# Sheet_1_2022-11-27.net
KiCad netlist of a schematic drawn in Altium Designer
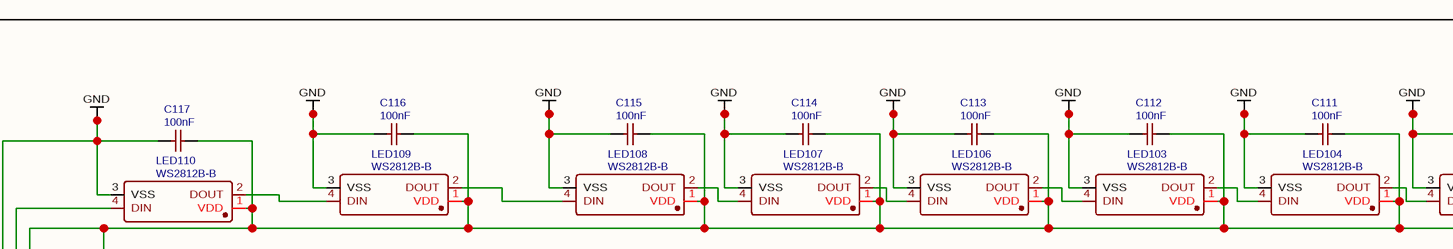
[diagram p0: Sheet_1_2022-11-27.schdoc, row 1 of 4 left]
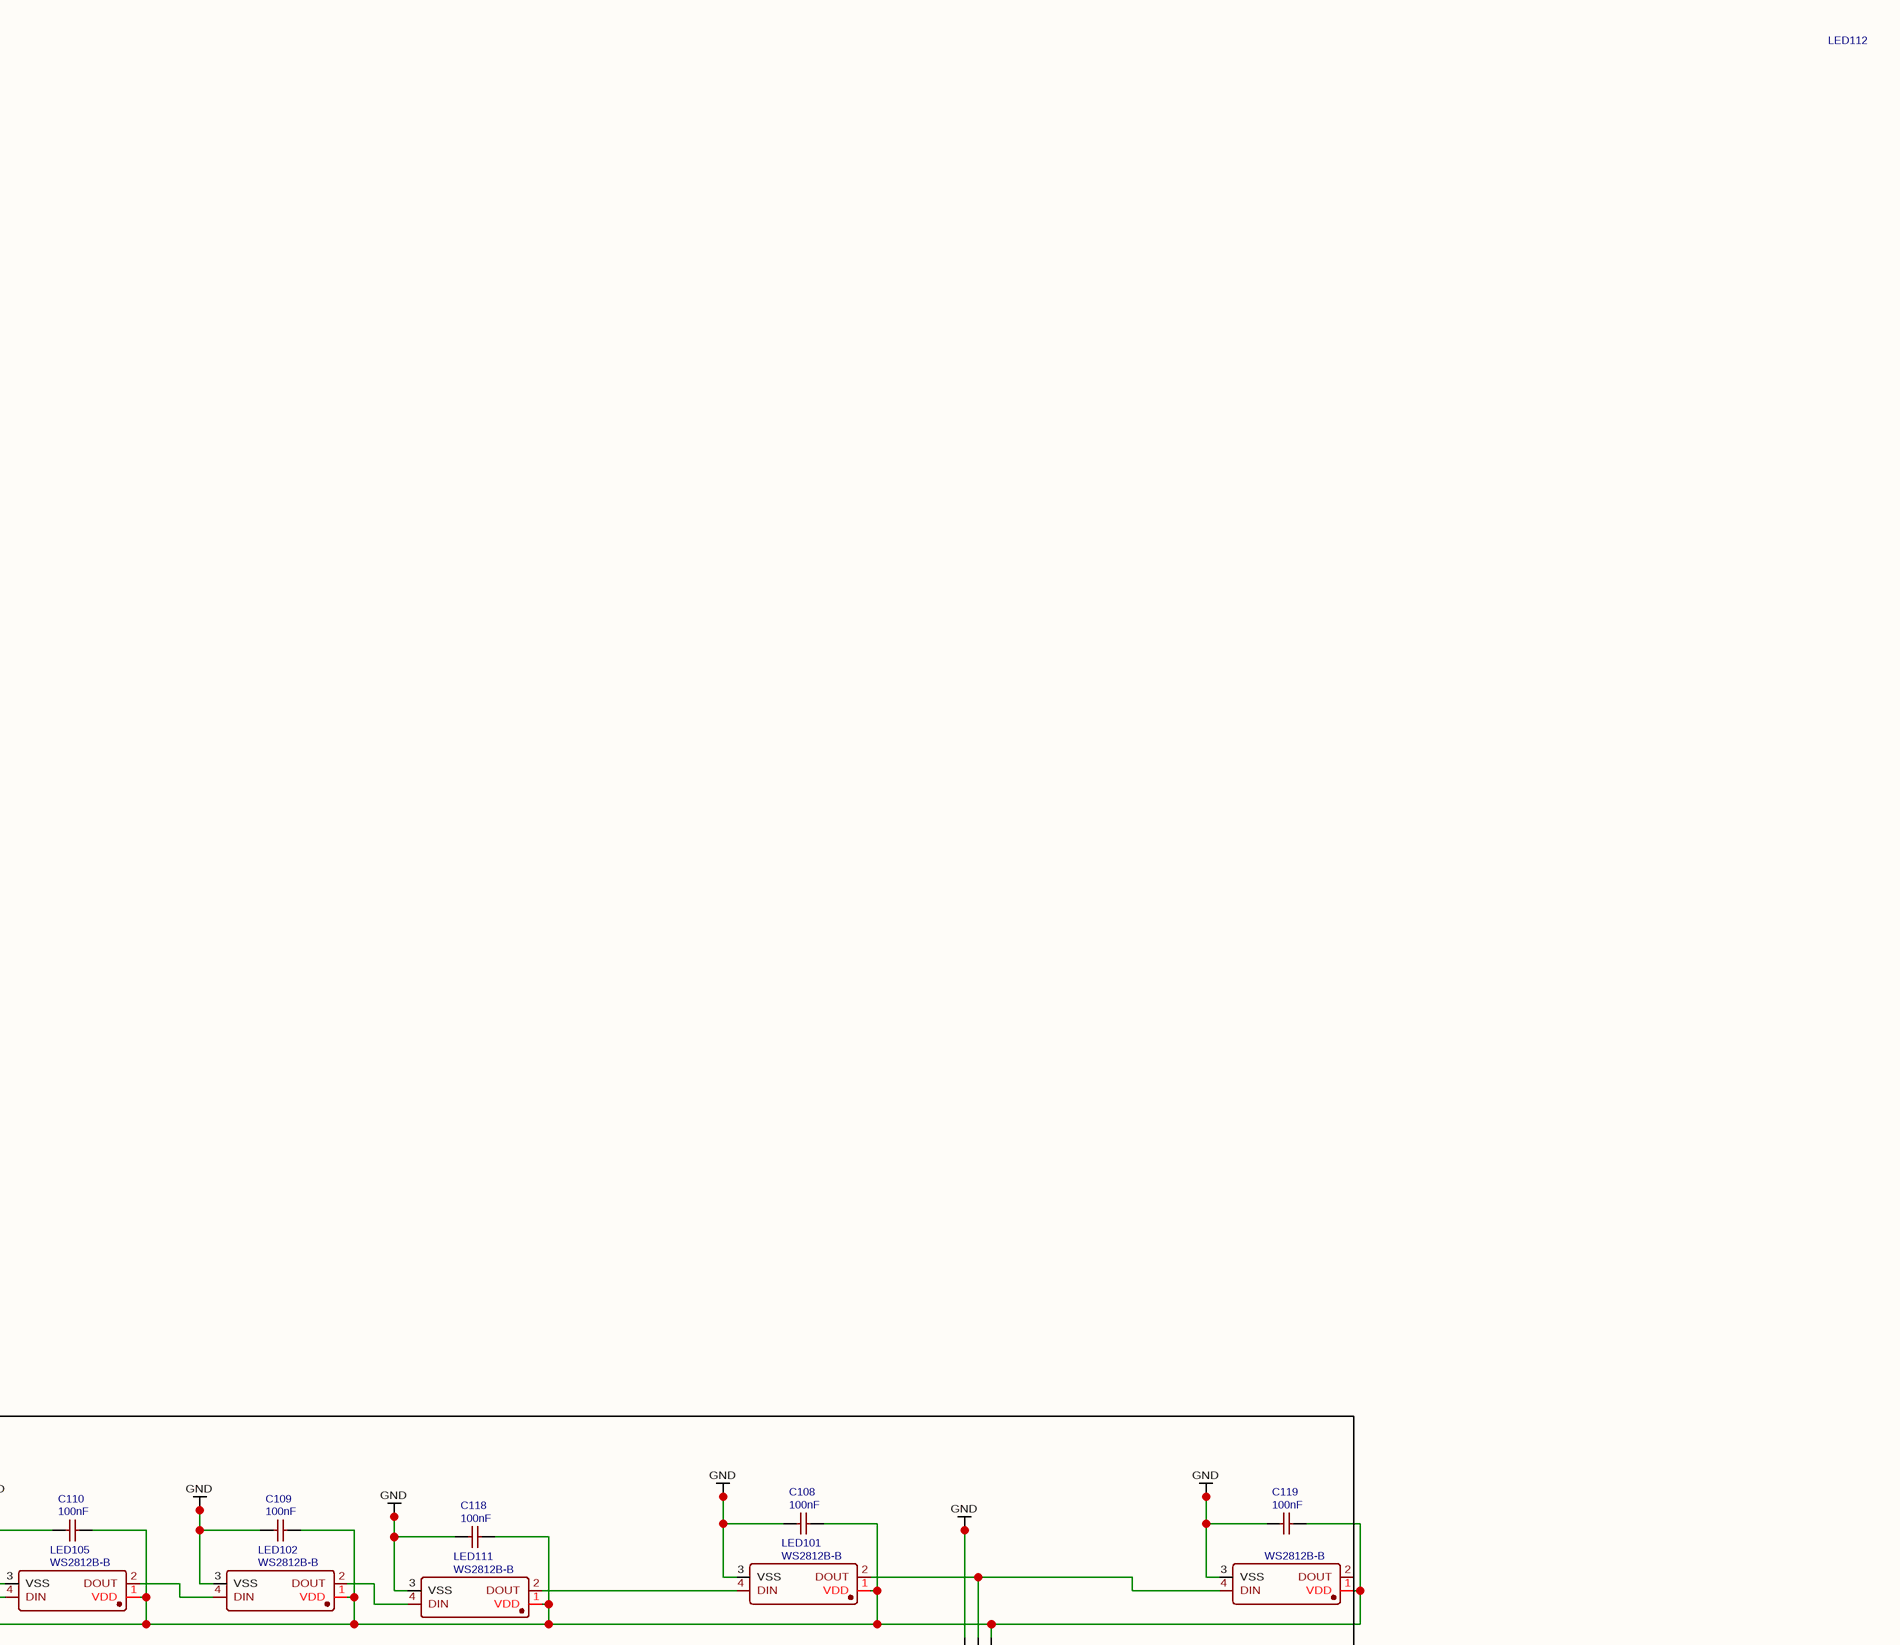
[diagram p1: Sheet_1_2022-11-27.schdoc, row 1 of 4 right]
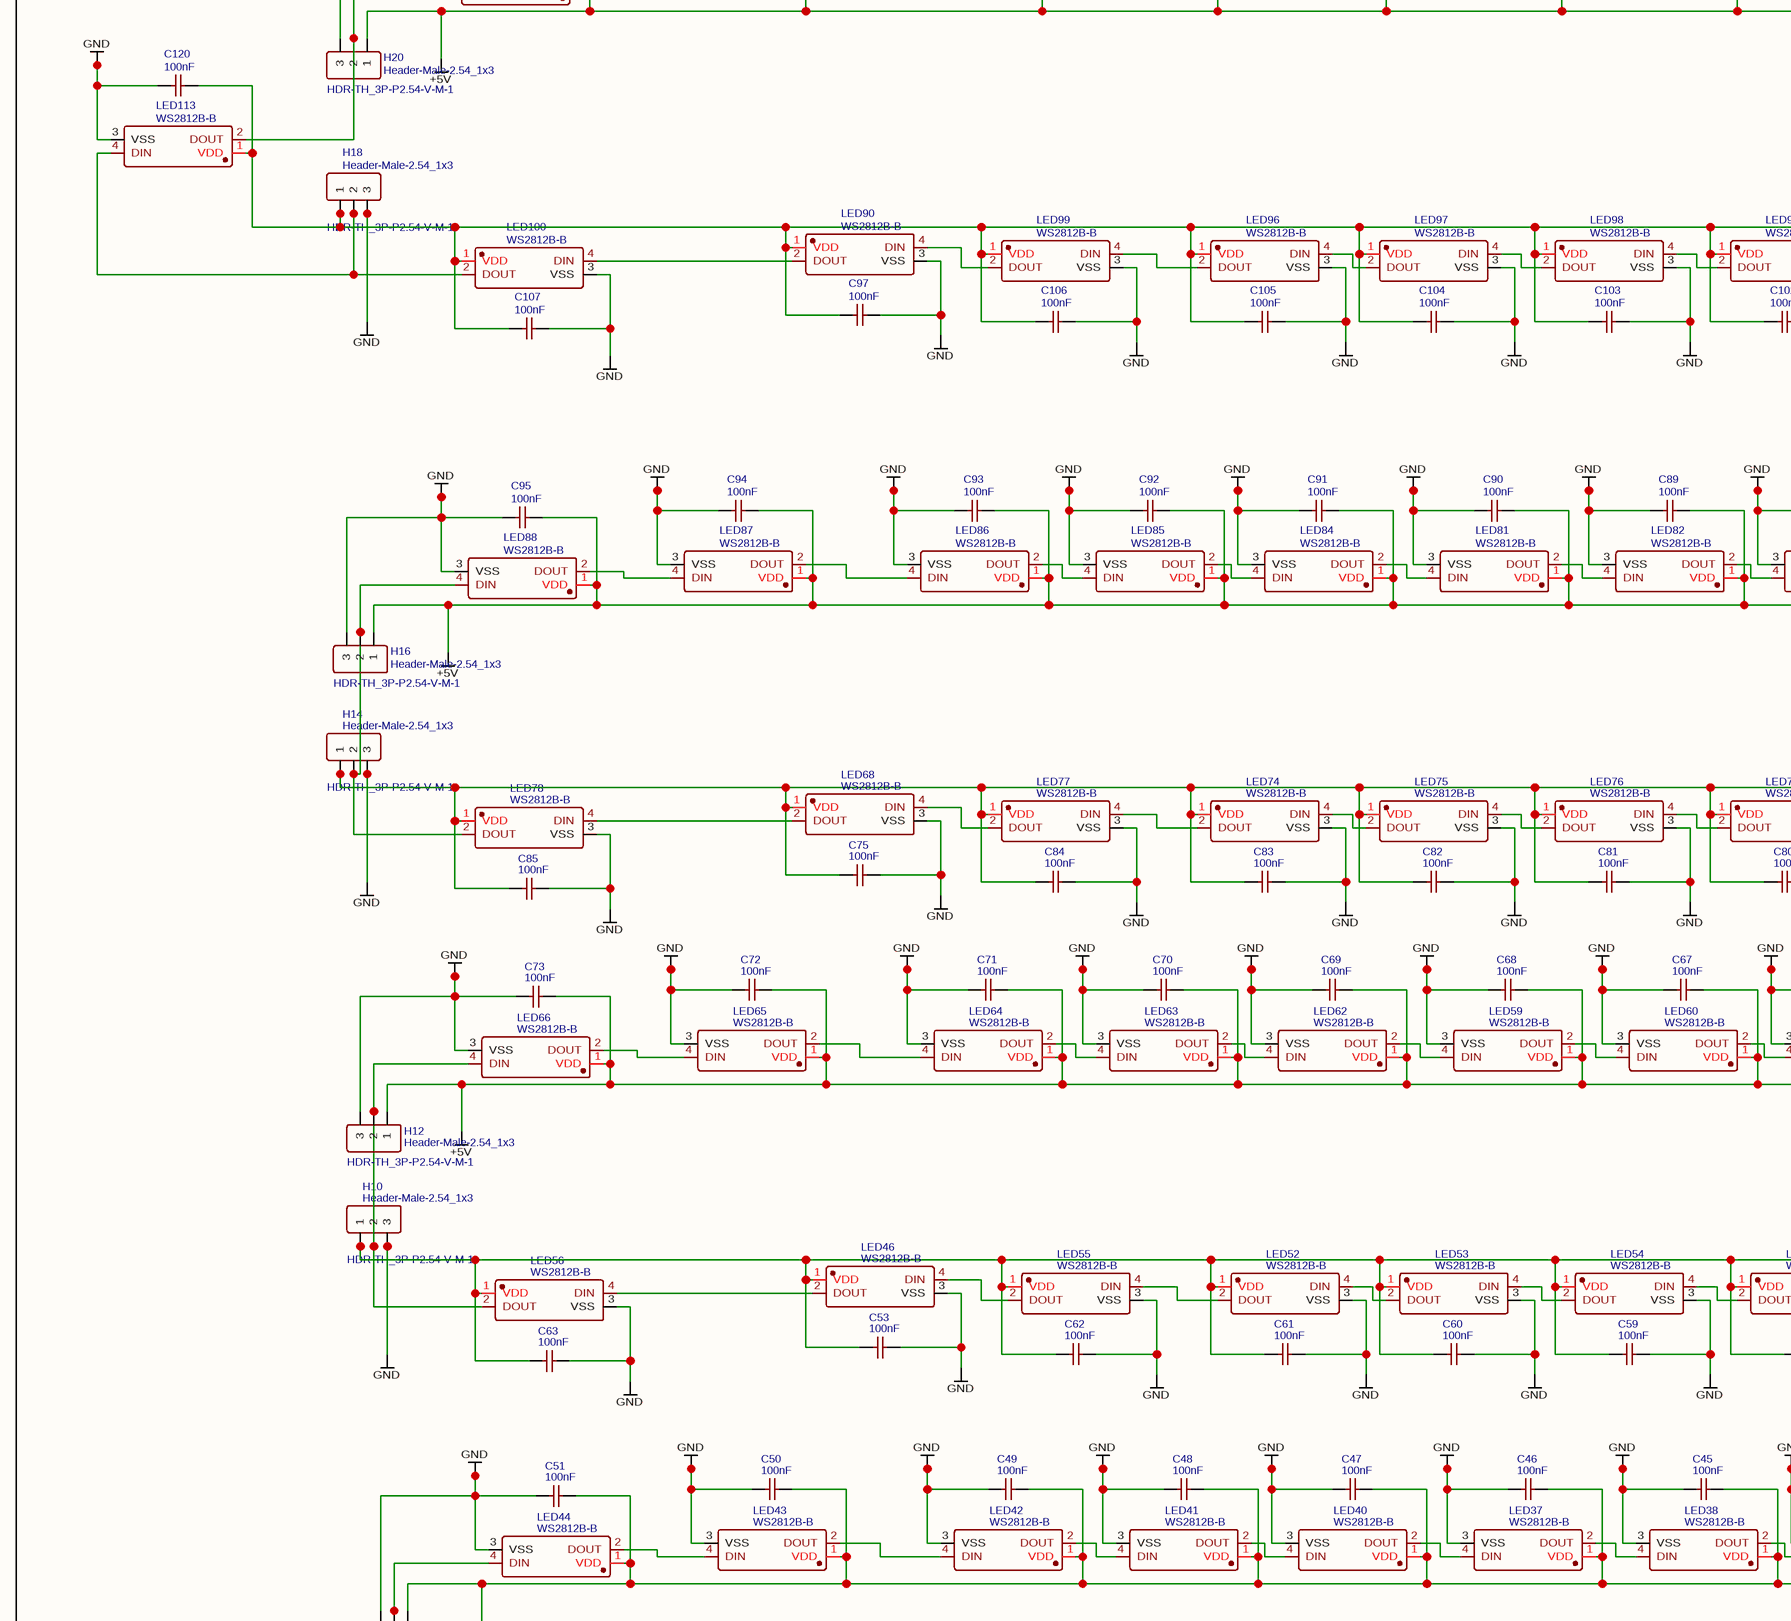
[diagram p2: Sheet_1_2022-11-27.schdoc, row 2 of 4 left]
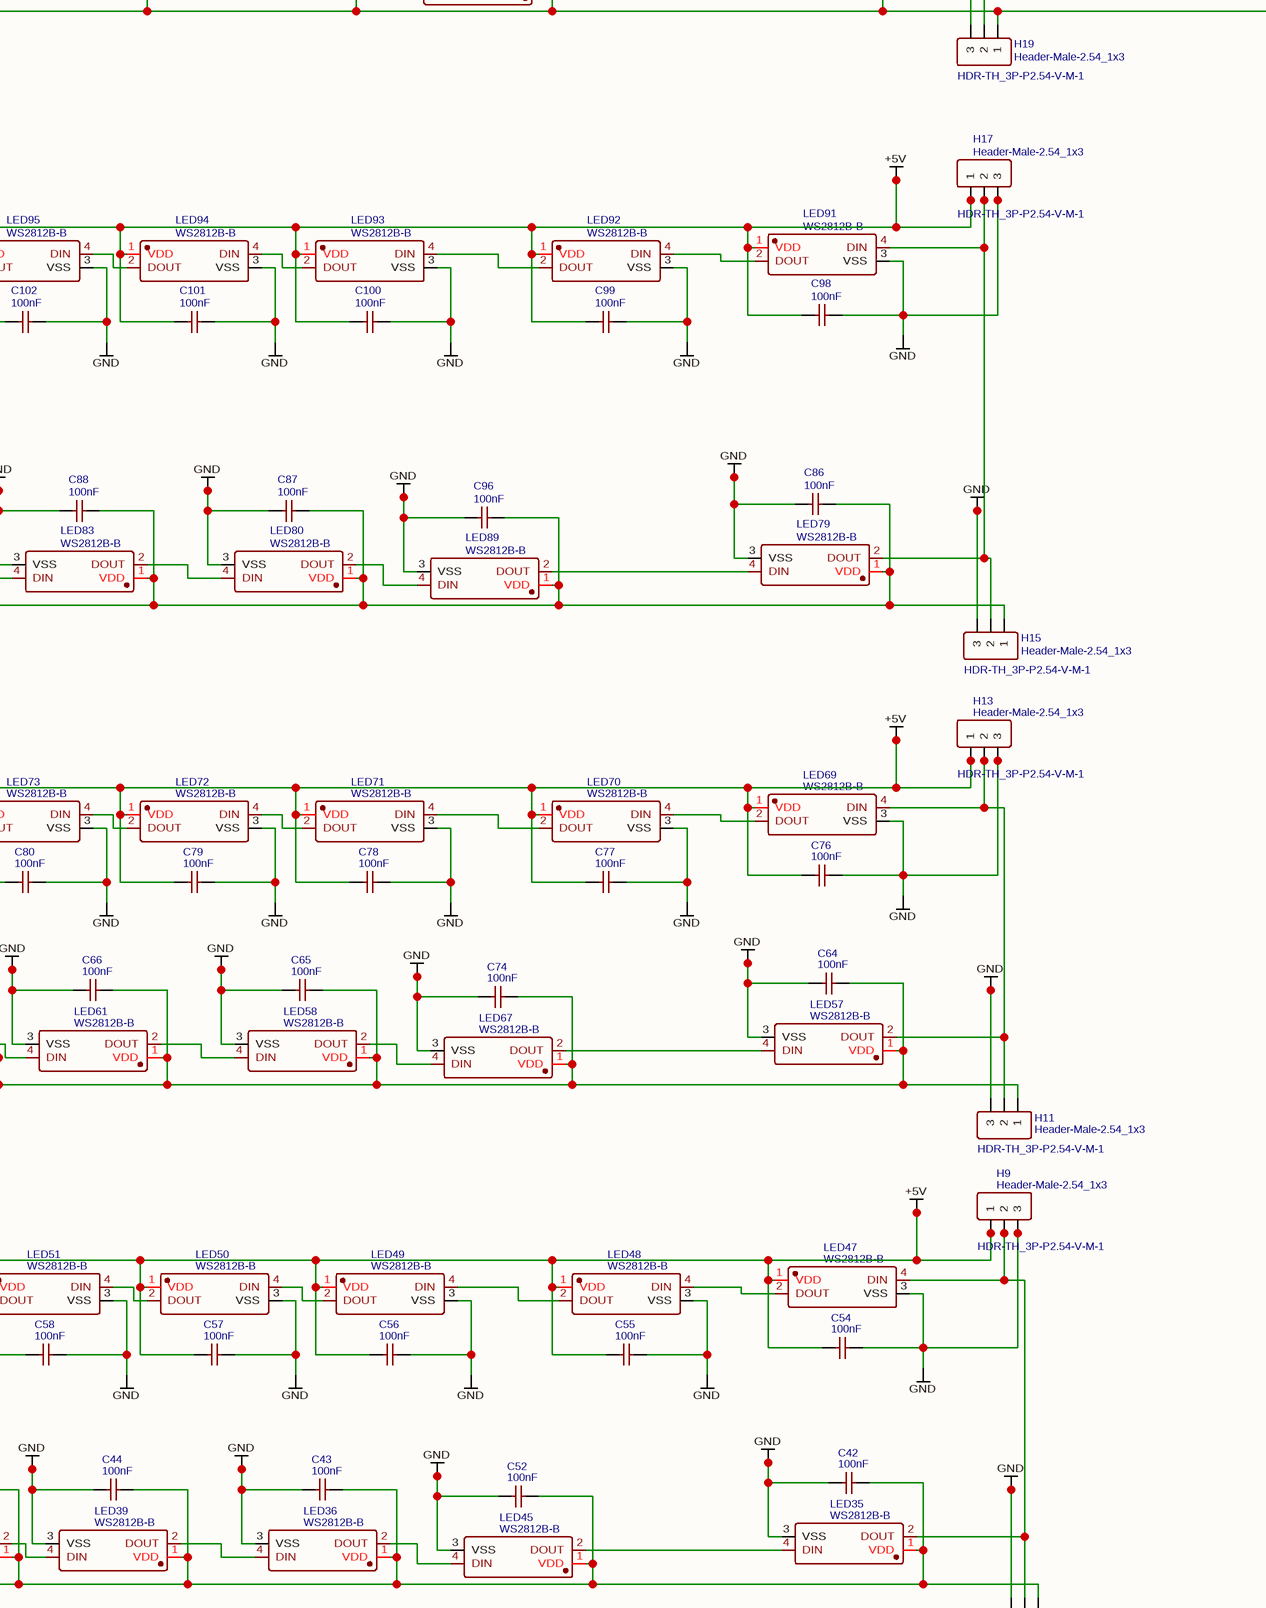
[diagram p3: Sheet_1_2022-11-27.schdoc, row 2 of 4 right]
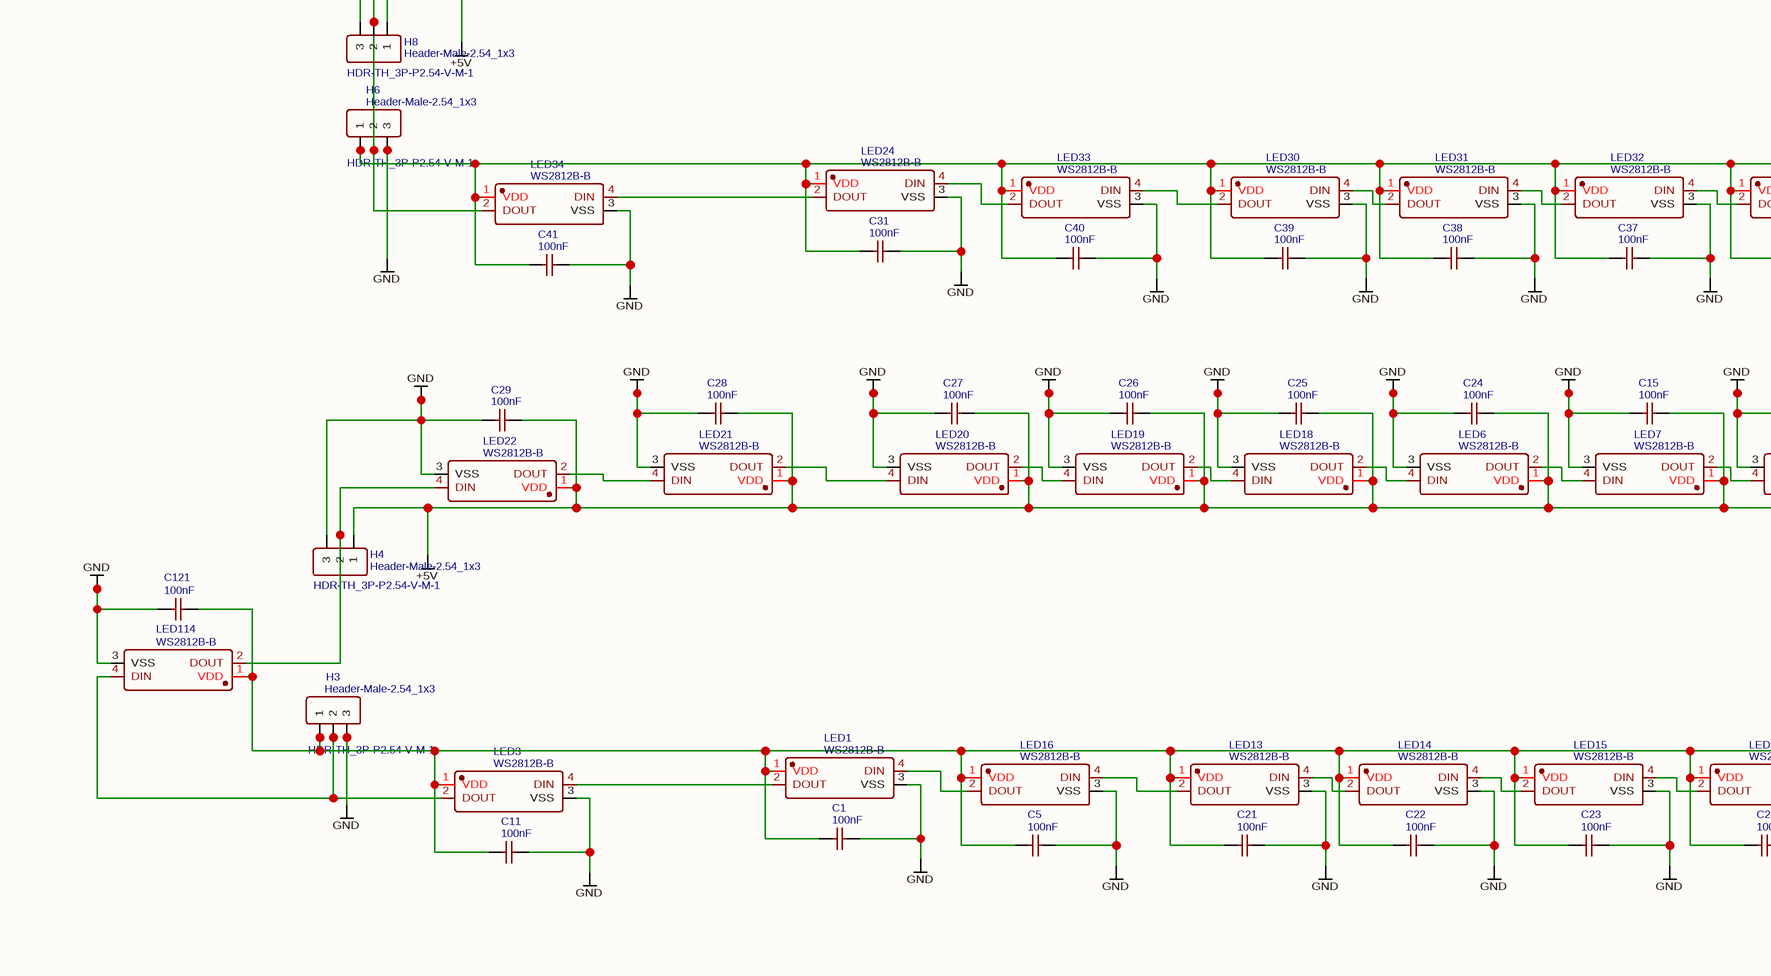
[diagram p4: Sheet_1_2022-11-27.schdoc, row 3 of 4 left]
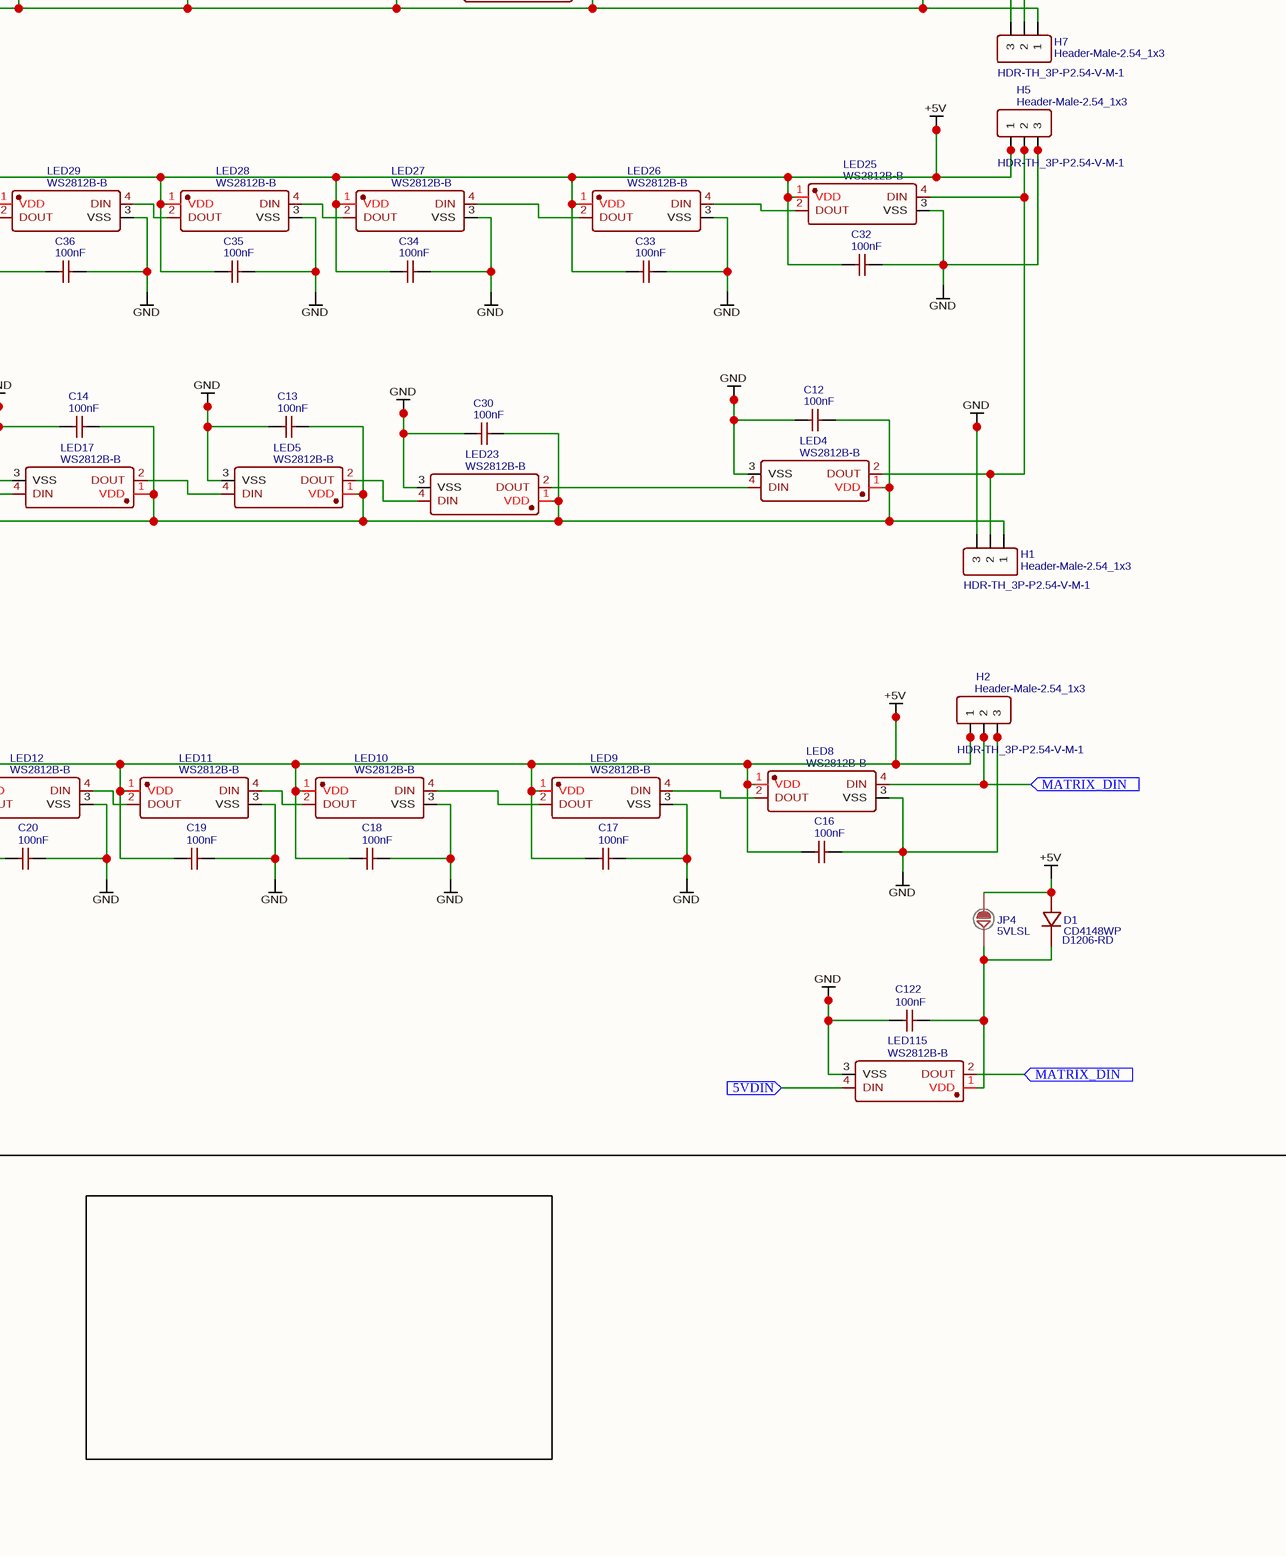
[diagram p5: Sheet_1_2022-11-27.schdoc, row 3 of 4 right]
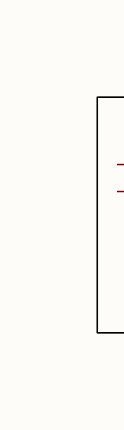
[diagram p6: Sheet_1_2022-11-27.schdoc, row 4 of 4 left]
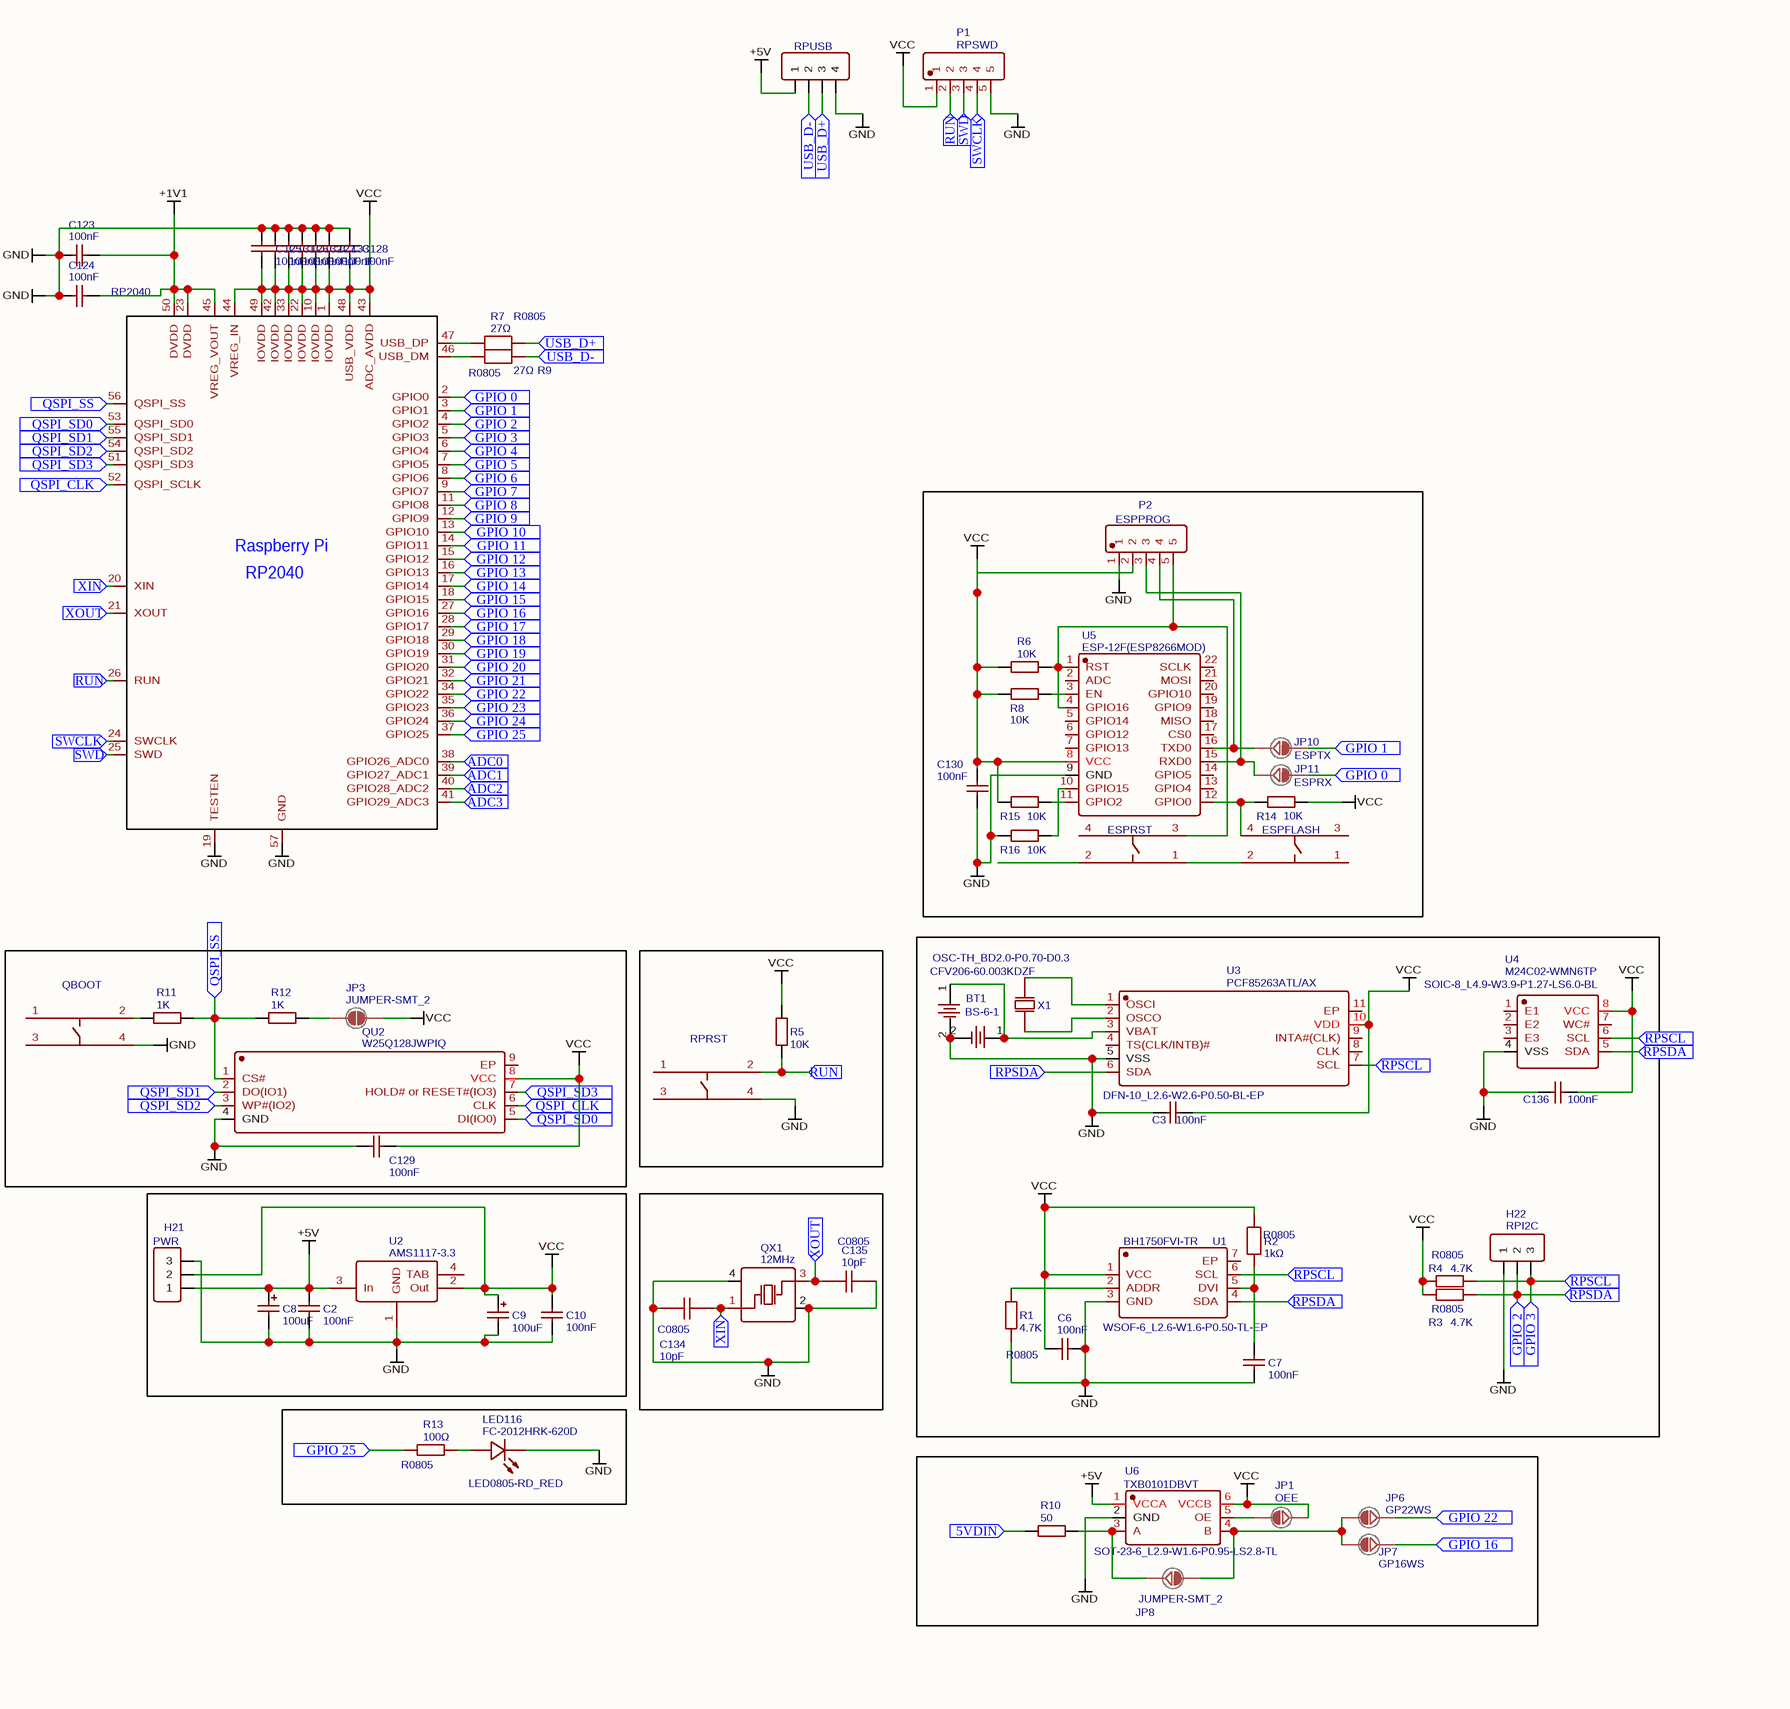
[diagram p7: Sheet_1_2022-11-27.schdoc, row 4 of 4 right]

(export (version "E")
  (design (tool "Eeschema 10.0.6"))
  (components
    (comp (ref "BT1")
      (value "BS-6-1")
      (fields (field (name "BOM_SUPPLIER PART") "C969909") (field (name "CONTRIBUTOR") "LCSC"))
      (libsource (lib "altium-import") (part "root_0_BS-6-1_"))
    )
    (comp (ref "BT2")
      (value "BS-6-1")
      (fields (field (name "BOM_SUPPLIER PART") "C969909") (field (name "CONTRIBUTOR") "LCSC"))
      (libsource (lib "altium-import") (part "root_1_BS-6-1_"))
    )
    (comp (ref "C1")
      (value "100nF")
      (fields
        (field (name "BOM_MANUFACTURER PART") "CC0805KRX7R9BB104")
        (field (name "BOM_SUPPLIER PART") "C49678")
      )
      (libsource (lib "altium-import") (part "root_0_100nF_"))
    )
    (comp (ref "C2")
      (value "100nF")
      (fields
        (field (name "BOM_MANUFACTURER PART") "CC0805KRX7R9BB104")
        (field (name "BOM_SUPPLIER PART") "C49678")
      )
      (libsource (lib "altium-import") (part "root_1_100nF_"))
    )
    (comp (ref "C3")
      (value "100nF")
      (fields
        (field (name "BOM_MANUFACTURER PART") "CC0805KRX7R9BB104")
        (field (name "BOM_SUPPLIER PART") "C49678")
      )
      (libsource (lib "altium-import") (part "root_2_100nF_"))
    )
    (comp (ref "C5")
      (value "100nF")
      (fields
        (field (name "BOM_MANUFACTURER PART") "CC0805KRX7R9BB104")
        (field (name "BOM_SUPPLIER PART") "C49678")
      )
      (libsource (lib "altium-import") (part "root_0_100nF_"))
    )
    (comp (ref "C6")
      (value "100nF")
      (fields
        (field (name "BOM_MANUFACTURER PART") "CC0805KRX7R9BB104")
        (field (name "BOM_SUPPLIER PART") "C49678")
      )
      (libsource (lib "altium-import") (part "root_2_100nF_"))
    )
    (comp (ref "C7")
      (value "100nF")
      (fields
        (field (name "BOM_MANUFACTURER PART") "CC0805KRX7R9BB104")
        (field (name "BOM_SUPPLIER PART") "C49678")
      )
      (libsource (lib "altium-import") (part "root_3_100nF_"))
    )
    (comp (ref "C8")
      (value "100uF")
      (fields
        (field (name "BOM_MANUFACTURER PART") "TAJB107K006RNJ")
        (field (name "BOM_SUPPLIER PART") "C16133")
      )
      (libsource (lib "altium-import") (part "root_3_100uF_"))
    )
    (comp (ref "C9")
      (value "100uF")
      (fields
        (field (name "BOM_MANUFACTURER PART") "TAJB107K006RNJ")
        (field (name "BOM_SUPPLIER PART") "C16133")
      )
      (libsource (lib "altium-import") (part "root_3_100uF_"))
    )
    (comp (ref "C10")
      (value "100nF")
      (fields
        (field (name "BOM_MANUFACTURER PART") "CC0805KRX7R9BB104")
        (field (name "BOM_SUPPLIER PART") "C49678")
      )
      (libsource (lib "altium-import") (part "root_1_100nF_"))
    )
    (comp (ref "C11")
      (value "100nF")
      (fields
        (field (name "BOM_MANUFACTURER PART") "CC0805KRX7R9BB104")
        (field (name "BOM_SUPPLIER PART") "C49678")
      )
      (libsource (lib "altium-import") (part "root_0_100nF_"))
    )
    (comp (ref "C12")
      (value "100nF")
      (fields
        (field (name "BOM_MANUFACTURER PART") "CC0805KRX7R9BB104")
        (field (name "BOM_SUPPLIER PART") "C49678")
      )
      (libsource (lib "altium-import") (part "root_2_100nF_"))
    )
    (comp (ref "C13")
      (value "100nF")
      (fields
        (field (name "BOM_MANUFACTURER PART") "CC0805KRX7R9BB104")
        (field (name "BOM_SUPPLIER PART") "C49678")
      )
      (libsource (lib "altium-import") (part "root_2_100nF_"))
    )
    (comp (ref "C14")
      (value "100nF")
      (fields
        (field (name "BOM_MANUFACTURER PART") "CC0805KRX7R9BB104")
        (field (name "BOM_SUPPLIER PART") "C49678")
      )
      (libsource (lib "altium-import") (part "root_2_100nF_"))
    )
    (comp (ref "C15")
      (value "100nF")
      (fields
        (field (name "BOM_MANUFACTURER PART") "CC0805KRX7R9BB104")
        (field (name "BOM_SUPPLIER PART") "C49678")
      )
      (libsource (lib "altium-import") (part "root_2_100nF_"))
    )
    (comp (ref "C16")
      (value "100nF")
      (fields
        (field (name "BOM_MANUFACTURER PART") "CC0805KRX7R9BB104")
        (field (name "BOM_SUPPLIER PART") "C49678")
      )
      (libsource (lib "altium-import") (part "root_0_100nF_"))
    )
    (comp (ref "C17")
      (value "100nF")
      (fields
        (field (name "BOM_MANUFACTURER PART") "CC0805KRX7R9BB104")
        (field (name "BOM_SUPPLIER PART") "C49678")
      )
      (libsource (lib "altium-import") (part "root_0_100nF_"))
    )
    (comp (ref "C18")
      (value "100nF")
      (fields
        (field (name "BOM_MANUFACTURER PART") "CC0805KRX7R9BB104")
        (field (name "BOM_SUPPLIER PART") "C49678")
      )
      (libsource (lib "altium-import") (part "root_0_100nF_"))
    )
    (comp (ref "C19")
      (value "100nF")
      (fields
        (field (name "BOM_MANUFACTURER PART") "CC0805KRX7R9BB104")
        (field (name "BOM_SUPPLIER PART") "C49678")
      )
      (libsource (lib "altium-import") (part "root_0_100nF_"))
    )
    (comp (ref "C20")
      (value "100nF")
      (fields
        (field (name "BOM_MANUFACTURER PART") "CC0805KRX7R9BB104")
        (field (name "BOM_SUPPLIER PART") "C49678")
      )
      (libsource (lib "altium-import") (part "root_0_100nF_"))
    )
    (comp (ref "C21")
      (value "100nF")
      (fields
        (field (name "BOM_MANUFACTURER PART") "CC0805KRX7R9BB104")
        (field (name "BOM_SUPPLIER PART") "C49678")
      )
      (libsource (lib "altium-import") (part "root_0_100nF_"))
    )
    (comp (ref "C22")
      (value "100nF")
      (fields
        (field (name "BOM_MANUFACTURER PART") "CC0805KRX7R9BB104")
        (field (name "BOM_SUPPLIER PART") "C49678")
      )
      (libsource (lib "altium-import") (part "root_0_100nF_"))
    )
    (comp (ref "C23")
      (value "100nF")
      (fields
        (field (name "BOM_MANUFACTURER PART") "CC0805KRX7R9BB104")
        (field (name "BOM_SUPPLIER PART") "C49678")
      )
      (libsource (lib "altium-import") (part "root_0_100nF_"))
    )
    (comp (ref "C24")
      (value "100nF")
      (fields
        (field (name "BOM_MANUFACTURER PART") "CC0805KRX7R9BB104")
        (field (name "BOM_SUPPLIER PART") "C49678")
      )
      (libsource (lib "altium-import") (part "root_2_100nF_"))
    )
    (comp (ref "C25")
      (value "100nF")
      (fields
        (field (name "BOM_MANUFACTURER PART") "CC0805KRX7R9BB104")
        (field (name "BOM_SUPPLIER PART") "C49678")
      )
      (libsource (lib "altium-import") (part "root_2_100nF_"))
    )
    (comp (ref "C26")
      (value "100nF")
      (fields
        (field (name "BOM_MANUFACTURER PART") "CC0805KRX7R9BB104")
        (field (name "BOM_SUPPLIER PART") "C49678")
      )
      (libsource (lib "altium-import") (part "root_2_100nF_"))
    )
    (comp (ref "C27")
      (value "100nF")
      (fields
        (field (name "BOM_MANUFACTURER PART") "CC0805KRX7R9BB104")
        (field (name "BOM_SUPPLIER PART") "C49678")
      )
      (libsource (lib "altium-import") (part "root_2_100nF_"))
    )
    (comp (ref "C28")
      (value "100nF")
      (fields
        (field (name "BOM_MANUFACTURER PART") "CC0805KRX7R9BB104")
        (field (name "BOM_SUPPLIER PART") "C49678")
      )
      (libsource (lib "altium-import") (part "root_2_100nF_"))
    )
    (comp (ref "C29")
      (value "100nF")
      (fields
        (field (name "BOM_MANUFACTURER PART") "CC0805KRX7R9BB104")
        (field (name "BOM_SUPPLIER PART") "C49678")
      )
      (libsource (lib "altium-import") (part "root_2_100nF_"))
    )
    (comp (ref "C30")
      (value "100nF")
      (fields
        (field (name "BOM_MANUFACTURER PART") "CC0805KRX7R9BB104")
        (field (name "BOM_SUPPLIER PART") "C49678")
      )
      (libsource (lib "altium-import") (part "root_2_100nF_"))
    )
    (comp (ref "C31")
      (value "100nF")
      (fields
        (field (name "BOM_MANUFACTURER PART") "CC0805KRX7R9BB104")
        (field (name "BOM_SUPPLIER PART") "C49678")
      )
      (libsource (lib "altium-import") (part "root_0_100nF_"))
    )
    (comp (ref "C32")
      (value "100nF")
      (fields
        (field (name "BOM_MANUFACTURER PART") "CC0805KRX7R9BB104")
        (field (name "BOM_SUPPLIER PART") "C49678")
      )
      (libsource (lib "altium-import") (part "root_0_100nF_"))
    )
    (comp (ref "C33")
      (value "100nF")
      (fields
        (field (name "BOM_MANUFACTURER PART") "CC0805KRX7R9BB104")
        (field (name "BOM_SUPPLIER PART") "C49678")
      )
      (libsource (lib "altium-import") (part "root_0_100nF_"))
    )
    (comp (ref "C34")
      (value "100nF")
      (fields
        (field (name "BOM_MANUFACTURER PART") "CC0805KRX7R9BB104")
        (field (name "BOM_SUPPLIER PART") "C49678")
      )
      (libsource (lib "altium-import") (part "root_0_100nF_"))
    )
    (comp (ref "C35")
      (value "100nF")
      (fields
        (field (name "BOM_MANUFACTURER PART") "CC0805KRX7R9BB104")
        (field (name "BOM_SUPPLIER PART") "C49678")
      )
      (libsource (lib "altium-import") (part "root_0_100nF_"))
    )
    (comp (ref "C36")
      (value "100nF")
      (fields
        (field (name "BOM_MANUFACTURER PART") "CC0805KRX7R9BB104")
        (field (name "BOM_SUPPLIER PART") "C49678")
      )
      (libsource (lib "altium-import") (part "root_0_100nF_"))
    )
    (comp (ref "C37")
      (value "100nF")
      (fields
        (field (name "BOM_MANUFACTURER PART") "CC0805KRX7R9BB104")
        (field (name "BOM_SUPPLIER PART") "C49678")
      )
      (libsource (lib "altium-import") (part "root_0_100nF_"))
    )
    (comp (ref "C38")
      (value "100nF")
      (fields
        (field (name "BOM_MANUFACTURER PART") "CC0805KRX7R9BB104")
        (field (name "BOM_SUPPLIER PART") "C49678")
      )
      (libsource (lib "altium-import") (part "root_0_100nF_"))
    )
    (comp (ref "C39")
      (value "100nF")
      (fields
        (field (name "BOM_MANUFACTURER PART") "CC0805KRX7R9BB104")
        (field (name "BOM_SUPPLIER PART") "C49678")
      )
      (libsource (lib "altium-import") (part "root_0_100nF_"))
    )
    (comp (ref "C40")
      (value "100nF")
      (fields
        (field (name "BOM_MANUFACTURER PART") "CC0805KRX7R9BB104")
        (field (name "BOM_SUPPLIER PART") "C49678")
      )
      (libsource (lib "altium-import") (part "root_0_100nF_"))
    )
    (comp (ref "C41")
      (value "100nF")
      (fields
        (field (name "BOM_MANUFACTURER PART") "CC0805KRX7R9BB104")
        (field (name "BOM_SUPPLIER PART") "C49678")
      )
      (libsource (lib "altium-import") (part "root_0_100nF_"))
    )
    (comp (ref "C42")
      (value "100nF")
      (fields
        (field (name "BOM_MANUFACTURER PART") "CC0805KRX7R9BB104")
        (field (name "BOM_SUPPLIER PART") "C49678")
      )
      (libsource (lib "altium-import") (part "root_2_100nF_"))
    )
    (comp (ref "C43")
      (value "100nF")
      (fields
        (field (name "BOM_MANUFACTURER PART") "CC0805KRX7R9BB104")
        (field (name "BOM_SUPPLIER PART") "C49678")
      )
      (libsource (lib "altium-import") (part "root_2_100nF_"))
    )
    (comp (ref "C44")
      (value "100nF")
      (fields
        (field (name "BOM_MANUFACTURER PART") "CC0805KRX7R9BB104")
        (field (name "BOM_SUPPLIER PART") "C49678")
      )
      (libsource (lib "altium-import") (part "root_2_100nF_"))
    )
    (comp (ref "C45")
      (value "100nF")
      (fields
        (field (name "BOM_MANUFACTURER PART") "CC0805KRX7R9BB104")
        (field (name "BOM_SUPPLIER PART") "C49678")
      )
      (libsource (lib "altium-import") (part "root_2_100nF_"))
    )
    (comp (ref "C46")
      (value "100nF")
      (fields
        (field (name "BOM_MANUFACTURER PART") "CC0805KRX7R9BB104")
        (field (name "BOM_SUPPLIER PART") "C49678")
      )
      (libsource (lib "altium-import") (part "root_2_100nF_"))
    )
    (comp (ref "C47")
      (value "100nF")
      (fields
        (field (name "BOM_MANUFACTURER PART") "CC0805KRX7R9BB104")
        (field (name "BOM_SUPPLIER PART") "C49678")
      )
      (libsource (lib "altium-import") (part "root_2_100nF_"))
    )
    (comp (ref "C48")
      (value "100nF")
      (fields
        (field (name "BOM_MANUFACTURER PART") "CC0805KRX7R9BB104")
        (field (name "BOM_SUPPLIER PART") "C49678")
      )
      (libsource (lib "altium-import") (part "root_2_100nF_"))
    )
    (comp (ref "C49")
      (value "100nF")
      (fields
        (field (name "BOM_MANUFACTURER PART") "CC0805KRX7R9BB104")
        (field (name "BOM_SUPPLIER PART") "C49678")
      )
      (libsource (lib "altium-import") (part "root_2_100nF_"))
    )
    (comp (ref "C50")
      (value "100nF")
      (fields
        (field (name "BOM_MANUFACTURER PART") "CC0805KRX7R9BB104")
        (field (name "BOM_SUPPLIER PART") "C49678")
      )
      (libsource (lib "altium-import") (part "root_2_100nF_"))
    )
    (comp (ref "C51")
      (value "100nF")
      (fields
        (field (name "BOM_MANUFACTURER PART") "CC0805KRX7R9BB104")
        (field (name "BOM_SUPPLIER PART") "C49678")
      )
      (libsource (lib "altium-import") (part "root_2_100nF_"))
    )
    (comp (ref "C52")
      (value "100nF")
      (fields
        (field (name "BOM_MANUFACTURER PART") "CC0805KRX7R9BB104")
        (field (name "BOM_SUPPLIER PART") "C49678")
      )
      (libsource (lib "altium-import") (part "root_2_100nF_"))
    )
    (comp (ref "C53")
      (value "100nF")
      (fields
        (field (name "BOM_MANUFACTURER PART") "CC0805KRX7R9BB104")
        (field (name "BOM_SUPPLIER PART") "C49678")
      )
      (libsource (lib "altium-import") (part "root_0_100nF_"))
    )
    (comp (ref "C54")
      (value "100nF")
      (fields
        (field (name "BOM_MANUFACTURER PART") "CC0805KRX7R9BB104")
        (field (name "BOM_SUPPLIER PART") "C49678")
      )
      (libsource (lib "altium-import") (part "root_0_100nF_"))
    )
    (comp (ref "C55")
      (value "100nF")
      (fields
        (field (name "BOM_MANUFACTURER PART") "CC0805KRX7R9BB104")
        (field (name "BOM_SUPPLIER PART") "C49678")
      )
      (libsource (lib "altium-import") (part "root_0_100nF_"))
    )
    (comp (ref "C56")
      (value "100nF")
      (fields
        (field (name "BOM_MANUFACTURER PART") "CC0805KRX7R9BB104")
        (field (name "BOM_SUPPLIER PART") "C49678")
      )
      (libsource (lib "altium-import") (part "root_0_100nF_"))
    )
    (comp (ref "C57")
      (value "100nF")
      (fields
        (field (name "BOM_MANUFACTURER PART") "CC0805KRX7R9BB104")
        (field (name "BOM_SUPPLIER PART") "C49678")
      )
      (libsource (lib "altium-import") (part "root_0_100nF_"))
    )
    (comp (ref "C58")
      (value "100nF")
      (fields
        (field (name "BOM_MANUFACTURER PART") "CC0805KRX7R9BB104")
        (field (name "BOM_SUPPLIER PART") "C49678")
      )
      (libsource (lib "altium-import") (part "root_0_100nF_"))
    )
    (comp (ref "C59")
      (value "100nF")
      (fields
        (field (name "BOM_MANUFACTURER PART") "CC0805KRX7R9BB104")
        (field (name "BOM_SUPPLIER PART") "C49678")
      )
      (libsource (lib "altium-import") (part "root_0_100nF_"))
    )
    (comp (ref "C60")
      (value "100nF")
      (fields
        (field (name "BOM_MANUFACTURER PART") "CC0805KRX7R9BB104")
        (field (name "BOM_SUPPLIER PART") "C49678")
      )
      (libsource (lib "altium-import") (part "root_0_100nF_"))
    )
    (comp (ref "C61")
      (value "100nF")
      (fields
        (field (name "BOM_MANUFACTURER PART") "CC0805KRX7R9BB104")
        (field (name "BOM_SUPPLIER PART") "C49678")
      )
      (libsource (lib "altium-import") (part "root_0_100nF_"))
    )
    (comp (ref "C62")
      (value "100nF")
      (fields
        (field (name "BOM_MANUFACTURER PART") "CC0805KRX7R9BB104")
        (field (name "BOM_SUPPLIER PART") "C49678")
      )
      (libsource (lib "altium-import") (part "root_0_100nF_"))
    )
    (comp (ref "C63")
      (value "100nF")
      (fields
        (field (name "BOM_MANUFACTURER PART") "CC0805KRX7R9BB104")
        (field (name "BOM_SUPPLIER PART") "C49678")
      )
      (libsource (lib "altium-import") (part "root_0_100nF_"))
    )
    (comp (ref "C64")
      (value "100nF")
      (fields
        (field (name "BOM_MANUFACTURER PART") "CC0805KRX7R9BB104")
        (field (name "BOM_SUPPLIER PART") "C49678")
      )
      (libsource (lib "altium-import") (part "root_2_100nF_"))
    )
    (comp (ref "C65")
      (value "100nF")
      (fields
        (field (name "BOM_MANUFACTURER PART") "CC0805KRX7R9BB104")
        (field (name "BOM_SUPPLIER PART") "C49678")
      )
      (libsource (lib "altium-import") (part "root_2_100nF_"))
    )
    (comp (ref "C66")
      (value "100nF")
      (fields
        (field (name "BOM_MANUFACTURER PART") "CC0805KRX7R9BB104")
        (field (name "BOM_SUPPLIER PART") "C49678")
      )
      (libsource (lib "altium-import") (part "root_2_100nF_"))
    )
    (comp (ref "C67")
      (value "100nF")
      (fields
        (field (name "BOM_MANUFACTURER PART") "CC0805KRX7R9BB104")
        (field (name "BOM_SUPPLIER PART") "C49678")
      )
      (libsource (lib "altium-import") (part "root_2_100nF_"))
    )
    (comp (ref "C68")
      (value "100nF")
      (fields
        (field (name "BOM_MANUFACTURER PART") "CC0805KRX7R9BB104")
        (field (name "BOM_SUPPLIER PART") "C49678")
      )
      (libsource (lib "altium-import") (part "root_2_100nF_"))
    )
    (comp (ref "C69")
      (value "100nF")
      (fields
        (field (name "BOM_MANUFACTURER PART") "CC0805KRX7R9BB104")
        (field (name "BOM_SUPPLIER PART") "C49678")
      )
      (libsource (lib "altium-import") (part "root_2_100nF_"))
    )
    (comp (ref "C70")
      (value "100nF")
      (fields
        (field (name "BOM_MANUFACTURER PART") "CC0805KRX7R9BB104")
        (field (name "BOM_SUPPLIER PART") "C49678")
      )
      (libsource (lib "altium-import") (part "root_2_100nF_"))
    )
    (comp (ref "C71")
      (value "100nF")
      (fields
        (field (name "BOM_MANUFACTURER PART") "CC0805KRX7R9BB104")
        (field (name "BOM_SUPPLIER PART") "C49678")
      )
      (libsource (lib "altium-import") (part "root_2_100nF_"))
    )
    (comp (ref "C72")
      (value "100nF")
      (fields
        (field (name "BOM_MANUFACTURER PART") "CC0805KRX7R9BB104")
        (field (name "BOM_SUPPLIER PART") "C49678")
      )
      (libsource (lib "altium-import") (part "root_2_100nF_"))
    )
    (comp (ref "C73")
      (value "100nF")
      (fields
        (field (name "BOM_MANUFACTURER PART") "CC0805KRX7R9BB104")
        (field (name "BOM_SUPPLIER PART") "C49678")
      )
      (libsource (lib "altium-import") (part "root_2_100nF_"))
    )
    (comp (ref "C74")
      (value "100nF")
      (fields
        (field (name "BOM_MANUFACTURER PART") "CC0805KRX7R9BB104")
        (field (name "BOM_SUPPLIER PART") "C49678")
      )
      (libsource (lib "altium-import") (part "root_2_100nF_"))
    )
    (comp (ref "C75")
      (value "100nF")
      (fields
        (field (name "BOM_MANUFACTURER PART") "CC0805KRX7R9BB104")
        (field (name "BOM_SUPPLIER PART") "C49678")
      )
      (libsource (lib "altium-import") (part "root_0_100nF_"))
    )
    (comp (ref "C76")
      (value "100nF")
      (fields
        (field (name "BOM_MANUFACTURER PART") "CC0805KRX7R9BB104")
        (field (name "BOM_SUPPLIER PART") "C49678")
      )
      (libsource (lib "altium-import") (part "root_0_100nF_"))
    )
    (comp (ref "C77")
      (value "100nF")
      (fields
        (field (name "BOM_MANUFACTURER PART") "CC0805KRX7R9BB104")
        (field (name "BOM_SUPPLIER PART") "C49678")
      )
      (libsource (lib "altium-import") (part "root_0_100nF_"))
    )
    (comp (ref "C78")
      (value "100nF")
      (fields
        (field (name "BOM_MANUFACTURER PART") "CC0805KRX7R9BB104")
        (field (name "BOM_SUPPLIER PART") "C49678")
      )
      (libsource (lib "altium-import") (part "root_0_100nF_"))
    )
    (comp (ref "C79")
      (value "100nF")
      (fields
        (field (name "BOM_MANUFACTURER PART") "CC0805KRX7R9BB104")
        (field (name "BOM_SUPPLIER PART") "C49678")
      )
      (libsource (lib "altium-import") (part "root_0_100nF_"))
    )
    (comp (ref "C80")
      (value "100nF")
      (fields
        (field (name "BOM_MANUFACTURER PART") "CC0805KRX7R9BB104")
        (field (name "BOM_SUPPLIER PART") "C49678")
      )
      (libsource (lib "altium-import") (part "root_0_100nF_"))
    )
    (comp (ref "C81")
      (value "100nF")
      (fields
        (field (name "BOM_MANUFACTURER PART") "CC0805KRX7R9BB104")
        (field (name "BOM_SUPPLIER PART") "C49678")
      )
      (libsource (lib "altium-import") (part "root_0_100nF_"))
    )
    (comp (ref "C82")
      (value "100nF")
      (fields
        (field (name "BOM_MANUFACTURER PART") "CC0805KRX7R9BB104")
        (field (name "BOM_SUPPLIER PART") "C49678")
      )
      (libsource (lib "altium-import") (part "root_0_100nF_"))
    )
    (comp (ref "C83")
      (value "100nF")
      (fields
        (field (name "BOM_MANUFACTURER PART") "CC0805KRX7R9BB104")
        (field (name "BOM_SUPPLIER PART") "C49678")
      )
      (libsource (lib "altium-import") (part "root_0_100nF_"))
    )
    (comp (ref "C84")
      (value "100nF")
      (fields
        (field (name "BOM_MANUFACTURER PART") "CC0805KRX7R9BB104")
        (field (name "BOM_SUPPLIER PART") "C49678")
      )
      (libsource (lib "altium-import") (part "root_0_100nF_"))
    )
    (comp (ref "C85")
      (value "100nF")
      (fields
        (field (name "BOM_MANUFACTURER PART") "CC0805KRX7R9BB104")
        (field (name "BOM_SUPPLIER PART") "C49678")
      )
      (libsource (lib "altium-import") (part "root_0_100nF_"))
    )
    (comp (ref "C86")
      (value "100nF")
      (fields
        (field (name "BOM_MANUFACTURER PART") "CC0805KRX7R9BB104")
        (field (name "BOM_SUPPLIER PART") "C49678")
      )
      (libsource (lib "altium-import") (part "root_2_100nF_"))
    )
    (comp (ref "C87")
      (value "100nF")
      (fields
        (field (name "BOM_MANUFACTURER PART") "CC0805KRX7R9BB104")
        (field (name "BOM_SUPPLIER PART") "C49678")
      )
      (libsource (lib "altium-import") (part "root_2_100nF_"))
    )
    (comp (ref "C88")
      (value "100nF")
      (fields
        (field (name "BOM_MANUFACTURER PART") "CC0805KRX7R9BB104")
        (field (name "BOM_SUPPLIER PART") "C49678")
      )
      (libsource (lib "altium-import") (part "root_2_100nF_"))
    )
    (comp (ref "C89")
      (value "100nF")
      (fields
        (field (name "BOM_MANUFACTURER PART") "CC0805KRX7R9BB104")
        (field (name "BOM_SUPPLIER PART") "C49678")
      )
      (libsource (lib "altium-import") (part "root_2_100nF_"))
    )
    (comp (ref "C90")
      (value "100nF")
      (fields
        (field (name "BOM_MANUFACTURER PART") "CC0805KRX7R9BB104")
        (field (name "BOM_SUPPLIER PART") "C49678")
      )
      (libsource (lib "altium-import") (part "root_2_100nF_"))
    )
    (comp (ref "C91")
      (value "100nF")
      (fields
        (field (name "BOM_MANUFACTURER PART") "CC0805KRX7R9BB104")
        (field (name "BOM_SUPPLIER PART") "C49678")
      )
      (libsource (lib "altium-import") (part "root_2_100nF_"))
    )
    (comp (ref "C92")
      (value "100nF")
      (fields
        (field (name "BOM_MANUFACTURER PART") "CC0805KRX7R9BB104")
        (field (name "BOM_SUPPLIER PART") "C49678")
      )
      (libsource (lib "altium-import") (part "root_2_100nF_"))
    )
    (comp (ref "C93")
      (value "100nF")
      (fields
        (field (name "BOM_MANUFACTURER PART") "CC0805KRX7R9BB104")
        (field (name "BOM_SUPPLIER PART") "C49678")
      )
      (libsource (lib "altium-import") (part "root_2_100nF_"))
    )
    (comp (ref "C94")
      (value "100nF")
      (fields
        (field (name "BOM_MANUFACTURER PART") "CC0805KRX7R9BB104")
        (field (name "BOM_SUPPLIER PART") "C49678")
      )
      (libsource (lib "altium-import") (part "root_2_100nF_"))
    )
    (comp (ref "C95")
      (value "100nF")
      (fields
        (field (name "BOM_MANUFACTURER PART") "CC0805KRX7R9BB104")
        (field (name "BOM_SUPPLIER PART") "C49678")
      )
      (libsource (lib "altium-import") (part "root_2_100nF_"))
    )
    (comp (ref "C96")
      (value "100nF")
      (fields
        (field (name "BOM_MANUFACTURER PART") "CC0805KRX7R9BB104")
        (field (name "BOM_SUPPLIER PART") "C49678")
      )
      (libsource (lib "altium-import") (part "root_2_100nF_"))
    )
    (comp (ref "C97")
      (value "100nF")
      (fields
        (field (name "BOM_MANUFACTURER PART") "CC0805KRX7R9BB104")
        (field (name "BOM_SUPPLIER PART") "C49678")
      )
      (libsource (lib "altium-import") (part "root_0_100nF_"))
    )
    (comp (ref "C98")
      (value "100nF")
      (fields
        (field (name "BOM_MANUFACTURER PART") "CC0805KRX7R9BB104")
        (field (name "BOM_SUPPLIER PART") "C49678")
      )
      (libsource (lib "altium-import") (part "root_0_100nF_"))
    )
    (comp (ref "C99")
      (value "100nF")
      (fields
        (field (name "BOM_MANUFACTURER PART") "CC0805KRX7R9BB104")
        (field (name "BOM_SUPPLIER PART") "C49678")
      )
      (libsource (lib "altium-import") (part "root_0_100nF_"))
    )
    (comp (ref "C100")
      (value "100nF")
      (fields
        (field (name "BOM_MANUFACTURER PART") "CC0805KRX7R9BB104")
        (field (name "BOM_SUPPLIER PART") "C49678")
      )
      (libsource (lib "altium-import") (part "root_0_100nF_"))
    )
    (comp (ref "C101")
      (value "100nF")
      (fields
        (field (name "BOM_MANUFACTURER PART") "CC0805KRX7R9BB104")
        (field (name "BOM_SUPPLIER PART") "C49678")
      )
      (libsource (lib "altium-import") (part "root_0_100nF_"))
    )
    (comp (ref "C102")
      (value "100nF")
      (fields
        (field (name "BOM_MANUFACTURER PART") "CC0805KRX7R9BB104")
        (field (name "BOM_SUPPLIER PART") "C49678")
      )
      (libsource (lib "altium-import") (part "root_0_100nF_"))
    )
    (comp (ref "C103")
      (value "100nF")
      (fields
        (field (name "BOM_MANUFACTURER PART") "CC0805KRX7R9BB104")
        (field (name "BOM_SUPPLIER PART") "C49678")
      )
      (libsource (lib "altium-import") (part "root_0_100nF_"))
    )
    (comp (ref "C104")
      (value "100nF")
      (fields
        (field (name "BOM_MANUFACTURER PART") "CC0805KRX7R9BB104")
        (field (name "BOM_SUPPLIER PART") "C49678")
      )
      (libsource (lib "altium-import") (part "root_0_100nF_"))
    )
    (comp (ref "C105")
      (value "100nF")
      (fields
        (field (name "BOM_MANUFACTURER PART") "CC0805KRX7R9BB104")
        (field (name "BOM_SUPPLIER PART") "C49678")
      )
      (libsource (lib "altium-import") (part "root_0_100nF_"))
    )
    (comp (ref "C106")
      (value "100nF")
      (fields
        (field (name "BOM_MANUFACTURER PART") "CC0805KRX7R9BB104")
        (field (name "BOM_SUPPLIER PART") "C49678")
      )
      (libsource (lib "altium-import") (part "root_0_100nF_"))
    )
    (comp (ref "C107")
      (value "100nF")
      (fields
        (field (name "BOM_MANUFACTURER PART") "CC0805KRX7R9BB104")
        (field (name "BOM_SUPPLIER PART") "C49678")
      )
      (libsource (lib "altium-import") (part "root_0_100nF_"))
    )
    (comp (ref "C108")
      (value "100nF")
      (fields
        (field (name "BOM_MANUFACTURER PART") "CC0805KRX7R9BB104")
        (field (name "BOM_SUPPLIER PART") "C49678")
      )
      (libsource (lib "altium-import") (part "root_2_100nF_"))
    )
    (comp (ref "C109")
      (value "100nF")
      (fields
        (field (name "BOM_MANUFACTURER PART") "CC0805KRX7R9BB104")
        (field (name "BOM_SUPPLIER PART") "C49678")
      )
      (libsource (lib "altium-import") (part "root_2_100nF_"))
    )
    (comp (ref "C110")
      (value "100nF")
      (fields
        (field (name "BOM_MANUFACTURER PART") "CC0805KRX7R9BB104")
        (field (name "BOM_SUPPLIER PART") "C49678")
      )
      (libsource (lib "altium-import") (part "root_2_100nF_"))
    )
    (comp (ref "C111")
      (value "100nF")
      (fields
        (field (name "BOM_MANUFACTURER PART") "CC0805KRX7R9BB104")
        (field (name "BOM_SUPPLIER PART") "C49678")
      )
      (libsource (lib "altium-import") (part "root_2_100nF_"))
    )
    (comp (ref "C112")
      (value "100nF")
      (fields
        (field (name "BOM_MANUFACTURER PART") "CC0805KRX7R9BB104")
        (field (name "BOM_SUPPLIER PART") "C49678")
      )
      (libsource (lib "altium-import") (part "root_2_100nF_"))
    )
    (comp (ref "C113")
      (value "100nF")
      (fields
        (field (name "BOM_MANUFACTURER PART") "CC0805KRX7R9BB104")
        (field (name "BOM_SUPPLIER PART") "C49678")
      )
      (libsource (lib "altium-import") (part "root_2_100nF_"))
    )
    (comp (ref "C114")
      (value "100nF")
      (fields
        (field (name "BOM_MANUFACTURER PART") "CC0805KRX7R9BB104")
        (field (name "BOM_SUPPLIER PART") "C49678")
      )
      (libsource (lib "altium-import") (part "root_2_100nF_"))
    )
    (comp (ref "C115")
      (value "100nF")
      (fields
        (field (name "BOM_MANUFACTURER PART") "CC0805KRX7R9BB104")
        (field (name "BOM_SUPPLIER PART") "C49678")
      )
      (libsource (lib "altium-import") (part "root_2_100nF_"))
    )
    (comp (ref "C116")
      (value "100nF")
      (fields
        (field (name "BOM_MANUFACTURER PART") "CC0805KRX7R9BB104")
        (field (name "BOM_SUPPLIER PART") "C49678")
      )
      (libsource (lib "altium-import") (part "root_2_100nF_"))
    )
    (comp (ref "C117")
      (value "100nF")
      (fields
        (field (name "BOM_MANUFACTURER PART") "CC0805KRX7R9BB104")
        (field (name "BOM_SUPPLIER PART") "C49678")
      )
      (libsource (lib "altium-import") (part "root_2_100nF_"))
    )
    (comp (ref "C118")
      (value "100nF")
      (fields
        (field (name "BOM_MANUFACTURER PART") "CC0805KRX7R9BB104")
        (field (name "BOM_SUPPLIER PART") "C49678")
      )
      (libsource (lib "altium-import") (part "root_2_100nF_"))
    )
    (comp (ref "C119")
      (value "100nF")
      (fields
        (field (name "BOM_MANUFACTURER PART") "CC0805KRX7R9BB104")
        (field (name "BOM_SUPPLIER PART") "C49678")
      )
      (libsource (lib "altium-import") (part "root_2_100nF_"))
    )
    (comp (ref "C120")
      (value "100nF")
      (fields
        (field (name "BOM_MANUFACTURER PART") "CC0805KRX7R9BB104")
        (field (name "BOM_SUPPLIER PART") "C49678")
      )
      (libsource (lib "altium-import") (part "root_2_100nF_"))
    )
    (comp (ref "C121")
      (value "100nF")
      (fields
        (field (name "BOM_MANUFACTURER PART") "CC0805KRX7R9BB104")
        (field (name "BOM_SUPPLIER PART") "C49678")
      )
      (libsource (lib "altium-import") (part "root_2_100nF_"))
    )
    (comp (ref "C122")
      (value "100nF")
      (fields
        (field (name "BOM_MANUFACTURER PART") "CC0805KRX7R9BB104")
        (field (name "BOM_SUPPLIER PART") "C49678")
      )
      (libsource (lib "altium-import") (part "root_2_100nF_"))
    )
    (comp (ref "C123")
      (value "100nF")
      (fields
        (field (name "BOM_MANUFACTURER PART") "CC0805KRX7R9BB104")
        (field (name "BOM_SUPPLIER PART") "C49678")
      )
      (libsource (lib "altium-import") (part "root_2_100nF_"))
    )
    (comp (ref "C124")
      (value "100nF")
      (fields
        (field (name "BOM_MANUFACTURER PART") "CC0805KRX7R9BB104")
        (field (name "BOM_SUPPLIER PART") "C49678")
      )
      (libsource (lib "altium-import") (part "root_2_100nF_"))
    )
    (comp (ref "C125")
      (value "100nF")
      (fields
        (field (name "BOM_MANUFACTURER PART") "CC0805KRX7R9BB104")
        (field (name "BOM_SUPPLIER PART") "C49678")
      )
      (libsource (lib "altium-import") (part "root_3_100nF_"))
    )
    (comp (ref "C126")
      (value "100nF")
      (fields
        (field (name "BOM_MANUFACTURER PART") "CC0805KRX7R9BB104")
        (field (name "BOM_SUPPLIER PART") "C49678")
      )
      (libsource (lib "altium-import") (part "root_3_100nF_"))
    )
    (comp (ref "C127")
      (value "100nF")
      (fields
        (field (name "BOM_MANUFACTURER PART") "CC0805KRX7R9BB104")
        (field (name "BOM_SUPPLIER PART") "C49678")
      )
      (libsource (lib "altium-import") (part "root_3_100nF_"))
    )
    (comp (ref "C128")
      (value "100nF")
      (fields
        (field (name "BOM_MANUFACTURER PART") "CC0805KRX7R9BB104")
        (field (name "BOM_SUPPLIER PART") "C49678")
      )
      (libsource (lib "altium-import") (part "root_3_100nF_"))
    )
    (comp (ref "C129")
      (value "100nF")
      (fields
        (field (name "BOM_MANUFACTURER PART") "CC0805KRX7R9BB104")
        (field (name "BOM_SUPPLIER PART") "C49678")
      )
      (libsource (lib "altium-import") (part "root_2_100nF_"))
    )
    (comp (ref "C130")
      (value "100nF")
      (fields
        (field (name "BOM_MANUFACTURER PART") "CC0805KRX7R9BB104")
        (field (name "BOM_SUPPLIER PART") "C49678")
      )
      (libsource (lib "altium-import") (part "root_3_100nF_"))
    )
    (comp (ref "C131")
      (value "100nF")
      (fields
        (field (name "BOM_MANUFACTURER PART") "CC0805KRX7R9BB104")
        (field (name "BOM_SUPPLIER PART") "C49678")
      )
      (libsource (lib "altium-import") (part "root_3_100nF_"))
    )
    (comp (ref "C132")
      (value "100nF")
      (fields
        (field (name "BOM_MANUFACTURER PART") "CC0805KRX7R9BB104")
        (field (name "BOM_SUPPLIER PART") "C49678")
      )
      (libsource (lib "altium-import") (part "root_3_100nF_"))
    )
    (comp (ref "C133")
      (value "100nF")
      (fields
        (field (name "BOM_MANUFACTURER PART") "CC0805KRX7R9BB104")
        (field (name "BOM_SUPPLIER PART") "C49678")
      )
      (libsource (lib "altium-import") (part "root_3_100nF_"))
    )
    (comp (ref "C134")
      (value "10pF")
      (fields
        (field (name "BOM_SUPPLIER PART") "C1785")
        (field (name "BOM_MANUFACTURER PART") "CL21C100JBANNNC")
        (field (name "CONTRIBUTOR") "LCSC")
      )
      (libsource (lib "altium-import") (part "root_2_10pF_"))
    )
    (comp (ref "C135")
      (value "10pF")
      (fields
        (field (name "BOM_SUPPLIER PART") "C1785")
        (field (name "BOM_MANUFACTURER PART") "CL21C100JBANNNC")
        (field (name "CONTRIBUTOR") "LCSC")
      )
      (libsource (lib "altium-import") (part "root_2_10pF_"))
    )
    (comp (ref "C136")
      (value "100nF")
      (fields
        (field (name "BOM_MANUFACTURER PART") "CC0805KRX7R9BB104")
        (field (name "BOM_SUPPLIER PART") "C49678")
      )
      (libsource (lib "altium-import") (part "root_2_100nF_"))
    )
    (comp (ref "D1")
      (value "CD4148WP")
      (fields (field (name "BOM_SUPPLIER PART") "C109000"))
      (libsource (lib "altium-import") (part "root_1_CD4148WP_"))
    )
    (comp (ref "ESPFLASH")
      (value "PTS810SJM250SMTRLFS")
      (fields (field (name "BOM_SUPPLIER PART") "C116501") (field (name "CONTRIBUTOR") "LCSC"))
      (libsource (lib "altium-import") (part "root_2_PTS810SJM250SMTRLFS_"))
    )
    (comp (ref "ESPRST")
      (value "PTS810SJM250SMTRLFS")
      (fields (field (name "BOM_SUPPLIER PART") "C116501") (field (name "CONTRIBUTOR") "LCSC"))
      (libsource (lib "altium-import") (part "root_2_PTS810SJM250SMTRLFS_"))
    )
    (comp (ref "H1")
      (value "Header-Male-2.54_1x3")
      (fields
        (field (name "BOM_MANUFACTURER PART") "Header2.54mm 1*3P")
        (field (name "BOM_SUPPLIER PART") "C49257")
      )
      (libsource (lib "altium-import") (part "root_3_Header-Male-2.54_1x3_"))
    )
    (comp (ref "H2")
      (value "Header-Male-2.54_1x3")
      (fields
        (field (name "BOM_MANUFACTURER PART") "Header2.54mm 1*3P")
        (field (name "BOM_SUPPLIER PART") "C49257")
      )
      (libsource (lib "altium-import") (part "root_1_Header-Male-2.54_1x3_"))
    )
    (comp (ref "H3")
      (value "Header-Male-2.54_1x3")
      (fields
        (field (name "BOM_MANUFACTURER PART") "Header2.54mm 1*3P")
        (field (name "BOM_SUPPLIER PART") "C49257")
      )
      (libsource (lib "altium-import") (part "root_1_Header-Male-2.54_1x3_"))
    )
    (comp (ref "H4")
      (value "Header-Male-2.54_1x3")
      (fields
        (field (name "BOM_MANUFACTURER PART") "Header2.54mm 1*3P")
        (field (name "BOM_SUPPLIER PART") "C49257")
      )
      (libsource (lib "altium-import") (part "root_3_Header-Male-2.54_1x3_"))
    )
    (comp (ref "H5")
      (value "Header-Male-2.54_1x3")
      (fields
        (field (name "BOM_MANUFACTURER PART") "Header2.54mm 1*3P")
        (field (name "BOM_SUPPLIER PART") "C49257")
      )
      (libsource (lib "altium-import") (part "root_1_Header-Male-2.54_1x3_"))
    )
    (comp (ref "H6")
      (value "Header-Male-2.54_1x3")
      (fields
        (field (name "BOM_MANUFACTURER PART") "Header2.54mm 1*3P")
        (field (name "BOM_SUPPLIER PART") "C49257")
      )
      (libsource (lib "altium-import") (part "root_1_Header-Male-2.54_1x3_"))
    )
    (comp (ref "H7")
      (value "Header-Male-2.54_1x3")
      (fields
        (field (name "BOM_MANUFACTURER PART") "Header2.54mm 1*3P")
        (field (name "BOM_SUPPLIER PART") "C49257")
      )
      (libsource (lib "altium-import") (part "root_3_Header-Male-2.54_1x3_"))
    )
    (comp (ref "H8")
      (value "Header-Male-2.54_1x3")
      (fields
        (field (name "BOM_MANUFACTURER PART") "Header2.54mm 1*3P")
        (field (name "BOM_SUPPLIER PART") "C49257")
      )
      (libsource (lib "altium-import") (part "root_3_Header-Male-2.54_1x3_"))
    )
    (comp (ref "H9")
      (value "Header-Male-2.54_1x3")
      (fields
        (field (name "BOM_MANUFACTURER PART") "Header2.54mm 1*3P")
        (field (name "BOM_SUPPLIER PART") "C49257")
      )
      (libsource (lib "altium-import") (part "root_1_Header-Male-2.54_1x3_"))
    )
    (comp (ref "H10")
      (value "Header-Male-2.54_1x3")
      (fields
        (field (name "BOM_MANUFACTURER PART") "Header2.54mm 1*3P")
        (field (name "BOM_SUPPLIER PART") "C49257")
      )
      (libsource (lib "altium-import") (part "root_1_Header-Male-2.54_1x3_"))
    )
    (comp (ref "H11")
      (value "Header-Male-2.54_1x3")
      (fields
        (field (name "BOM_MANUFACTURER PART") "Header2.54mm 1*3P")
        (field (name "BOM_SUPPLIER PART") "C49257")
      )
      (libsource (lib "altium-import") (part "root_3_Header-Male-2.54_1x3_"))
    )
    (comp (ref "H12")
      (value "Header-Male-2.54_1x3")
      (fields
        (field (name "BOM_MANUFACTURER PART") "Header2.54mm 1*3P")
        (field (name "BOM_SUPPLIER PART") "C49257")
      )
      (libsource (lib "altium-import") (part "root_3_Header-Male-2.54_1x3_"))
    )
    (comp (ref "H13")
      (value "Header-Male-2.54_1x3")
      (fields
        (field (name "BOM_MANUFACTURER PART") "Header2.54mm 1*3P")
        (field (name "BOM_SUPPLIER PART") "C49257")
      )
      (libsource (lib "altium-import") (part "root_1_Header-Male-2.54_1x3_"))
    )
    (comp (ref "H14")
      (value "Header-Male-2.54_1x3")
      (fields
        (field (name "BOM_MANUFACTURER PART") "Header2.54mm 1*3P")
        (field (name "BOM_SUPPLIER PART") "C49257")
      )
      (libsource (lib "altium-import") (part "root_1_Header-Male-2.54_1x3_"))
    )
    (comp (ref "H15")
      (value "Header-Male-2.54_1x3")
      (fields
        (field (name "BOM_MANUFACTURER PART") "Header2.54mm 1*3P")
        (field (name "BOM_SUPPLIER PART") "C49257")
      )
      (libsource (lib "altium-import") (part "root_3_Header-Male-2.54_1x3_"))
    )
    (comp (ref "H16")
      (value "Header-Male-2.54_1x3")
      (fields
        (field (name "BOM_MANUFACTURER PART") "Header2.54mm 1*3P")
        (field (name "BOM_SUPPLIER PART") "C49257")
      )
      (libsource (lib "altium-import") (part "root_3_Header-Male-2.54_1x3_"))
    )
    (comp (ref "H17")
      (value "Header-Male-2.54_1x3")
      (fields
        (field (name "BOM_MANUFACTURER PART") "Header2.54mm 1*3P")
        (field (name "BOM_SUPPLIER PART") "C49257")
      )
      (libsource (lib "altium-import") (part "root_1_Header-Male-2.54_1x3_"))
    )
    (comp (ref "H18")
      (value "Header-Male-2.54_1x3")
      (fields
        (field (name "BOM_MANUFACTURER PART") "Header2.54mm 1*3P")
        (field (name "BOM_SUPPLIER PART") "C49257")
      )
      (libsource (lib "altium-import") (part "root_1_Header-Male-2.54_1x3_"))
    )
    (comp (ref "H19")
      (value "Header-Male-2.54_1x3")
      (fields
        (field (name "BOM_MANUFACTURER PART") "Header2.54mm 1*3P")
        (field (name "BOM_SUPPLIER PART") "C49257")
      )
      (libsource (lib "altium-import") (part "root_3_Header-Male-2.54_1x3_"))
    )
    (comp (ref "H20")
      (value "Header-Male-2.54_1x3")
      (fields
        (field (name "BOM_MANUFACTURER PART") "Header2.54mm 1*3P")
        (field (name "BOM_SUPPLIER PART") "C49257")
      )
      (libsource (lib "altium-import") (part "root_3_Header-Male-2.54_1x3_"))
    )
    (comp (ref "H21")
      (value "PWR")
      (fields
        (field (name "BOM_MANUFACTURER PART") "Header2.54mm 1*3P")
        (field (name "BOM_SUPPLIER PART") "C49257")
      )
      (libsource (lib "altium-import") (part "root_2_PWR_"))
    )
    (comp (ref "H22")
      (value "RPI2C")
      (fields
        (field (name "BOM_MANUFACTURER PART") "Header2.54mm 1*3P")
        (field (name "BOM_SUPPLIER PART") "C49257")
      )
      (libsource (lib "altium-import") (part "root_1_RPI2C_"))
    )
    (comp (ref "JP1")
      (value "OEE")
      (fields (field (name "CONTRIBUTOR") "Celeron"))
      (libsource (lib "altium-import") (part "root_2_OEE_"))
    )
    (comp (ref "JP3")
      (value "JUMPER-SMT_2")
      (fields (field (name "CONTRIBUTOR") "Celeron"))
      (libsource (lib "") (part "root_0_JUMPER-SMT_2__1"))
    )
    (comp (ref "JP4")
      (value "5VLSL")
      (fields (field (name "CONTRIBUTOR") "Celeron"))
      (libsource (lib "altium-import") (part "root_3_5VLSL_"))
    )
    (comp (ref "JP6")
      (value "GP22WS")
      (fields (field (name "CONTRIBUTOR") "Celeron"))
      (libsource (lib "altium-import") (part "root_2_GP22WS_"))
    )
    (comp (ref "JP7")
      (value "GP16WS")
      (fields (field (name "CONTRIBUTOR") "Celeron"))
      (libsource (lib "altium-import") (part "root_2_GP16WS_"))
    )
    (comp (ref "JP8")
      (value "JUMPER-SMT_2")
      (fields (field (name "CONTRIBUTOR") "Celeron"))
      (libsource (lib "altium-import") (part "root_0_JUMPER-SMT_2_"))
    )
    (comp (ref "JP10")
      (value "ESPTX")
      (fields (field (name "CONTRIBUTOR") "Celeron"))
      (libsource (lib "altium-import") (part "root_0_ESPTX_"))
    )
    (comp (ref "JP11")
      (value "ESPRX")
      (fields (field (name "CONTRIBUTOR") "Celeron"))
      (libsource (lib "altium-import") (part "root_0_ESPRX_"))
    )
    (comp (ref "LED1")
      (value "WS2812B-B")
      (fields (field (name "BOM_SUPPLIER PART") "C114586") (field (name "CONTRIBUTOR") "LCSC"))
      (libsource (lib "altium-import") (part "root_0_WS2812B-B_"))
    )
    (comp (ref "LED3")
      (value "WS2812B-B")
      (fields (field (name "BOM_SUPPLIER PART") "C114586") (field (name "CONTRIBUTOR") "LCSC"))
      (libsource (lib "altium-import") (part "root_0_WS2812B-B_"))
    )
    (comp (ref "LED4")
      (value "WS2812B-B")
      (fields (field (name "BOM_SUPPLIER PART") "C114586") (field (name "CONTRIBUTOR") "LCSC"))
      (libsource (lib "altium-import") (part "root_2_WS2812B-B_"))
    )
    (comp (ref "LED5")
      (value "WS2812B-B")
      (fields (field (name "BOM_SUPPLIER PART") "C114586") (field (name "CONTRIBUTOR") "LCSC"))
      (libsource (lib "altium-import") (part "root_2_WS2812B-B_"))
    )
    (comp (ref "LED6")
      (value "WS2812B-B")
      (fields (field (name "BOM_SUPPLIER PART") "C114586") (field (name "CONTRIBUTOR") "LCSC"))
      (libsource (lib "altium-import") (part "root_2_WS2812B-B_"))
    )
    (comp (ref "LED7")
      (value "WS2812B-B")
      (fields (field (name "BOM_SUPPLIER PART") "C114586") (field (name "CONTRIBUTOR") "LCSC"))
      (libsource (lib "altium-import") (part "root_2_WS2812B-B_"))
    )
    (comp (ref "LED8")
      (value "WS2812B-B")
      (fields (field (name "BOM_SUPPLIER PART") "C114586") (field (name "CONTRIBUTOR") "LCSC"))
      (libsource (lib "altium-import") (part "root_0_WS2812B-B_"))
    )
    (comp (ref "LED9")
      (value "WS2812B-B")
      (fields (field (name "BOM_SUPPLIER PART") "C114586") (field (name "CONTRIBUTOR") "LCSC"))
      (libsource (lib "altium-import") (part "root_0_WS2812B-B_"))
    )
    (comp (ref "LED10")
      (value "WS2812B-B")
      (fields (field (name "BOM_SUPPLIER PART") "C114586") (field (name "CONTRIBUTOR") "LCSC"))
      (libsource (lib "altium-import") (part "root_0_WS2812B-B_"))
    )
    (comp (ref "LED11")
      (value "WS2812B-B")
      (fields (field (name "BOM_SUPPLIER PART") "C114586") (field (name "CONTRIBUTOR") "LCSC"))
      (libsource (lib "altium-import") (part "root_0_WS2812B-B_"))
    )
    (comp (ref "LED12")
      (value "WS2812B-B")
      (fields (field (name "BOM_SUPPLIER PART") "C114586") (field (name "CONTRIBUTOR") "LCSC"))
      (libsource (lib "altium-import") (part "root_0_WS2812B-B_"))
    )
    (comp (ref "LED13")
      (value "WS2812B-B")
      (fields (field (name "BOM_SUPPLIER PART") "C114586") (field (name "CONTRIBUTOR") "LCSC"))
      (libsource (lib "altium-import") (part "root_0_WS2812B-B_"))
    )
    (comp (ref "LED14")
      (value "WS2812B-B")
      (fields (field (name "BOM_SUPPLIER PART") "C114586") (field (name "CONTRIBUTOR") "LCSC"))
      (libsource (lib "altium-import") (part "root_0_WS2812B-B_"))
    )
    (comp (ref "LED15")
      (value "WS2812B-B")
      (fields (field (name "BOM_SUPPLIER PART") "C114586") (field (name "CONTRIBUTOR") "LCSC"))
      (libsource (lib "altium-import") (part "root_0_WS2812B-B_"))
    )
    (comp (ref "LED16")
      (value "WS2812B-B")
      (fields (field (name "BOM_SUPPLIER PART") "C114586") (field (name "CONTRIBUTOR") "LCSC"))
      (libsource (lib "altium-import") (part "root_0_WS2812B-B_"))
    )
    (comp (ref "LED17")
      (value "WS2812B-B")
      (fields (field (name "BOM_SUPPLIER PART") "C114586") (field (name "CONTRIBUTOR") "LCSC"))
      (libsource (lib "altium-import") (part "root_2_WS2812B-B_"))
    )
    (comp (ref "LED18")
      (value "WS2812B-B")
      (fields (field (name "BOM_SUPPLIER PART") "C114586") (field (name "CONTRIBUTOR") "LCSC"))
      (libsource (lib "altium-import") (part "root_2_WS2812B-B_"))
    )
    (comp (ref "LED19")
      (value "WS2812B-B")
      (fields (field (name "BOM_SUPPLIER PART") "C114586") (field (name "CONTRIBUTOR") "LCSC"))
      (libsource (lib "altium-import") (part "root_2_WS2812B-B_"))
    )
    (comp (ref "LED20")
      (value "WS2812B-B")
      (fields (field (name "BOM_SUPPLIER PART") "C114586") (field (name "CONTRIBUTOR") "LCSC"))
      (libsource (lib "altium-import") (part "root_2_WS2812B-B_"))
    )
    (comp (ref "LED21")
      (value "WS2812B-B")
      (fields (field (name "BOM_SUPPLIER PART") "C114586") (field (name "CONTRIBUTOR") "LCSC"))
      (libsource (lib "altium-import") (part "root_2_WS2812B-B_"))
    )
    (comp (ref "LED22")
      (value "WS2812B-B")
      (fields (field (name "BOM_SUPPLIER PART") "C114586") (field (name "CONTRIBUTOR") "LCSC"))
      (libsource (lib "altium-import") (part "root_2_WS2812B-B_"))
    )
    (comp (ref "LED23")
      (value "WS2812B-B")
      (fields (field (name "BOM_SUPPLIER PART") "C114586") (field (name "CONTRIBUTOR") "LCSC"))
      (libsource (lib "altium-import") (part "root_2_WS2812B-B_"))
    )
    (comp (ref "LED24")
      (value "WS2812B-B")
      (fields (field (name "BOM_SUPPLIER PART") "C114586") (field (name "CONTRIBUTOR") "LCSC"))
      (libsource (lib "altium-import") (part "root_0_WS2812B-B_"))
    )
    (comp (ref "LED25")
      (value "WS2812B-B")
      (fields (field (name "BOM_SUPPLIER PART") "C114586") (field (name "CONTRIBUTOR") "LCSC"))
      (libsource (lib "altium-import") (part "root_0_WS2812B-B_"))
    )
    (comp (ref "LED26")
      (value "WS2812B-B")
      (fields (field (name "BOM_SUPPLIER PART") "C114586") (field (name "CONTRIBUTOR") "LCSC"))
      (libsource (lib "altium-import") (part "root_0_WS2812B-B_"))
    )
    (comp (ref "LED27")
      (value "WS2812B-B")
      (fields (field (name "BOM_SUPPLIER PART") "C114586") (field (name "CONTRIBUTOR") "LCSC"))
      (libsource (lib "altium-import") (part "root_0_WS2812B-B_"))
    )
    (comp (ref "LED28")
      (value "WS2812B-B")
      (fields (field (name "BOM_SUPPLIER PART") "C114586") (field (name "CONTRIBUTOR") "LCSC"))
      (libsource (lib "altium-import") (part "root_0_WS2812B-B_"))
    )
    (comp (ref "LED29")
      (value "WS2812B-B")
      (fields (field (name "BOM_SUPPLIER PART") "C114586") (field (name "CONTRIBUTOR") "LCSC"))
      (libsource (lib "altium-import") (part "root_0_WS2812B-B_"))
    )
    (comp (ref "LED30")
      (value "WS2812B-B")
      (fields (field (name "BOM_SUPPLIER PART") "C114586") (field (name "CONTRIBUTOR") "LCSC"))
      (libsource (lib "altium-import") (part "root_0_WS2812B-B_"))
    )
    (comp (ref "LED31")
      (value "WS2812B-B")
      (fields (field (name "BOM_SUPPLIER PART") "C114586") (field (name "CONTRIBUTOR") "LCSC"))
      (libsource (lib "altium-import") (part "root_0_WS2812B-B_"))
    )
    (comp (ref "LED32")
      (value "WS2812B-B")
      (fields (field (name "BOM_SUPPLIER PART") "C114586") (field (name "CONTRIBUTOR") "LCSC"))
      (libsource (lib "altium-import") (part "root_0_WS2812B-B_"))
    )
    (comp (ref "LED33")
      (value "WS2812B-B")
      (fields (field (name "BOM_SUPPLIER PART") "C114586") (field (name "CONTRIBUTOR") "LCSC"))
      (libsource (lib "altium-import") (part "root_0_WS2812B-B_"))
    )
    (comp (ref "LED34")
      (value "WS2812B-B")
      (fields (field (name "BOM_SUPPLIER PART") "C114586") (field (name "CONTRIBUTOR") "LCSC"))
      (libsource (lib "altium-import") (part "root_0_WS2812B-B_"))
    )
    (comp (ref "LED35")
      (value "WS2812B-B")
      (fields (field (name "BOM_SUPPLIER PART") "C114586") (field (name "CONTRIBUTOR") "LCSC"))
      (libsource (lib "altium-import") (part "root_2_WS2812B-B_"))
    )
    (comp (ref "LED36")
      (value "WS2812B-B")
      (fields (field (name "BOM_SUPPLIER PART") "C114586") (field (name "CONTRIBUTOR") "LCSC"))
      (libsource (lib "altium-import") (part "root_2_WS2812B-B_"))
    )
    (comp (ref "LED37")
      (value "WS2812B-B")
      (fields (field (name "BOM_SUPPLIER PART") "C114586") (field (name "CONTRIBUTOR") "LCSC"))
      (libsource (lib "altium-import") (part "root_2_WS2812B-B_"))
    )
    (comp (ref "LED38")
      (value "WS2812B-B")
      (fields (field (name "BOM_SUPPLIER PART") "C114586") (field (name "CONTRIBUTOR") "LCSC"))
      (libsource (lib "altium-import") (part "root_2_WS2812B-B_"))
    )
    (comp (ref "LED39")
      (value "WS2812B-B")
      (fields (field (name "BOM_SUPPLIER PART") "C114586") (field (name "CONTRIBUTOR") "LCSC"))
      (libsource (lib "altium-import") (part "root_2_WS2812B-B_"))
    )
    (comp (ref "LED40")
      (value "WS2812B-B")
      (fields (field (name "BOM_SUPPLIER PART") "C114586") (field (name "CONTRIBUTOR") "LCSC"))
      (libsource (lib "altium-import") (part "root_2_WS2812B-B_"))
    )
    (comp (ref "LED41")
      (value "WS2812B-B")
      (fields (field (name "BOM_SUPPLIER PART") "C114586") (field (name "CONTRIBUTOR") "LCSC"))
      (libsource (lib "altium-import") (part "root_2_WS2812B-B_"))
    )
    (comp (ref "LED42")
      (value "WS2812B-B")
      (fields (field (name "BOM_SUPPLIER PART") "C114586") (field (name "CONTRIBUTOR") "LCSC"))
      (libsource (lib "altium-import") (part "root_2_WS2812B-B_"))
    )
    (comp (ref "LED43")
      (value "WS2812B-B")
      (fields (field (name "BOM_SUPPLIER PART") "C114586") (field (name "CONTRIBUTOR") "LCSC"))
      (libsource (lib "altium-import") (part "root_2_WS2812B-B_"))
    )
    (comp (ref "LED44")
      (value "WS2812B-B")
      (fields (field (name "BOM_SUPPLIER PART") "C114586") (field (name "CONTRIBUTOR") "LCSC"))
      (libsource (lib "altium-import") (part "root_2_WS2812B-B_"))
    )
    (comp (ref "LED45")
      (value "WS2812B-B")
      (fields (field (name "BOM_SUPPLIER PART") "C114586") (field (name "CONTRIBUTOR") "LCSC"))
      (libsource (lib "altium-import") (part "root_2_WS2812B-B_"))
    )
    (comp (ref "LED46")
      (value "WS2812B-B")
      (fields (field (name "BOM_SUPPLIER PART") "C114586") (field (name "CONTRIBUTOR") "LCSC"))
      (libsource (lib "altium-import") (part "root_0_WS2812B-B_"))
    )
    (comp (ref "LED47")
      (value "WS2812B-B")
      (fields (field (name "BOM_SUPPLIER PART") "C114586") (field (name "CONTRIBUTOR") "LCSC"))
      (libsource (lib "altium-import") (part "root_0_WS2812B-B_"))
    )
    (comp (ref "LED48")
      (value "WS2812B-B")
      (fields (field (name "BOM_SUPPLIER PART") "C114586") (field (name "CONTRIBUTOR") "LCSC"))
      (libsource (lib "altium-import") (part "root_0_WS2812B-B_"))
    )
    (comp (ref "LED49")
      (value "WS2812B-B")
      (fields (field (name "BOM_SUPPLIER PART") "C114586") (field (name "CONTRIBUTOR") "LCSC"))
      (libsource (lib "altium-import") (part "root_0_WS2812B-B_"))
    )
    (comp (ref "LED50")
      (value "WS2812B-B")
      (fields (field (name "BOM_SUPPLIER PART") "C114586") (field (name "CONTRIBUTOR") "LCSC"))
      (libsource (lib "altium-import") (part "root_0_WS2812B-B_"))
    )
    (comp (ref "LED51")
      (value "WS2812B-B")
      (fields (field (name "BOM_SUPPLIER PART") "C114586") (field (name "CONTRIBUTOR") "LCSC"))
      (libsource (lib "altium-import") (part "root_0_WS2812B-B_"))
    )
    (comp (ref "LED52")
      (value "WS2812B-B")
      (fields (field (name "BOM_SUPPLIER PART") "C114586") (field (name "CONTRIBUTOR") "LCSC"))
      (libsource (lib "altium-import") (part "root_0_WS2812B-B_"))
    )
    (comp (ref "LED53")
      (value "WS2812B-B")
      (fields (field (name "BOM_SUPPLIER PART") "C114586") (field (name "CONTRIBUTOR") "LCSC"))
      (libsource (lib "altium-import") (part "root_0_WS2812B-B_"))
    )
    (comp (ref "LED54")
      (value "WS2812B-B")
      (fields (field (name "BOM_SUPPLIER PART") "C114586") (field (name "CONTRIBUTOR") "LCSC"))
      (libsource (lib "altium-import") (part "root_0_WS2812B-B_"))
    )
    (comp (ref "LED55")
      (value "WS2812B-B")
      (fields (field (name "BOM_SUPPLIER PART") "C114586") (field (name "CONTRIBUTOR") "LCSC"))
      (libsource (lib "altium-import") (part "root_0_WS2812B-B_"))
    )
    (comp (ref "LED56")
      (value "WS2812B-B")
      (fields (field (name "BOM_SUPPLIER PART") "C114586") (field (name "CONTRIBUTOR") "LCSC"))
      (libsource (lib "altium-import") (part "root_0_WS2812B-B_"))
    )
    (comp (ref "LED57")
      (value "WS2812B-B")
      (fields (field (name "BOM_SUPPLIER PART") "C114586") (field (name "CONTRIBUTOR") "LCSC"))
      (libsource (lib "altium-import") (part "root_2_WS2812B-B_"))
    )
    (comp (ref "LED58")
      (value "WS2812B-B")
      (fields (field (name "BOM_SUPPLIER PART") "C114586") (field (name "CONTRIBUTOR") "LCSC"))
      (libsource (lib "altium-import") (part "root_2_WS2812B-B_"))
    )
    (comp (ref "LED59")
      (value "WS2812B-B")
      (fields (field (name "BOM_SUPPLIER PART") "C114586") (field (name "CONTRIBUTOR") "LCSC"))
      (libsource (lib "altium-import") (part "root_2_WS2812B-B_"))
    )
    (comp (ref "LED60")
      (value "WS2812B-B")
      (fields (field (name "BOM_SUPPLIER PART") "C114586") (field (name "CONTRIBUTOR") "LCSC"))
      (libsource (lib "altium-import") (part "root_2_WS2812B-B_"))
    )
    (comp (ref "LED61")
      (value "WS2812B-B")
      (fields (field (name "BOM_SUPPLIER PART") "C114586") (field (name "CONTRIBUTOR") "LCSC"))
      (libsource (lib "altium-import") (part "root_2_WS2812B-B_"))
    )
    (comp (ref "LED62")
      (value "WS2812B-B")
      (fields (field (name "BOM_SUPPLIER PART") "C114586") (field (name "CONTRIBUTOR") "LCSC"))
      (libsource (lib "altium-import") (part "root_2_WS2812B-B_"))
    )
    (comp (ref "LED63")
      (value "WS2812B-B")
      (fields (field (name "BOM_SUPPLIER PART") "C114586") (field (name "CONTRIBUTOR") "LCSC"))
      (libsource (lib "altium-import") (part "root_2_WS2812B-B_"))
    )
    (comp (ref "LED64")
      (value "WS2812B-B")
      (fields (field (name "BOM_SUPPLIER PART") "C114586") (field (name "CONTRIBUTOR") "LCSC"))
      (libsource (lib "altium-import") (part "root_2_WS2812B-B_"))
    )
    (comp (ref "LED65")
      (value "WS2812B-B")
      (fields (field (name "BOM_SUPPLIER PART") "C114586") (field (name "CONTRIBUTOR") "LCSC"))
      (libsource (lib "altium-import") (part "root_2_WS2812B-B_"))
    )
    (comp (ref "LED66")
      (value "WS2812B-B")
      (fields (field (name "BOM_SUPPLIER PART") "C114586") (field (name "CONTRIBUTOR") "LCSC"))
      (libsource (lib "altium-import") (part "root_2_WS2812B-B_"))
    )
    (comp (ref "LED67")
      (value "WS2812B-B")
      (fields (field (name "BOM_SUPPLIER PART") "C114586") (field (name "CONTRIBUTOR") "LCSC"))
      (libsource (lib "altium-import") (part "root_2_WS2812B-B_"))
    )
    (comp (ref "LED68")
      (value "WS2812B-B")
      (fields (field (name "BOM_SUPPLIER PART") "C114586") (field (name "CONTRIBUTOR") "LCSC"))
      (libsource (lib "altium-import") (part "root_0_WS2812B-B_"))
    )
    (comp (ref "LED69")
      (value "WS2812B-B")
      (fields (field (name "BOM_SUPPLIER PART") "C114586") (field (name "CONTRIBUTOR") "LCSC"))
      (libsource (lib "altium-import") (part "root_0_WS2812B-B_"))
    )
    (comp (ref "LED70")
      (value "WS2812B-B")
      (fields (field (name "BOM_SUPPLIER PART") "C114586") (field (name "CONTRIBUTOR") "LCSC"))
      (libsource (lib "altium-import") (part "root_0_WS2812B-B_"))
    )
    (comp (ref "LED71")
      (value "WS2812B-B")
      (fields (field (name "BOM_SUPPLIER PART") "C114586") (field (name "CONTRIBUTOR") "LCSC"))
      (libsource (lib "altium-import") (part "root_0_WS2812B-B_"))
    )
    (comp (ref "LED72")
      (value "WS2812B-B")
      (fields (field (name "BOM_SUPPLIER PART") "C114586") (field (name "CONTRIBUTOR") "LCSC"))
      (libsource (lib "altium-import") (part "root_0_WS2812B-B_"))
    )
    (comp (ref "LED73")
      (value "WS2812B-B")
      (fields (field (name "BOM_SUPPLIER PART") "C114586") (field (name "CONTRIBUTOR") "LCSC"))
      (libsource (lib "altium-import") (part "root_0_WS2812B-B_"))
    )
    (comp (ref "LED74")
      (value "WS2812B-B")
      (fields (field (name "BOM_SUPPLIER PART") "C114586") (field (name "CONTRIBUTOR") "LCSC"))
      (libsource (lib "altium-import") (part "root_0_WS2812B-B_"))
    )
    (comp (ref "LED75")
      (value "WS2812B-B")
      (fields (field (name "BOM_SUPPLIER PART") "C114586") (field (name "CONTRIBUTOR") "LCSC"))
      (libsource (lib "altium-import") (part "root_0_WS2812B-B_"))
    )
    (comp (ref "LED76")
      (value "WS2812B-B")
      (fields (field (name "BOM_SUPPLIER PART") "C114586") (field (name "CONTRIBUTOR") "LCSC"))
      (libsource (lib "altium-import") (part "root_0_WS2812B-B_"))
    )
    (comp (ref "LED77")
      (value "WS2812B-B")
      (fields (field (name "BOM_SUPPLIER PART") "C114586") (field (name "CONTRIBUTOR") "LCSC"))
      (libsource (lib "altium-import") (part "root_0_WS2812B-B_"))
    )
    (comp (ref "LED78")
      (value "WS2812B-B")
      (fields (field (name "BOM_SUPPLIER PART") "C114586") (field (name "CONTRIBUTOR") "LCSC"))
      (libsource (lib "altium-import") (part "root_0_WS2812B-B_"))
    )
    (comp (ref "LED79")
      (value "WS2812B-B")
      (fields (field (name "BOM_SUPPLIER PART") "C114586") (field (name "CONTRIBUTOR") "LCSC"))
      (libsource (lib "altium-import") (part "root_2_WS2812B-B_"))
    )
    (comp (ref "LED80")
      (value "WS2812B-B")
      (fields (field (name "BOM_SUPPLIER PART") "C114586") (field (name "CONTRIBUTOR") "LCSC"))
      (libsource (lib "altium-import") (part "root_2_WS2812B-B_"))
    )
    (comp (ref "LED81")
      (value "WS2812B-B")
      (fields (field (name "BOM_SUPPLIER PART") "C114586") (field (name "CONTRIBUTOR") "LCSC"))
      (libsource (lib "altium-import") (part "root_2_WS2812B-B_"))
    )
    (comp (ref "LED82")
      (value "WS2812B-B")
      (fields (field (name "BOM_SUPPLIER PART") "C114586") (field (name "CONTRIBUTOR") "LCSC"))
      (libsource (lib "altium-import") (part "root_2_WS2812B-B_"))
    )
    (comp (ref "LED83")
      (value "WS2812B-B")
      (fields (field (name "BOM_SUPPLIER PART") "C114586") (field (name "CONTRIBUTOR") "LCSC"))
      (libsource (lib "altium-import") (part "root_2_WS2812B-B_"))
    )
    (comp (ref "LED84")
      (value "WS2812B-B")
      (fields (field (name "BOM_SUPPLIER PART") "C114586") (field (name "CONTRIBUTOR") "LCSC"))
      (libsource (lib "altium-import") (part "root_2_WS2812B-B_"))
    )
    (comp (ref "LED85")
      (value "WS2812B-B")
      (fields (field (name "BOM_SUPPLIER PART") "C114586") (field (name "CONTRIBUTOR") "LCSC"))
      (libsource (lib "altium-import") (part "root_2_WS2812B-B_"))
    )
    (comp (ref "LED86")
      (value "WS2812B-B")
      (fields (field (name "BOM_SUPPLIER PART") "C114586") (field (name "CONTRIBUTOR") "LCSC"))
      (libsource (lib "altium-import") (part "root_2_WS2812B-B_"))
    )
    (comp (ref "LED87")
      (value "WS2812B-B")
      (fields (field (name "BOM_SUPPLIER PART") "C114586") (field (name "CONTRIBUTOR") "LCSC"))
      (libsource (lib "altium-import") (part "root_2_WS2812B-B_"))
    )
    (comp (ref "LED88")
      (value "WS2812B-B")
      (fields (field (name "BOM_SUPPLIER PART") "C114586") (field (name "CONTRIBUTOR") "LCSC"))
      (libsource (lib "altium-import") (part "root_2_WS2812B-B_"))
    )
    (comp (ref "LED89")
      (value "WS2812B-B")
      (fields (field (name "BOM_SUPPLIER PART") "C114586") (field (name "CONTRIBUTOR") "LCSC"))
      (libsource (lib "altium-import") (part "root_2_WS2812B-B_"))
    )
    (comp (ref "LED90")
      (value "WS2812B-B")
      (fields (field (name "BOM_SUPPLIER PART") "C114586") (field (name "CONTRIBUTOR") "LCSC"))
      (libsource (lib "altium-import") (part "root_0_WS2812B-B_"))
    )
    (comp (ref "LED91")
      (value "WS2812B-B")
      (fields (field (name "BOM_SUPPLIER PART") "C114586") (field (name "CONTRIBUTOR") "LCSC"))
      (libsource (lib "altium-import") (part "root_0_WS2812B-B_"))
    )
    (comp (ref "LED92")
      (value "WS2812B-B")
      (fields (field (name "BOM_SUPPLIER PART") "C114586") (field (name "CONTRIBUTOR") "LCSC"))
      (libsource (lib "altium-import") (part "root_0_WS2812B-B_"))
    )
    (comp (ref "LED93")
      (value "WS2812B-B")
      (fields (field (name "BOM_SUPPLIER PART") "C114586") (field (name "CONTRIBUTOR") "LCSC"))
      (libsource (lib "altium-import") (part "root_0_WS2812B-B_"))
    )
    (comp (ref "LED94")
      (value "WS2812B-B")
      (fields (field (name "BOM_SUPPLIER PART") "C114586") (field (name "CONTRIBUTOR") "LCSC"))
      (libsource (lib "altium-import") (part "root_0_WS2812B-B_"))
    )
    (comp (ref "LED95")
      (value "WS2812B-B")
      (fields (field (name "BOM_SUPPLIER PART") "C114586") (field (name "CONTRIBUTOR") "LCSC"))
      (libsource (lib "altium-import") (part "root_0_WS2812B-B_"))
    )
    (comp (ref "LED96")
      (value "WS2812B-B")
      (fields (field (name "BOM_SUPPLIER PART") "C114586") (field (name "CONTRIBUTOR") "LCSC"))
      (libsource (lib "altium-import") (part "root_0_WS2812B-B_"))
    )
    (comp (ref "LED97")
      (value "WS2812B-B")
      (fields (field (name "BOM_SUPPLIER PART") "C114586") (field (name "CONTRIBUTOR") "LCSC"))
      (libsource (lib "altium-import") (part "root_0_WS2812B-B_"))
    )
    (comp (ref "LED98")
      (value "WS2812B-B")
      (fields (field (name "BOM_SUPPLIER PART") "C114586") (field (name "CONTRIBUTOR") "LCSC"))
      (libsource (lib "altium-import") (part "root_0_WS2812B-B_"))
    )
    (comp (ref "LED99")
      (value "WS2812B-B")
      (fields (field (name "BOM_SUPPLIER PART") "C114586") (field (name "CONTRIBUTOR") "LCSC"))
      (libsource (lib "altium-import") (part "root_0_WS2812B-B_"))
    )
    (comp (ref "LED100")
      (value "WS2812B-B")
      (fields (field (name "BOM_SUPPLIER PART") "C114586") (field (name "CONTRIBUTOR") "LCSC"))
      (libsource (lib "altium-import") (part "root_0_WS2812B-B_"))
    )
    (comp (ref "LED101")
      (value "WS2812B-B")
      (fields (field (name "BOM_SUPPLIER PART") "C114586") (field (name "CONTRIBUTOR") "LCSC"))
      (libsource (lib "altium-import") (part "root_2_WS2812B-B_"))
    )
    (comp (ref "LED102")
      (value "WS2812B-B")
      (fields (field (name "BOM_SUPPLIER PART") "C114586") (field (name "CONTRIBUTOR") "LCSC"))
      (libsource (lib "altium-import") (part "root_2_WS2812B-B_"))
    )
    (comp (ref "LED103")
      (value "WS2812B-B")
      (fields (field (name "BOM_SUPPLIER PART") "C114586") (field (name "CONTRIBUTOR") "LCSC"))
      (libsource (lib "altium-import") (part "root_2_WS2812B-B_"))
    )
    (comp (ref "LED104")
      (value "WS2812B-B")
      (fields (field (name "BOM_SUPPLIER PART") "C114586") (field (name "CONTRIBUTOR") "LCSC"))
      (libsource (lib "altium-import") (part "root_2_WS2812B-B_"))
    )
    (comp (ref "LED105")
      (value "WS2812B-B")
      (fields (field (name "BOM_SUPPLIER PART") "C114586") (field (name "CONTRIBUTOR") "LCSC"))
      (libsource (lib "altium-import") (part "root_2_WS2812B-B_"))
    )
    (comp (ref "LED106")
      (value "WS2812B-B")
      (fields (field (name "BOM_SUPPLIER PART") "C114586") (field (name "CONTRIBUTOR") "LCSC"))
      (libsource (lib "altium-import") (part "root_2_WS2812B-B_"))
    )
    (comp (ref "LED107")
      (value "WS2812B-B")
      (fields (field (name "BOM_SUPPLIER PART") "C114586") (field (name "CONTRIBUTOR") "LCSC"))
      (libsource (lib "altium-import") (part "root_2_WS2812B-B_"))
    )
    (comp (ref "LED108")
      (value "WS2812B-B")
      (fields (field (name "BOM_SUPPLIER PART") "C114586") (field (name "CONTRIBUTOR") "LCSC"))
      (libsource (lib "altium-import") (part "root_2_WS2812B-B_"))
    )
    (comp (ref "LED109")
      (value "WS2812B-B")
      (fields (field (name "BOM_SUPPLIER PART") "C114586") (field (name "CONTRIBUTOR") "LCSC"))
      (libsource (lib "altium-import") (part "root_2_WS2812B-B_"))
    )
    (comp (ref "LED110")
      (value "WS2812B-B")
      (fields (field (name "BOM_SUPPLIER PART") "C114586") (field (name "CONTRIBUTOR") "LCSC"))
      (libsource (lib "altium-import") (part "root_2_WS2812B-B_"))
    )
    (comp (ref "LED111")
      (value "WS2812B-B")
      (fields (field (name "BOM_SUPPLIER PART") "C114586") (field (name "CONTRIBUTOR") "LCSC"))
      (libsource (lib "altium-import") (part "root_2_WS2812B-B_"))
    )
    (comp (ref "LED112")
      (value "WS2812B-B")
      (fields (field (name "BOM_SUPPLIER PART") "C114586") (field (name "CONTRIBUTOR") "LCSC"))
      (libsource (lib "altium-import") (part "root_2_WS2812B-B_"))
    )
    (comp (ref "LED113")
      (value "WS2812B-B")
      (fields (field (name "BOM_SUPPLIER PART") "C114586") (field (name "CONTRIBUTOR") "LCSC"))
      (libsource (lib "altium-import") (part "root_2_WS2812B-B_"))
    )
    (comp (ref "LED114")
      (value "WS2812B-B")
      (fields (field (name "BOM_SUPPLIER PART") "C114586") (field (name "CONTRIBUTOR") "LCSC"))
      (libsource (lib "altium-import") (part "root_2_WS2812B-B_"))
    )
    (comp (ref "LED115")
      (value "WS2812B-B")
      (fields (field (name "BOM_SUPPLIER PART") "C114586") (field (name "CONTRIBUTOR") "LCSC"))
      (libsource (lib "altium-import") (part "root_2_WS2812B-B_"))
    )
    (comp (ref "LED116")
      (value "FC-2012HRK-620D")
      (fields (field (name "BOM_SUPPLIER PART") "C84256"))
      (libsource (lib "altium-import") (part "root_2_FC-2012HRK-620D_"))
    )
    (comp (ref "P1")
      (value "RPSWD")
      (fields
        (field (name "BOM_MANUFACTURER PART") "Female header1*5P")
        (field (name "BOM_SUPPLIER PART") "C66508")
      )
      (libsource (lib "altium-import") (part "root_1_RPSWD_"))
    )
    (comp (ref "P2")
      (value "ESPPROG")
      (fields
        (field (name "BOM_MANUFACTURER PART") "Female header1*5P")
        (field (name "BOM_SUPPLIER PART") "C66508")
      )
      (libsource (lib "altium-import") (part "root_1_ESPPROG_"))
    )
    (comp (ref "QBOOT")
      (value "PTS810SJM250SMTRLFS")
      (fields (field (name "BOM_SUPPLIER PART") "C116501") (field (name "CONTRIBUTOR") "LCSC"))
      (libsource (lib "altium-import") (part "root_0_PTS810SJM250SMTRLFS_"))
    )
    (comp (ref "QU1")
      (value "RP2040")
      (fields (field (name "BOM_SUPPLIER PART") "C2040") (field (name "CONTRIBUTOR") "LCSC"))
      (libsource (lib "altium-import") (part "root_0_RP2040_"))
    )
    (comp (ref "QU2")
      (value "W25Q128JWPIQ")
      (fields (field (name "BOM_SUPPLIER PART") "C2689660") (field (name "CONTRIBUTOR") "LCSC"))
      (libsource (lib "altium-import") (part "root_0_W25Q128JWPIQ_"))
    )
    (comp (ref "QX1")
      (value "12MHz")
      (fields
        (field (name "BOM_MANUFACTURER PART") "X322512MSB4SI")
        (field (name "BOM_SUPPLIER PART") "C9002")
        (field (name "CONTRIBUTOR") "LCSC")
      )
      (libsource (lib "altium-import") (part "root_0_12MHz_"))
    )
    (comp (ref "R1")
      (value "4.7K")
      (fields
        (field (name "BOM_SUPPLIER PART") "C17673")
        (field (name "BOM_MANUFACTURER PART") "0805W8F4701T5E")
        (field (name "CONTRIBUTOR") "LCSC")
      )
      (libsource (lib "altium-import") (part "root_3_4.7K_"))
    )
    (comp (ref "R2")
      (value "1kΩ")
      (fields
        (field (name "BOM_SUPPLIER PART") "C17513")
        (field (name "BOM_MANUFACTURER PART") "0805W8F1001T5E")
        (field (name "CONTRIBUTOR") "LCSC")
      )
      (libsource (lib "altium-import") (part "root_1_1kΩ_"))
    )
    (comp (ref "R3")
      (value "4.7K")
      (fields
        (field (name "BOM_SUPPLIER PART") "C17673")
        (field (name "BOM_MANUFACTURER PART") "0805W8F4701T5E")
        (field (name "CONTRIBUTOR") "LCSC")
      )
      (libsource (lib "altium-import") (part "root_0_4.7K_"))
    )
    (comp (ref "R4")
      (value "4.7K")
      (fields
        (field (name "BOM_SUPPLIER PART") "C17673")
        (field (name "BOM_MANUFACTURER PART") "0805W8F4701T5E")
        (field (name "CONTRIBUTOR") "LCSC")
      )
      (libsource (lib "altium-import") (part "root_0_4.7K_"))
    )
    (comp (ref "R5")
      (value "10K")
      (fields
        (field (name "BOM_MANUFACTURER PART") "0805W8F1002T5E")
        (field (name "BOM_SUPPLIER PART") "C17414")
      )
      (libsource (lib "altium-import") (part "root_1_10K_"))
    )
    (comp (ref "R6")
      (value "10K")
      (fields
        (field (name "BOM_MANUFACTURER PART") "0805W8F1002T5E")
        (field (name "BOM_SUPPLIER PART") "C17414")
      )
      (libsource (lib "altium-import") (part "root_2_10K_"))
    )
    (comp (ref "R7")
      (value "27Ω")
      (fields
        (field (name "BOM_SUPPLIER PART") "C17594")
        (field (name "BOM_MANUFACTURER PART") "0805W8F270JT5E")
        (field (name "CONTRIBUTOR") "LCSC")
      )
      (libsource (lib "altium-import") (part "root_0_27Ω_"))
    )
    (comp (ref "R8")
      (value "10K")
      (fields
        (field (name "BOM_MANUFACTURER PART") "0805W8F1002T5E")
        (field (name "BOM_SUPPLIER PART") "C17414")
      )
      (libsource (lib "altium-import") (part "root_2_10K_"))
    )
    (comp (ref "R9")
      (value "27Ω")
      (fields
        (field (name "BOM_SUPPLIER PART") "C17594")
        (field (name "BOM_MANUFACTURER PART") "0805W8F270JT5E")
        (field (name "CONTRIBUTOR") "LCSC")
      )
      (libsource (lib "altium-import") (part "root_0_27Ω_"))
    )
    (comp (ref "R10")
      (value "50")
      (fields
        (field (name "BOM_MANUFACTURER PART") "0805W8F1002T5E")
        (field (name "BOM_SUPPLIER PART") "C17414")
      )
      (libsource (lib "altium-import") (part "root_0_50_"))
    )
    (comp (ref "R11")
      (value "1K")
      (fields
        (field (name "BOM_MANUFACTURER PART") "0805W8F1001T5E")
        (field (name "BOM_SUPPLIER PART") "C17513")
      )
      (libsource (lib "altium-import") (part "root_2_1K_"))
    )
    (comp (ref "R12")
      (value "1K")
      (fields
        (field (name "BOM_MANUFACTURER PART") "0805W8F1001T5E")
        (field (name "BOM_SUPPLIER PART") "C17513")
      )
      (libsource (lib "altium-import") (part "root_2_1K_"))
    )
    (comp (ref "R13")
      (value "100Ω")
      (fields
        (field (name "BOM_SUPPLIER PART") "C17408")
        (field (name "BOM_MANUFACTURER PART") "0805W8F1000T5E")
        (field (name "CONTRIBUTOR") "LCSC")
      )
      (libsource (lib "altium-import") (part "root_0_100Ω_"))
    )
    (comp (ref "R14")
      (value "10K")
      (fields
        (field (name "BOM_MANUFACTURER PART") "0805W8F1002T5E")
        (field (name "BOM_SUPPLIER PART") "C17414")
      )
      (libsource (lib "altium-import") (part "root_2_10K_"))
    )
    (comp (ref "R15")
      (value "10K")
      (fields
        (field (name "BOM_MANUFACTURER PART") "0805W8F1002T5E")
        (field (name "BOM_SUPPLIER PART") "C17414")
      )
      (libsource (lib "altium-import") (part "root_0_10K_"))
    )
    (comp (ref "R16")
      (value "10K")
      (fields
        (field (name "BOM_MANUFACTURER PART") "0805W8F1002T5E")
        (field (name "BOM_SUPPLIER PART") "C17414")
      )
      (libsource (lib "altium-import") (part "root_0_10K_"))
    )
    (comp (ref "RPRST")
      (value "PTS810SJM250SMTRLFS")
      (fields (field (name "BOM_SUPPLIER PART") "C116501") (field (name "CONTRIBUTOR") "LCSC"))
      (libsource (lib "altium-import") (part "root_0_PTS810SJM250SMTRLFS_"))
    )
    (comp (ref "RPUSB")
      (value "HDR-M-2.54_1x4")
      (fields (field (name "BOM_SUPPLIER PART") "C124378") (field (name "CONTRIBUTOR") "LCEDA_Lib"))
      (libsource (lib "altium-import") (part "root_1_HDR-M-2.54_1x4_"))
    )
    (comp (ref "U1")
      (value "BH1750FVI-TR")
      (fields (field (name "BOM_SUPPLIER PART") "C78960"))
      (libsource (lib "altium-import") (part "root_0_BH1750FVI-TR_"))
    )
    (comp (ref "U2")
      (value "AMS1117-3.3")
      (fields (field (name "BOM_SUPPLIER PART") "C6186"))
      (libsource (lib "altium-import") (part "root_0_AMS1117-3.3_"))
    )
    (comp (ref "U3")
      (value "PCF85263ATL/AX")
      (fields (field (name "BOM_SUPPLIER PART") "C2651523") (field (name "CONTRIBUTOR") "LCSC"))
      (libsource (lib "altium-import") (part "root_0_PCF85263ATL/AX_"))
    )
    (comp (ref "U4")
      (value "M24C02-WMN6TP")
      (fields (field (name "BOM_SUPPLIER PART") "C7562"))
      (libsource (lib "altium-import") (part "root_0_M24C02-WMN6TP_"))
    )
    (comp (ref "U5")
      (value "ESP-12F(ESP8266MOD)")
      (fields (field (name "BOM_SUPPLIER PART") "C82891"))
      (libsource (lib "altium-import") (part "root_0_ESP-12F(ESP8266MOD)_"))
    )
    (comp (ref "U6")
      (value "TXB0101DBVT")
      (fields (field (name "BOM_SUPPLIER PART") "C2677627") (field (name "CONTRIBUTOR") "LCSC"))
      (libsource (lib "altium-import") (part "root_0_TXB0101DBVT_"))
    )
    (comp (ref "X1")
      (value "CFV206-60.003KDZF")
      (fields (field (name "BOM_SUPPLIER PART") "C389957") (field (name "CONTRIBUTOR") "LCSC"))
      (libsource (lib "altium-import") (part "root_3_CFV206-60.003KDZF_"))
    )
  )
  (nets
    (net (code "1") (name "+1V1") (class "Default")
      (node (ref "C123") (pin "1") (pinfunction "1_1") (pintype "passive"))
      (node (ref "C124") (pin "1") (pinfunction "1_1") (pintype "passive"))
      (node (ref "QU1") (pin "23") (pinfunction "DVDD_23") (pintype "passive"))
      (node (ref "QU1") (pin "45") (pinfunction "VREG_VOUT_45") (pintype "passive"))
      (node (ref "QU1") (pin "50") (pinfunction "DVDD_50") (pintype "passive"))
    )
    (net (code "2") (name "+5V") (class "Default")
      (node (ref "C1") (pin "1") (pinfunction "1_1") (pintype "passive"))
      (node (ref "C100") (pin "1") (pinfunction "1_1") (pintype "passive"))
      (node (ref "C101") (pin "1") (pinfunction "1_1") (pintype "passive"))
      (node (ref "C102") (pin "1") (pinfunction "1_1") (pintype "passive"))
      (node (ref "C103") (pin "1") (pinfunction "1_1") (pintype "passive"))
      (node (ref "C104") (pin "1") (pinfunction "1_1") (pintype "passive"))
      (node (ref "C105") (pin "1") (pinfunction "1_1") (pintype "passive"))
      (node (ref "C106") (pin "1") (pinfunction "1_1") (pintype "passive"))
      (node (ref "C107") (pin "1") (pinfunction "1_1") (pintype "passive"))
      (node (ref "C108") (pin "1") (pinfunction "1_1") (pintype "passive"))
      (node (ref "C109") (pin "1") (pinfunction "1_1") (pintype "passive"))
      (node (ref "C11") (pin "1") (pinfunction "1_1") (pintype "passive"))
      (node (ref "C110") (pin "1") (pinfunction "1_1") (pintype "passive"))
      (node (ref "C111") (pin "1") (pinfunction "1_1") (pintype "passive"))
      (node (ref "C112") (pin "1") (pinfunction "1_1") (pintype "passive"))
      (node (ref "C113") (pin "1") (pinfunction "1_1") (pintype "passive"))
      (node (ref "C114") (pin "1") (pinfunction "1_1") (pintype "passive"))
      (node (ref "C115") (pin "1") (pinfunction "1_1") (pintype "passive"))
      (node (ref "C116") (pin "1") (pinfunction "1_1") (pintype "passive"))
      (node (ref "C117") (pin "1") (pinfunction "1_1") (pintype "passive"))
      (node (ref "C118") (pin "1") (pinfunction "1_1") (pintype "passive"))
      (node (ref "C119") (pin "1") (pinfunction "1_1") (pintype "passive"))
      (node (ref "C12") (pin "1") (pinfunction "1_1") (pintype "passive"))
      (node (ref "C120") (pin "1") (pinfunction "1_1") (pintype "passive"))
      (node (ref "C121") (pin "1") (pinfunction "1_1") (pintype "passive"))
      (node (ref "C13") (pin "1") (pinfunction "1_1") (pintype "passive"))
      (node (ref "C14") (pin "1") (pinfunction "1_1") (pintype "passive"))
      (node (ref "C15") (pin "1") (pinfunction "1_1") (pintype "passive"))
      (node (ref "C16") (pin "1") (pinfunction "1_1") (pintype "passive"))
      (node (ref "C17") (pin "1") (pinfunction "1_1") (pintype "passive"))
      (node (ref "C18") (pin "1") (pinfunction "1_1") (pintype "passive"))
      (node (ref "C19") (pin "1") (pinfunction "1_1") (pintype "passive"))
      (node (ref "C2") (pin "2") (pinfunction "2_2") (pintype "passive"))
      (node (ref "C20") (pin "1") (pinfunction "1_1") (pintype "passive"))
      (node (ref "C21") (pin "1") (pinfunction "1_1") (pintype "passive"))
      (node (ref "C22") (pin "1") (pinfunction "1_1") (pintype "passive"))
      (node (ref "C23") (pin "1") (pinfunction "1_1") (pintype "passive"))
      (node (ref "C24") (pin "1") (pinfunction "1_1") (pintype "passive"))
      (node (ref "C25") (pin "1") (pinfunction "1_1") (pintype "passive"))
      (node (ref "C26") (pin "1") (pinfunction "1_1") (pintype "passive"))
      (node (ref "C27") (pin "1") (pinfunction "1_1") (pintype "passive"))
      (node (ref "C28") (pin "1") (pinfunction "1_1") (pintype "passive"))
      (node (ref "C29") (pin "1") (pinfunction "1_1") (pintype "passive"))
      (node (ref "C30") (pin "1") (pinfunction "1_1") (pintype "passive"))
      (node (ref "C31") (pin "1") (pinfunction "1_1") (pintype "passive"))
      (node (ref "C32") (pin "1") (pinfunction "1_1") (pintype "passive"))
      (node (ref "C33") (pin "1") (pinfunction "1_1") (pintype "passive"))
      (node (ref "C34") (pin "1") (pinfunction "1_1") (pintype "passive"))
      (node (ref "C35") (pin "1") (pinfunction "1_1") (pintype "passive"))
      (node (ref "C36") (pin "1") (pinfunction "1_1") (pintype "passive"))
      (node (ref "C37") (pin "1") (pinfunction "1_1") (pintype "passive"))
      (node (ref "C38") (pin "1") (pinfunction "1_1") (pintype "passive"))
      (node (ref "C39") (pin "1") (pinfunction "1_1") (pintype "passive"))
      (node (ref "C40") (pin "1") (pinfunction "1_1") (pintype "passive"))
      (node (ref "C41") (pin "1") (pinfunction "1_1") (pintype "passive"))
      (node (ref "C42") (pin "1") (pinfunction "1_1") (pintype "passive"))
      (node (ref "C43") (pin "1") (pinfunction "1_1") (pintype "passive"))
      (node (ref "C44") (pin "1") (pinfunction "1_1") (pintype "passive"))
      (node (ref "C45") (pin "1") (pinfunction "1_1") (pintype "passive"))
      (node (ref "C46") (pin "1") (pinfunction "1_1") (pintype "passive"))
      (node (ref "C47") (pin "1") (pinfunction "1_1") (pintype "passive"))
      (node (ref "C48") (pin "1") (pinfunction "1_1") (pintype "passive"))
      (node (ref "C49") (pin "1") (pinfunction "1_1") (pintype "passive"))
      (node (ref "C5") (pin "1") (pinfunction "1_1") (pintype "passive"))
      (node (ref "C50") (pin "1") (pinfunction "1_1") (pintype "passive"))
      (node (ref "C51") (pin "1") (pinfunction "1_1") (pintype "passive"))
      (node (ref "C52") (pin "1") (pinfunction "1_1") (pintype "passive"))
      (node (ref "C53") (pin "1") (pinfunction "1_1") (pintype "passive"))
      (node (ref "C54") (pin "1") (pinfunction "1_1") (pintype "passive"))
      (node (ref "C55") (pin "1") (pinfunction "1_1") (pintype "passive"))
      (node (ref "C56") (pin "1") (pinfunction "1_1") (pintype "passive"))
      (node (ref "C57") (pin "1") (pinfunction "1_1") (pintype "passive"))
      (node (ref "C58") (pin "1") (pinfunction "1_1") (pintype "passive"))
      (node (ref "C59") (pin "1") (pinfunction "1_1") (pintype "passive"))
      (node (ref "C60") (pin "1") (pinfunction "1_1") (pintype "passive"))
      (node (ref "C61") (pin "1") (pinfunction "1_1") (pintype "passive"))
      (node (ref "C62") (pin "1") (pinfunction "1_1") (pintype "passive"))
      (node (ref "C63") (pin "1") (pinfunction "1_1") (pintype "passive"))
      (node (ref "C64") (pin "1") (pinfunction "1_1") (pintype "passive"))
      (node (ref "C65") (pin "1") (pinfunction "1_1") (pintype "passive"))
      (node (ref "C66") (pin "1") (pinfunction "1_1") (pintype "passive"))
      (node (ref "C67") (pin "1") (pinfunction "1_1") (pintype "passive"))
      (node (ref "C68") (pin "1") (pinfunction "1_1") (pintype "passive"))
      (node (ref "C69") (pin "1") (pinfunction "1_1") (pintype "passive"))
      (node (ref "C70") (pin "1") (pinfunction "1_1") (pintype "passive"))
      (node (ref "C71") (pin "1") (pinfunction "1_1") (pintype "passive"))
      (node (ref "C72") (pin "1") (pinfunction "1_1") (pintype "passive"))
      (node (ref "C73") (pin "1") (pinfunction "1_1") (pintype "passive"))
      (node (ref "C74") (pin "1") (pinfunction "1_1") (pintype "passive"))
      (node (ref "C75") (pin "1") (pinfunction "1_1") (pintype "passive"))
      (node (ref "C76") (pin "1") (pinfunction "1_1") (pintype "passive"))
      (node (ref "C77") (pin "1") (pinfunction "1_1") (pintype "passive"))
      (node (ref "C78") (pin "1") (pinfunction "1_1") (pintype "passive"))
      (node (ref "C79") (pin "1") (pinfunction "1_1") (pintype "passive"))
      (node (ref "C8") (pin "1") (pinfunction "1_1") (pintype "passive"))
      (node (ref "C80") (pin "1") (pinfunction "1_1") (pintype "passive"))
      (node (ref "C81") (pin "1") (pinfunction "1_1") (pintype "passive"))
      (node (ref "C82") (pin "1") (pinfunction "1_1") (pintype "passive"))
      (node (ref "C83") (pin "1") (pinfunction "1_1") (pintype "passive"))
      (node (ref "C84") (pin "1") (pinfunction "1_1") (pintype "passive"))
      (node (ref "C85") (pin "1") (pinfunction "1_1") (pintype "passive"))
      (node (ref "C86") (pin "1") (pinfunction "1_1") (pintype "passive"))
      (node (ref "C87") (pin "1") (pinfunction "1_1") (pintype "passive"))
      (node (ref "C88") (pin "1") (pinfunction "1_1") (pintype "passive"))
      (node (ref "C89") (pin "1") (pinfunction "1_1") (pintype "passive"))
      (node (ref "C90") (pin "1") (pinfunction "1_1") (pintype "passive"))
      (node (ref "C91") (pin "1") (pinfunction "1_1") (pintype "passive"))
      (node (ref "C92") (pin "1") (pinfunction "1_1") (pintype "passive"))
      (node (ref "C93") (pin "1") (pinfunction "1_1") (pintype "passive"))
      (node (ref "C94") (pin "1") (pinfunction "1_1") (pintype "passive"))
      (node (ref "C95") (pin "1") (pinfunction "1_1") (pintype "passive"))
      (node (ref "C96") (pin "1") (pinfunction "1_1") (pintype "passive"))
      (node (ref "C97") (pin "1") (pinfunction "1_1") (pintype "passive"))
      (node (ref "C98") (pin "1") (pinfunction "1_1") (pintype "passive"))
      (node (ref "C99") (pin "1") (pinfunction "1_1") (pintype "passive"))
      (node (ref "D1") (pin "2") (pinfunction "A_2") (pintype "passive"))
      (node (ref "H1") (pin "1") (pinfunction "1_1") (pintype "passive"))
      (node (ref "H10") (pin "1") (pinfunction "1_1") (pintype "passive"))
      (node (ref "H11") (pin "1") (pinfunction "1_1") (pintype "passive"))
      (node (ref "H12") (pin "1") (pinfunction "1_1") (pintype "passive"))
      (node (ref "H13") (pin "1") (pinfunction "1_1") (pintype "passive"))
      (node (ref "H14") (pin "1") (pinfunction "1_1") (pintype "passive"))
      (node (ref "H15") (pin "1") (pinfunction "1_1") (pintype "passive"))
      (node (ref "H16") (pin "1") (pinfunction "1_1") (pintype "passive"))
      (node (ref "H17") (pin "1") (pinfunction "1_1") (pintype "passive"))
      (node (ref "H18") (pin "1") (pinfunction "1_1") (pintype "passive"))
      (node (ref "H19") (pin "1") (pinfunction "1_1") (pintype "passive"))
      (node (ref "H2") (pin "1") (pinfunction "1_1") (pintype "passive"))
      (node (ref "H20") (pin "1") (pinfunction "1_1") (pintype "passive"))
      (node (ref "H21") (pin "1") (pinfunction "1_1") (pintype "passive"))
      (node (ref "H3") (pin "1") (pinfunction "1_1") (pintype "passive"))
      (node (ref "H4") (pin "1") (pinfunction "1_1") (pintype "passive"))
      (node (ref "H5") (pin "1") (pinfunction "1_1") (pintype "passive"))
      (node (ref "H6") (pin "1") (pinfunction "1_1") (pintype "passive"))
      (node (ref "H7") (pin "1") (pinfunction "1_1") (pintype "passive"))
      (node (ref "H8") (pin "1") (pinfunction "1_1") (pintype "passive"))
      (node (ref "H9") (pin "1") (pinfunction "1_1") (pintype "passive"))
      (node (ref "JP4") (pin "1") (pinfunction "1_1") (pintype "passive"))
      (node (ref "LED1") (pin "1") (pinfunction "VDD_1") (pintype "passive"))
      (node (ref "LED10") (pin "1") (pinfunction "VDD_1") (pintype "passive"))
      (node (ref "LED100") (pin "1") (pinfunction "VDD_1") (pintype "passive"))
      (node (ref "LED101") (pin "1") (pinfunction "VDD_1") (pintype "passive"))
      (node (ref "LED102") (pin "1") (pinfunction "VDD_1") (pintype "passive"))
      (node (ref "LED103") (pin "1") (pinfunction "VDD_1") (pintype "passive"))
      (node (ref "LED104") (pin "1") (pinfunction "VDD_1") (pintype "passive"))
      (node (ref "LED105") (pin "1") (pinfunction "VDD_1") (pintype "passive"))
      (node (ref "LED106") (pin "1") (pinfunction "VDD_1") (pintype "passive"))
      (node (ref "LED107") (pin "1") (pinfunction "VDD_1") (pintype "passive"))
      (node (ref "LED108") (pin "1") (pinfunction "VDD_1") (pintype "passive"))
      (node (ref "LED109") (pin "1") (pinfunction "VDD_1") (pintype "passive"))
      (node (ref "LED11") (pin "1") (pinfunction "VDD_1") (pintype "passive"))
      (node (ref "LED110") (pin "1") (pinfunction "VDD_1") (pintype "passive"))
      (node (ref "LED111") (pin "1") (pinfunction "VDD_1") (pintype "passive"))
      (node (ref "LED112") (pin "1") (pinfunction "VDD_1") (pintype "passive"))
      (node (ref "LED113") (pin "1") (pinfunction "VDD_1") (pintype "passive"))
      (node (ref "LED114") (pin "1") (pinfunction "VDD_1") (pintype "passive"))
      (node (ref "LED12") (pin "1") (pinfunction "VDD_1") (pintype "passive"))
      (node (ref "LED13") (pin "1") (pinfunction "VDD_1") (pintype "passive"))
      (node (ref "LED14") (pin "1") (pinfunction "VDD_1") (pintype "passive"))
      (node (ref "LED15") (pin "1") (pinfunction "VDD_1") (pintype "passive"))
      (node (ref "LED16") (pin "1") (pinfunction "VDD_1") (pintype "passive"))
      (node (ref "LED17") (pin "1") (pinfunction "VDD_1") (pintype "passive"))
      (node (ref "LED18") (pin "1") (pinfunction "VDD_1") (pintype "passive"))
      (node (ref "LED19") (pin "1") (pinfunction "VDD_1") (pintype "passive"))
      (node (ref "LED20") (pin "1") (pinfunction "VDD_1") (pintype "passive"))
      (node (ref "LED21") (pin "1") (pinfunction "VDD_1") (pintype "passive"))
      (node (ref "LED22") (pin "1") (pinfunction "VDD_1") (pintype "passive"))
      (node (ref "LED23") (pin "1") (pinfunction "VDD_1") (pintype "passive"))
      (node (ref "LED24") (pin "1") (pinfunction "VDD_1") (pintype "passive"))
      (node (ref "LED25") (pin "1") (pinfunction "VDD_1") (pintype "passive"))
      (node (ref "LED26") (pin "1") (pinfunction "VDD_1") (pintype "passive"))
      (node (ref "LED27") (pin "1") (pinfunction "VDD_1") (pintype "passive"))
      (node (ref "LED28") (pin "1") (pinfunction "VDD_1") (pintype "passive"))
      (node (ref "LED29") (pin "1") (pinfunction "VDD_1") (pintype "passive"))
      (node (ref "LED3") (pin "1") (pinfunction "VDD_1") (pintype "passive"))
      (node (ref "LED30") (pin "1") (pinfunction "VDD_1") (pintype "passive"))
      (node (ref "LED31") (pin "1") (pinfunction "VDD_1") (pintype "passive"))
      (node (ref "LED32") (pin "1") (pinfunction "VDD_1") (pintype "passive"))
      (node (ref "LED33") (pin "1") (pinfunction "VDD_1") (pintype "passive"))
      (node (ref "LED34") (pin "1") (pinfunction "VDD_1") (pintype "passive"))
      (node (ref "LED35") (pin "1") (pinfunction "VDD_1") (pintype "passive"))
      (node (ref "LED36") (pin "1") (pinfunction "VDD_1") (pintype "passive"))
      (node (ref "LED37") (pin "1") (pinfunction "VDD_1") (pintype "passive"))
      (node (ref "LED38") (pin "1") (pinfunction "VDD_1") (pintype "passive"))
      (node (ref "LED39") (pin "1") (pinfunction "VDD_1") (pintype "passive"))
      (node (ref "LED4") (pin "1") (pinfunction "VDD_1") (pintype "passive"))
      (node (ref "LED40") (pin "1") (pinfunction "VDD_1") (pintype "passive"))
      (node (ref "LED41") (pin "1") (pinfunction "VDD_1") (pintype "passive"))
      (node (ref "LED42") (pin "1") (pinfunction "VDD_1") (pintype "passive"))
      (node (ref "LED43") (pin "1") (pinfunction "VDD_1") (pintype "passive"))
      (node (ref "LED44") (pin "1") (pinfunction "VDD_1") (pintype "passive"))
      (node (ref "LED45") (pin "1") (pinfunction "VDD_1") (pintype "passive"))
      (node (ref "LED46") (pin "1") (pinfunction "VDD_1") (pintype "passive"))
      (node (ref "LED47") (pin "1") (pinfunction "VDD_1") (pintype "passive"))
      (node (ref "LED48") (pin "1") (pinfunction "VDD_1") (pintype "passive"))
      (node (ref "LED49") (pin "1") (pinfunction "VDD_1") (pintype "passive"))
      (node (ref "LED5") (pin "1") (pinfunction "VDD_1") (pintype "passive"))
      (node (ref "LED50") (pin "1") (pinfunction "VDD_1") (pintype "passive"))
      (node (ref "LED51") (pin "1") (pinfunction "VDD_1") (pintype "passive"))
      (node (ref "LED52") (pin "1") (pinfunction "VDD_1") (pintype "passive"))
      (node (ref "LED53") (pin "1") (pinfunction "VDD_1") (pintype "passive"))
      (node (ref "LED54") (pin "1") (pinfunction "VDD_1") (pintype "passive"))
      (node (ref "LED55") (pin "1") (pinfunction "VDD_1") (pintype "passive"))
      (node (ref "LED56") (pin "1") (pinfunction "VDD_1") (pintype "passive"))
      (node (ref "LED57") (pin "1") (pinfunction "VDD_1") (pintype "passive"))
      (node (ref "LED58") (pin "1") (pinfunction "VDD_1") (pintype "passive"))
      (node (ref "LED59") (pin "1") (pinfunction "VDD_1") (pintype "passive"))
      (node (ref "LED6") (pin "1") (pinfunction "VDD_1") (pintype "passive"))
      (node (ref "LED60") (pin "1") (pinfunction "VDD_1") (pintype "passive"))
      (node (ref "LED61") (pin "1") (pinfunction "VDD_1") (pintype "passive"))
      (node (ref "LED62") (pin "1") (pinfunction "VDD_1") (pintype "passive"))
      (node (ref "LED63") (pin "1") (pinfunction "VDD_1") (pintype "passive"))
      (node (ref "LED64") (pin "1") (pinfunction "VDD_1") (pintype "passive"))
      (node (ref "LED65") (pin "1") (pinfunction "VDD_1") (pintype "passive"))
      (node (ref "LED66") (pin "1") (pinfunction "VDD_1") (pintype "passive"))
      (node (ref "LED67") (pin "1") (pinfunction "VDD_1") (pintype "passive"))
      (node (ref "LED68") (pin "1") (pinfunction "VDD_1") (pintype "passive"))
      (node (ref "LED69") (pin "1") (pinfunction "VDD_1") (pintype "passive"))
      (node (ref "LED7") (pin "1") (pinfunction "VDD_1") (pintype "passive"))
      (node (ref "LED70") (pin "1") (pinfunction "VDD_1") (pintype "passive"))
      (node (ref "LED71") (pin "1") (pinfunction "VDD_1") (pintype "passive"))
      (node (ref "LED72") (pin "1") (pinfunction "VDD_1") (pintype "passive"))
      (node (ref "LED73") (pin "1") (pinfunction "VDD_1") (pintype "passive"))
      (node (ref "LED74") (pin "1") (pinfunction "VDD_1") (pintype "passive"))
      (node (ref "LED75") (pin "1") (pinfunction "VDD_1") (pintype "passive"))
      (node (ref "LED76") (pin "1") (pinfunction "VDD_1") (pintype "passive"))
      (node (ref "LED77") (pin "1") (pinfunction "VDD_1") (pintype "passive"))
      (node (ref "LED78") (pin "1") (pinfunction "VDD_1") (pintype "passive"))
      (node (ref "LED79") (pin "1") (pinfunction "VDD_1") (pintype "passive"))
      (node (ref "LED8") (pin "1") (pinfunction "VDD_1") (pintype "passive"))
      (node (ref "LED80") (pin "1") (pinfunction "VDD_1") (pintype "passive"))
      (node (ref "LED81") (pin "1") (pinfunction "VDD_1") (pintype "passive"))
      (node (ref "LED82") (pin "1") (pinfunction "VDD_1") (pintype "passive"))
      (node (ref "LED83") (pin "1") (pinfunction "VDD_1") (pintype "passive"))
      (node (ref "LED84") (pin "1") (pinfunction "VDD_1") (pintype "passive"))
      (node (ref "LED85") (pin "1") (pinfunction "VDD_1") (pintype "passive"))
      (node (ref "LED86") (pin "1") (pinfunction "VDD_1") (pintype "passive"))
      (node (ref "LED87") (pin "1") (pinfunction "VDD_1") (pintype "passive"))
      (node (ref "LED88") (pin "1") (pinfunction "VDD_1") (pintype "passive"))
      (node (ref "LED89") (pin "1") (pinfunction "VDD_1") (pintype "passive"))
      (node (ref "LED9") (pin "1") (pinfunction "VDD_1") (pintype "passive"))
      (node (ref "LED90") (pin "1") (pinfunction "VDD_1") (pintype "passive"))
      (node (ref "LED91") (pin "1") (pinfunction "VDD_1") (pintype "passive"))
      (node (ref "LED92") (pin "1") (pinfunction "VDD_1") (pintype "passive"))
      (node (ref "LED93") (pin "1") (pinfunction "VDD_1") (pintype "passive"))
      (node (ref "LED94") (pin "1") (pinfunction "VDD_1") (pintype "passive"))
      (node (ref "LED95") (pin "1") (pinfunction "VDD_1") (pintype "passive"))
      (node (ref "LED96") (pin "1") (pinfunction "VDD_1") (pintype "passive"))
      (node (ref "LED97") (pin "1") (pinfunction "VDD_1") (pintype "passive"))
      (node (ref "LED98") (pin "1") (pinfunction "VDD_1") (pintype "passive"))
      (node (ref "LED99") (pin "1") (pinfunction "VDD_1") (pintype "passive"))
      (node (ref "RPUSB") (pin "1") (pinfunction "1_1") (pintype "passive"))
      (node (ref "U2") (pin "3") (pinfunction "In_3") (pintype "passive"))
      (node (ref "U6") (pin "1") (pinfunction "VCCA_1") (pintype "passive"))
    )
    (net (code "3") (name "/5VDIN") (class "Default")
      (node (ref "LED115") (pin "4") (pinfunction "DIN_4") (pintype "passive"))
      (node (ref "R10") (pin "1") (pinfunction "1_1") (pintype "passive"))
    )
    (net (code "4") (name "/ADC0") (class "Default")
      (node (ref "QU1") (pin "38") (pinfunction "GPIO26_ADC0_38") (pintype "passive"))
    )
    (net (code "5") (name "/ADC1") (class "Default")
      (node (ref "QU1") (pin "39") (pinfunction "GPIO27_ADC1_39") (pintype "passive"))
    )
    (net (code "6") (name "/ADC2") (class "Default")
      (node (ref "QU1") (pin "40") (pinfunction "GPIO28_ADC2_40") (pintype "passive"))
    )
    (net (code "7") (name "/ADC3") (class "Default")
      (node (ref "QU1") (pin "41") (pinfunction "GPIO29_ADC3_41") (pintype "passive"))
    )
    (net (code "8") (name "/GPIO 0") (class "Default")
      (node (ref "JP11") (pin "2") (pinfunction "2_2") (pintype "passive"))
      (node (ref "QU1") (pin "2") (pinfunction "GPIO0_2") (pintype "passive"))
    )
    (net (code "9") (name "/GPIO 1") (class "Default")
      (node (ref "JP10") (pin "2") (pinfunction "2_2") (pintype "passive"))
      (node (ref "QU1") (pin "3") (pinfunction "GPIO1_3") (pintype "passive"))
    )
    (net (code "10") (name "/GPIO 2") (class "Default")
      (node (ref "H22") (pin "2") (pinfunction "2_2") (pintype "passive"))
      (node (ref "QU1") (pin "4") (pinfunction "GPIO2_4") (pintype "passive"))
      (node (ref "R3") (pin "2") (pinfunction "2_2") (pintype "passive"))
      (node (ref "U1") (pin "4") (pinfunction "SDA_4") (pintype "passive"))
      (node (ref "U3") (pin "6") (pinfunction "SDA_6") (pintype "passive"))
      (node (ref "U4") (pin "5") (pinfunction "SDA_5") (pintype "passive"))
    )
    (net (code "11") (name "/GPIO 3") (class "Default")
      (node (ref "H22") (pin "3") (pinfunction "3_3") (pintype "passive"))
      (node (ref "QU1") (pin "5") (pinfunction "GPIO3_5") (pintype "passive"))
      (node (ref "R4") (pin "2") (pinfunction "2_2") (pintype "passive"))
      (node (ref "U1") (pin "6") (pinfunction "SCL_6") (pintype "passive"))
      (node (ref "U3") (pin "7") (pinfunction "SCL_7") (pintype "passive"))
      (node (ref "U4") (pin "6") (pinfunction "SCL_6") (pintype "passive"))
    )
    (net (code "12") (name "/GPIO 4") (class "Default")
      (node (ref "QU1") (pin "6") (pinfunction "GPIO4_6") (pintype "passive"))
    )
    (net (code "13") (name "/GPIO 5") (class "Default")
      (node (ref "QU1") (pin "7") (pinfunction "GPIO5_7") (pintype "passive"))
    )
    (net (code "14") (name "/GPIO 6") (class "Default")
      (node (ref "QU1") (pin "8") (pinfunction "GPIO6_8") (pintype "passive"))
    )
    (net (code "15") (name "/GPIO 7") (class "Default")
      (node (ref "QU1") (pin "9") (pinfunction "GPIO7_9") (pintype "passive"))
    )
    (net (code "16") (name "/GPIO 8") (class "Default")
      (node (ref "QU1") (pin "11") (pinfunction "GPIO8_11") (pintype "passive"))
    )
    (net (code "17") (name "/GPIO 9") (class "Default")
      (node (ref "QU1") (pin "12") (pinfunction "GPIO9_12") (pintype "passive"))
    )
    (net (code "18") (name "/GPIO 10") (class "Default")
      (node (ref "QU1") (pin "13") (pinfunction "GPIO10_13") (pintype "passive"))
    )
    (net (code "19") (name "/GPIO 11") (class "Default")
      (node (ref "QU1") (pin "14") (pinfunction "GPIO11_14") (pintype "passive"))
    )
    (net (code "20") (name "/GPIO 12") (class "Default")
      (node (ref "QU1") (pin "15") (pinfunction "GPIO12_15") (pintype "passive"))
    )
    (net (code "21") (name "/GPIO 13") (class "Default")
      (node (ref "QU1") (pin "16") (pinfunction "GPIO13_16") (pintype "passive"))
    )
    (net (code "22") (name "/GPIO 14") (class "Default")
      (node (ref "QU1") (pin "17") (pinfunction "GPIO14_17") (pintype "passive"))
    )
    (net (code "23") (name "/GPIO 15") (class "Default")
      (node (ref "QU1") (pin "18") (pinfunction "GPIO15_18") (pintype "passive"))
    )
    (net (code "24") (name "/GPIO 16") (class "Default")
      (node (ref "JP7") (pin "1") (pinfunction "1_1") (pintype "passive"))
      (node (ref "QU1") (pin "27") (pinfunction "GPIO16_27") (pintype "passive"))
    )
    (net (code "25") (name "/GPIO 17") (class "Default")
      (node (ref "QU1") (pin "28") (pinfunction "GPIO17_28") (pintype "passive"))
    )
    (net (code "26") (name "/GPIO 18") (class "Default")
      (node (ref "QU1") (pin "29") (pinfunction "GPIO18_29") (pintype "passive"))
    )
    (net (code "27") (name "/GPIO 19") (class "Default")
      (node (ref "QU1") (pin "30") (pinfunction "GPIO19_30") (pintype "passive"))
    )
    (net (code "28") (name "/GPIO 20") (class "Default")
      (node (ref "QU1") (pin "31") (pinfunction "GPIO20_31") (pintype "passive"))
    )
    (net (code "29") (name "/GPIO 21") (class "Default")
      (node (ref "QU1") (pin "32") (pinfunction "GPIO21_32") (pintype "passive"))
    )
    (net (code "30") (name "/GPIO 22") (class "Default")
      (node (ref "JP6") (pin "1") (pinfunction "1_1") (pintype "passive"))
      (node (ref "QU1") (pin "34") (pinfunction "GPIO22_34") (pintype "passive"))
    )
    (net (code "31") (name "/GPIO 23") (class "Default")
      (node (ref "QU1") (pin "35") (pinfunction "GPIO23_35") (pintype "passive"))
    )
    (net (code "32") (name "/GPIO 24") (class "Default")
      (node (ref "QU1") (pin "36") (pinfunction "GPIO24_36") (pintype "passive"))
    )
    (net (code "33") (name "/GPIO 25") (class "Default")
      (node (ref "QU1") (pin "37") (pinfunction "GPIO25_37") (pintype "passive"))
      (node (ref "R13") (pin "1") (pinfunction "1_1") (pintype "passive"))
    )
    (net (code "34") (name "/MATRIX_DIN") (class "Default")
      (node (ref "H2") (pin "2") (pinfunction "2_2") (pintype "passive"))
      (node (ref "LED115") (pin "2") (pinfunction "DOUT_2") (pintype "passive"))
      (node (ref "LED8") (pin "4") (pinfunction "DIN_4") (pintype "passive"))
    )
    (net (code "35") (name "/QSPI_CLK") (class "Default")
      (node (ref "QU1") (pin "52") (pinfunction "QSPI_SCLK_52") (pintype "passive"))
      (node (ref "QU2") (pin "6") (pinfunction "CLK_6") (pintype "passive"))
    )
    (net (code "36") (name "/QSPI_SD0") (class "Default")
      (node (ref "QU1") (pin "53") (pinfunction "QSPI_SD0_53") (pintype "passive"))
      (node (ref "QU2") (pin "5") (pinfunction "DI(IO0)_5") (pintype "passive"))
    )
    (net (code "37") (name "/QSPI_SD1") (class "Default")
      (node (ref "QU1") (pin "55") (pinfunction "QSPI_SD1_55") (pintype "passive"))
      (node (ref "QU2") (pin "2") (pinfunction "DO(IO1)_2") (pintype "passive"))
    )
    (net (code "38") (name "/QSPI_SD2") (class "Default")
      (node (ref "QU1") (pin "54") (pinfunction "QSPI_SD2_54") (pintype "passive"))
      (node (ref "QU2") (pin "3") (pinfunction "WP#(IO2)_3") (pintype "passive"))
    )
    (net (code "39") (name "/QSPI_SD3") (class "Default")
      (node (ref "QU1") (pin "51") (pinfunction "QSPI_SD3_51") (pintype "passive"))
      (node (ref "QU2") (pin "7") (pinfunction "HOLD#_or_RESET#(IO3)_7") (pintype "passive"))
    )
    (net (code "40") (name "/QSPI_SS") (class "Default")
      (node (ref "QU1") (pin "56") (pinfunction "QSPI_SS_56") (pintype "passive"))
      (node (ref "QU2") (pin "1") (pinfunction "CS#_1") (pintype "passive"))
      (node (ref "R11") (pin "1") (pinfunction "1_1") (pintype "passive"))
      (node (ref "R12") (pin "2") (pinfunction "2_2") (pintype "passive"))
    )
    (net (code "41") (name "/RUN") (class "Default")
      (node (ref "P1") (pin "2") (pinfunction "2_2") (pintype "passive"))
      (node (ref "QU1") (pin "26") (pinfunction "RUN_26") (pintype "passive"))
      (node (ref "R5") (pin "1") (pinfunction "1_1") (pintype "passive"))
      (node (ref "RPRST") (pin "2") (pinfunction "2_2") (pintype "passive"))
    )
    (net (code "42") (name "/SWCLK") (class "Default")
      (node (ref "P1") (pin "4") (pinfunction "4_4") (pintype "passive"))
      (node (ref "QU1") (pin "24") (pinfunction "SWCLK_24") (pintype "passive"))
    )
    (net (code "43") (name "/SWD") (class "Default")
      (node (ref "P1") (pin "3") (pinfunction "3_3") (pintype "passive"))
      (node (ref "QU1") (pin "25") (pinfunction "SWD_25") (pintype "passive"))
    )
    (net (code "44") (name "/USB_D+") (class "Default")
      (node (ref "R7") (pin "2") (pinfunction "2_2") (pintype "passive"))
      (node (ref "RPUSB") (pin "3") (pinfunction "3_3") (pintype "passive"))
    )
    (net (code "45") (name "/USB_D-") (class "Default")
      (node (ref "R9") (pin "2") (pinfunction "2_2") (pintype "passive"))
      (node (ref "RPUSB") (pin "2") (pinfunction "2_2") (pintype "passive"))
    )
    (net (code "46") (name "/XIN") (class "Default")
      (node (ref "C134") (pin "1") (pinfunction "1_1") (pintype "passive"))
      (node (ref "QU1") (pin "20") (pinfunction "XIN_20") (pintype "passive"))
      (node (ref "QX1") (pin "1") (pinfunction "OSC1_1") (pintype "passive"))
    )
    (net (code "47") (name "/XOUT") (class "Default")
      (node (ref "C135") (pin "2") (pinfunction "2_2") (pintype "passive"))
      (node (ref "QU1") (pin "21") (pinfunction "XOUT_21") (pintype "passive"))
      (node (ref "QX1") (pin "3") (pinfunction "OSC2_3") (pintype "passive"))
    )
    (net (code "48") (name "GND") (class "Default")
      (node (ref "BT1") (pin "2") (pinfunction "2_2") (pintype "passive"))
      (node (ref "BT2") (pin "2") (pinfunction "2_2") (pintype "passive"))
      (node (ref "C1") (pin "2") (pinfunction "2_2") (pintype "passive"))
      (node (ref "C10") (pin "1") (pinfunction "1_1") (pintype "passive"))
      (node (ref "C100") (pin "2") (pinfunction "2_2") (pintype "passive"))
      (node (ref "C101") (pin "2") (pinfunction "2_2") (pintype "passive"))
      (node (ref "C102") (pin "2") (pinfunction "2_2") (pintype "passive"))
      (node (ref "C103") (pin "2") (pinfunction "2_2") (pintype "passive"))
      (node (ref "C104") (pin "2") (pinfunction "2_2") (pintype "passive"))
      (node (ref "C105") (pin "2") (pinfunction "2_2") (pintype "passive"))
      (node (ref "C106") (pin "2") (pinfunction "2_2") (pintype "passive"))
      (node (ref "C107") (pin "2") (pinfunction "2_2") (pintype "passive"))
      (node (ref "C108") (pin "2") (pinfunction "2_2") (pintype "passive"))
      (node (ref "C109") (pin "2") (pinfunction "2_2") (pintype "passive"))
      (node (ref "C11") (pin "2") (pinfunction "2_2") (pintype "passive"))
      (node (ref "C110") (pin "2") (pinfunction "2_2") (pintype "passive"))
      (node (ref "C111") (pin "2") (pinfunction "2_2") (pintype "passive"))
      (node (ref "C112") (pin "2") (pinfunction "2_2") (pintype "passive"))
      (node (ref "C113") (pin "2") (pinfunction "2_2") (pintype "passive"))
      (node (ref "C114") (pin "2") (pinfunction "2_2") (pintype "passive"))
      (node (ref "C115") (pin "2") (pinfunction "2_2") (pintype "passive"))
      (node (ref "C116") (pin "2") (pinfunction "2_2") (pintype "passive"))
      (node (ref "C117") (pin "2") (pinfunction "2_2") (pintype "passive"))
      (node (ref "C118") (pin "2") (pinfunction "2_2") (pintype "passive"))
      (node (ref "C119") (pin "2") (pinfunction "2_2") (pintype "passive"))
      (node (ref "C12") (pin "2") (pinfunction "2_2") (pintype "passive"))
      (node (ref "C120") (pin "2") (pinfunction "2_2") (pintype "passive"))
      (node (ref "C121") (pin "2") (pinfunction "2_2") (pintype "passive"))
      (node (ref "C122") (pin "2") (pinfunction "2_2") (pintype "passive"))
      (node (ref "C123") (pin "2") (pinfunction "2_2") (pintype "passive"))
      (node (ref "C124") (pin "2") (pinfunction "2_2") (pintype "passive"))
      (node (ref "C125") (pin "1") (pinfunction "1_1") (pintype "passive"))
      (node (ref "C126") (pin "1") (pinfunction "1_1") (pintype "passive"))
      (node (ref "C127") (pin "1") (pinfunction "1_1") (pintype "passive"))
      (node (ref "C128") (pin "1") (pinfunction "1_1") (pintype "passive"))
      (node (ref "C129") (pin "2") (pinfunction "2_2") (pintype "passive"))
      (node (ref "C13") (pin "2") (pinfunction "2_2") (pintype "passive"))
      (node (ref "C130") (pin "2") (pinfunction "2_2") (pintype "passive"))
      (node (ref "C131") (pin "1") (pinfunction "1_1") (pintype "passive"))
      (node (ref "C132") (pin "1") (pinfunction "1_1") (pintype "passive"))
      (node (ref "C133") (pin "1") (pinfunction "1_1") (pintype "passive"))
      (node (ref "C134") (pin "2") (pinfunction "2_2") (pintype "passive"))
      (node (ref "C135") (pin "1") (pinfunction "1_1") (pintype "passive"))
      (node (ref "C136") (pin "2") (pinfunction "2_2") (pintype "passive"))
      (node (ref "C14") (pin "2") (pinfunction "2_2") (pintype "passive"))
      (node (ref "C15") (pin "2") (pinfunction "2_2") (pintype "passive"))
      (node (ref "C16") (pin "2") (pinfunction "2_2") (pintype "passive"))
      (node (ref "C17") (pin "2") (pinfunction "2_2") (pintype "passive"))
      (node (ref "C18") (pin "2") (pinfunction "2_2") (pintype "passive"))
      (node (ref "C19") (pin "2") (pinfunction "2_2") (pintype "passive"))
      (node (ref "C2") (pin "1") (pinfunction "1_1") (pintype "passive"))
      (node (ref "C20") (pin "2") (pinfunction "2_2") (pintype "passive"))
      (node (ref "C21") (pin "2") (pinfunction "2_2") (pintype "passive"))
      (node (ref "C22") (pin "2") (pinfunction "2_2") (pintype "passive"))
      (node (ref "C23") (pin "2") (pinfunction "2_2") (pintype "passive"))
      (node (ref "C24") (pin "2") (pinfunction "2_2") (pintype "passive"))
      (node (ref "C25") (pin "2") (pinfunction "2_2") (pintype "passive"))
      (node (ref "C26") (pin "2") (pinfunction "2_2") (pintype "passive"))
      (node (ref "C27") (pin "2") (pinfunction "2_2") (pintype "passive"))
      (node (ref "C28") (pin "2") (pinfunction "2_2") (pintype "passive"))
      (node (ref "C29") (pin "2") (pinfunction "2_2") (pintype "passive"))
      (node (ref "C3") (pin "2") (pinfunction "2_2") (pintype "passive"))
      (node (ref "C30") (pin "2") (pinfunction "2_2") (pintype "passive"))
      (node (ref "C31") (pin "2") (pinfunction "2_2") (pintype "passive"))
      (node (ref "C32") (pin "2") (pinfunction "2_2") (pintype "passive"))
      (node (ref "C33") (pin "2") (pinfunction "2_2") (pintype "passive"))
      (node (ref "C34") (pin "2") (pinfunction "2_2") (pintype "passive"))
      (node (ref "C35") (pin "2") (pinfunction "2_2") (pintype "passive"))
      (node (ref "C36") (pin "2") (pinfunction "2_2") (pintype "passive"))
      (node (ref "C37") (pin "2") (pinfunction "2_2") (pintype "passive"))
      (node (ref "C38") (pin "2") (pinfunction "2_2") (pintype "passive"))
      (node (ref "C39") (pin "2") (pinfunction "2_2") (pintype "passive"))
      (node (ref "C40") (pin "2") (pinfunction "2_2") (pintype "passive"))
      (node (ref "C41") (pin "2") (pinfunction "2_2") (pintype "passive"))
      (node (ref "C42") (pin "2") (pinfunction "2_2") (pintype "passive"))
      (node (ref "C43") (pin "2") (pinfunction "2_2") (pintype "passive"))
      (node (ref "C44") (pin "2") (pinfunction "2_2") (pintype "passive"))
      (node (ref "C45") (pin "2") (pinfunction "2_2") (pintype "passive"))
      (node (ref "C46") (pin "2") (pinfunction "2_2") (pintype "passive"))
      (node (ref "C47") (pin "2") (pinfunction "2_2") (pintype "passive"))
      (node (ref "C48") (pin "2") (pinfunction "2_2") (pintype "passive"))
      (node (ref "C49") (pin "2") (pinfunction "2_2") (pintype "passive"))
      (node (ref "C5") (pin "2") (pinfunction "2_2") (pintype "passive"))
      (node (ref "C50") (pin "2") (pinfunction "2_2") (pintype "passive"))
      (node (ref "C51") (pin "2") (pinfunction "2_2") (pintype "passive"))
      (node (ref "C52") (pin "2") (pinfunction "2_2") (pintype "passive"))
      (node (ref "C53") (pin "2") (pinfunction "2_2") (pintype "passive"))
      (node (ref "C54") (pin "2") (pinfunction "2_2") (pintype "passive"))
      (node (ref "C55") (pin "2") (pinfunction "2_2") (pintype "passive"))
      (node (ref "C56") (pin "2") (pinfunction "2_2") (pintype "passive"))
      (node (ref "C57") (pin "2") (pinfunction "2_2") (pintype "passive"))
      (node (ref "C58") (pin "2") (pinfunction "2_2") (pintype "passive"))
      (node (ref "C59") (pin "2") (pinfunction "2_2") (pintype "passive"))
      (node (ref "C6") (pin "1") (pinfunction "1_1") (pintype "passive"))
      (node (ref "C60") (pin "2") (pinfunction "2_2") (pintype "passive"))
      (node (ref "C61") (pin "2") (pinfunction "2_2") (pintype "passive"))
      (node (ref "C62") (pin "2") (pinfunction "2_2") (pintype "passive"))
      (node (ref "C63") (pin "2") (pinfunction "2_2") (pintype "passive"))
      (node (ref "C64") (pin "2") (pinfunction "2_2") (pintype "passive"))
      (node (ref "C65") (pin "2") (pinfunction "2_2") (pintype "passive"))
      (node (ref "C66") (pin "2") (pinfunction "2_2") (pintype "passive"))
      (node (ref "C67") (pin "2") (pinfunction "2_2") (pintype "passive"))
      (node (ref "C68") (pin "2") (pinfunction "2_2") (pintype "passive"))
      (node (ref "C69") (pin "2") (pinfunction "2_2") (pintype "passive"))
      (node (ref "C7") (pin "2") (pinfunction "2_2") (pintype "passive"))
      (node (ref "C70") (pin "2") (pinfunction "2_2") (pintype "passive"))
      (node (ref "C71") (pin "2") (pinfunction "2_2") (pintype "passive"))
      (node (ref "C72") (pin "2") (pinfunction "2_2") (pintype "passive"))
      (node (ref "C73") (pin "2") (pinfunction "2_2") (pintype "passive"))
      (node (ref "C74") (pin "2") (pinfunction "2_2") (pintype "passive"))
      (node (ref "C75") (pin "2") (pinfunction "2_2") (pintype "passive"))
      (node (ref "C76") (pin "2") (pinfunction "2_2") (pintype "passive"))
      (node (ref "C77") (pin "2") (pinfunction "2_2") (pintype "passive"))
      (node (ref "C78") (pin "2") (pinfunction "2_2") (pintype "passive"))
      (node (ref "C79") (pin "2") (pinfunction "2_2") (pintype "passive"))
      (node (ref "C8") (pin "2") (pinfunction "2_2") (pintype "passive"))
      (node (ref "C80") (pin "2") (pinfunction "2_2") (pintype "passive"))
      (node (ref "C81") (pin "2") (pinfunction "2_2") (pintype "passive"))
      (node (ref "C82") (pin "2") (pinfunction "2_2") (pintype "passive"))
      (node (ref "C83") (pin "2") (pinfunction "2_2") (pintype "passive"))
      (node (ref "C84") (pin "2") (pinfunction "2_2") (pintype "passive"))
      (node (ref "C85") (pin "2") (pinfunction "2_2") (pintype "passive"))
      (node (ref "C86") (pin "2") (pinfunction "2_2") (pintype "passive"))
      (node (ref "C87") (pin "2") (pinfunction "2_2") (pintype "passive"))
      (node (ref "C88") (pin "2") (pinfunction "2_2") (pintype "passive"))
      (node (ref "C89") (pin "2") (pinfunction "2_2") (pintype "passive"))
      (node (ref "C9") (pin "2") (pinfunction "2_2") (pintype "passive"))
      (node (ref "C90") (pin "2") (pinfunction "2_2") (pintype "passive"))
      (node (ref "C91") (pin "2") (pinfunction "2_2") (pintype "passive"))
      (node (ref "C92") (pin "2") (pinfunction "2_2") (pintype "passive"))
      (node (ref "C93") (pin "2") (pinfunction "2_2") (pintype "passive"))
      (node (ref "C94") (pin "2") (pinfunction "2_2") (pintype "passive"))
      (node (ref "C95") (pin "2") (pinfunction "2_2") (pintype "passive"))
      (node (ref "C96") (pin "2") (pinfunction "2_2") (pintype "passive"))
      (node (ref "C97") (pin "2") (pinfunction "2_2") (pintype "passive"))
      (node (ref "C98") (pin "2") (pinfunction "2_2") (pintype "passive"))
      (node (ref "C99") (pin "2") (pinfunction "2_2") (pintype "passive"))
      (node (ref "H1") (pin "3") (pinfunction "3_3") (pintype "passive"))
      (node (ref "H10") (pin "3") (pinfunction "3_3") (pintype "passive"))
      (node (ref "H11") (pin "3") (pinfunction "3_3") (pintype "passive"))
      (node (ref "H12") (pin "3") (pinfunction "3_3") (pintype "passive"))
      (node (ref "H13") (pin "3") (pinfunction "3_3") (pintype "passive"))
      (node (ref "H14") (pin "3") (pinfunction "3_3") (pintype "passive"))
      (node (ref "H15") (pin "3") (pinfunction "3_3") (pintype "passive"))
      (node (ref "H16") (pin "3") (pinfunction "3_3") (pintype "passive"))
      (node (ref "H17") (pin "3") (pinfunction "3_3") (pintype "passive"))
      (node (ref "H18") (pin "3") (pinfunction "3_3") (pintype "passive"))
      (node (ref "H19") (pin "3") (pinfunction "3_3") (pintype "passive"))
      (node (ref "H2") (pin "3") (pinfunction "3_3") (pintype "passive"))
      (node (ref "H20") (pin "3") (pinfunction "3_3") (pintype "passive"))
      (node (ref "H21") (pin "3") (pinfunction "3_3") (pintype "passive"))
      (node (ref "H22") (pin "1") (pinfunction "1_1") (pintype "passive"))
      (node (ref "H3") (pin "3") (pinfunction "3_3") (pintype "passive"))
      (node (ref "H4") (pin "3") (pinfunction "3_3") (pintype "passive"))
      (node (ref "H5") (pin "3") (pinfunction "3_3") (pintype "passive"))
      (node (ref "H6") (pin "3") (pinfunction "3_3") (pintype "passive"))
      (node (ref "H7") (pin "3") (pinfunction "3_3") (pintype "passive"))
      (node (ref "H8") (pin "3") (pinfunction "3_3") (pintype "passive"))
      (node (ref "H9") (pin "3") (pinfunction "3_3") (pintype "passive"))
      (node (ref "LED1") (pin "3") (pinfunction "VSS_3") (pintype "passive"))
      (node (ref "LED10") (pin "3") (pinfunction "VSS_3") (pintype "passive"))
      (node (ref "LED100") (pin "3") (pinfunction "VSS_3") (pintype "passive"))
      (node (ref "LED101") (pin "3") (pinfunction "VSS_3") (pintype "passive"))
      (node (ref "LED102") (pin "3") (pinfunction "VSS_3") (pintype "passive"))
      (node (ref "LED103") (pin "3") (pinfunction "VSS_3") (pintype "passive"))
      (node (ref "LED104") (pin "3") (pinfunction "VSS_3") (pintype "passive"))
      (node (ref "LED105") (pin "3") (pinfunction "VSS_3") (pintype "passive"))
      (node (ref "LED106") (pin "3") (pinfunction "VSS_3") (pintype "passive"))
      (node (ref "LED107") (pin "3") (pinfunction "VSS_3") (pintype "passive"))
      (node (ref "LED108") (pin "3") (pinfunction "VSS_3") (pintype "passive"))
      (node (ref "LED109") (pin "3") (pinfunction "VSS_3") (pintype "passive"))
      (node (ref "LED11") (pin "3") (pinfunction "VSS_3") (pintype "passive"))
      (node (ref "LED110") (pin "3") (pinfunction "VSS_3") (pintype "passive"))
      (node (ref "LED111") (pin "3") (pinfunction "VSS_3") (pintype "passive"))
      (node (ref "LED112") (pin "3") (pinfunction "VSS_3") (pintype "passive"))
      (node (ref "LED113") (pin "3") (pinfunction "VSS_3") (pintype "passive"))
      (node (ref "LED114") (pin "3") (pinfunction "VSS_3") (pintype "passive"))
      (node (ref "LED115") (pin "3") (pinfunction "VSS_3") (pintype "passive"))
      (node (ref "LED116") (pin "1") (pinfunction "-_1") (pintype "passive"))
      (node (ref "LED12") (pin "3") (pinfunction "VSS_3") (pintype "passive"))
      (node (ref "LED13") (pin "3") (pinfunction "VSS_3") (pintype "passive"))
      (node (ref "LED14") (pin "3") (pinfunction "VSS_3") (pintype "passive"))
      (node (ref "LED15") (pin "3") (pinfunction "VSS_3") (pintype "passive"))
      (node (ref "LED16") (pin "3") (pinfunction "VSS_3") (pintype "passive"))
      (node (ref "LED17") (pin "3") (pinfunction "VSS_3") (pintype "passive"))
      (node (ref "LED18") (pin "3") (pinfunction "VSS_3") (pintype "passive"))
      (node (ref "LED19") (pin "3") (pinfunction "VSS_3") (pintype "passive"))
      (node (ref "LED20") (pin "3") (pinfunction "VSS_3") (pintype "passive"))
      (node (ref "LED21") (pin "3") (pinfunction "VSS_3") (pintype "passive"))
      (node (ref "LED22") (pin "3") (pinfunction "VSS_3") (pintype "passive"))
      (node (ref "LED23") (pin "3") (pinfunction "VSS_3") (pintype "passive"))
      (node (ref "LED24") (pin "3") (pinfunction "VSS_3") (pintype "passive"))
      (node (ref "LED25") (pin "3") (pinfunction "VSS_3") (pintype "passive"))
      (node (ref "LED26") (pin "3") (pinfunction "VSS_3") (pintype "passive"))
      (node (ref "LED27") (pin "3") (pinfunction "VSS_3") (pintype "passive"))
      (node (ref "LED28") (pin "3") (pinfunction "VSS_3") (pintype "passive"))
      (node (ref "LED29") (pin "3") (pinfunction "VSS_3") (pintype "passive"))
      (node (ref "LED3") (pin "3") (pinfunction "VSS_3") (pintype "passive"))
      (node (ref "LED30") (pin "3") (pinfunction "VSS_3") (pintype "passive"))
      (node (ref "LED31") (pin "3") (pinfunction "VSS_3") (pintype "passive"))
      (node (ref "LED32") (pin "3") (pinfunction "VSS_3") (pintype "passive"))
      (node (ref "LED33") (pin "3") (pinfunction "VSS_3") (pintype "passive"))
      (node (ref "LED34") (pin "3") (pinfunction "VSS_3") (pintype "passive"))
      (node (ref "LED35") (pin "3") (pinfunction "VSS_3") (pintype "passive"))
      (node (ref "LED36") (pin "3") (pinfunction "VSS_3") (pintype "passive"))
      (node (ref "LED37") (pin "3") (pinfunction "VSS_3") (pintype "passive"))
      (node (ref "LED38") (pin "3") (pinfunction "VSS_3") (pintype "passive"))
      (node (ref "LED39") (pin "3") (pinfunction "VSS_3") (pintype "passive"))
      (node (ref "LED4") (pin "3") (pinfunction "VSS_3") (pintype "passive"))
      (node (ref "LED40") (pin "3") (pinfunction "VSS_3") (pintype "passive"))
      (node (ref "LED41") (pin "3") (pinfunction "VSS_3") (pintype "passive"))
      (node (ref "LED42") (pin "3") (pinfunction "VSS_3") (pintype "passive"))
      (node (ref "LED43") (pin "3") (pinfunction "VSS_3") (pintype "passive"))
      (node (ref "LED44") (pin "3") (pinfunction "VSS_3") (pintype "passive"))
      (node (ref "LED45") (pin "3") (pinfunction "VSS_3") (pintype "passive"))
      (node (ref "LED46") (pin "3") (pinfunction "VSS_3") (pintype "passive"))
      (node (ref "LED47") (pin "3") (pinfunction "VSS_3") (pintype "passive"))
      (node (ref "LED48") (pin "3") (pinfunction "VSS_3") (pintype "passive"))
      (node (ref "LED49") (pin "3") (pinfunction "VSS_3") (pintype "passive"))
      (node (ref "LED5") (pin "3") (pinfunction "VSS_3") (pintype "passive"))
      (node (ref "LED50") (pin "3") (pinfunction "VSS_3") (pintype "passive"))
      (node (ref "LED51") (pin "3") (pinfunction "VSS_3") (pintype "passive"))
      (node (ref "LED52") (pin "3") (pinfunction "VSS_3") (pintype "passive"))
      (node (ref "LED53") (pin "3") (pinfunction "VSS_3") (pintype "passive"))
      (node (ref "LED54") (pin "3") (pinfunction "VSS_3") (pintype "passive"))
      (node (ref "LED55") (pin "3") (pinfunction "VSS_3") (pintype "passive"))
      (node (ref "LED56") (pin "3") (pinfunction "VSS_3") (pintype "passive"))
      (node (ref "LED57") (pin "3") (pinfunction "VSS_3") (pintype "passive"))
      (node (ref "LED58") (pin "3") (pinfunction "VSS_3") (pintype "passive"))
      (node (ref "LED59") (pin "3") (pinfunction "VSS_3") (pintype "passive"))
      (node (ref "LED6") (pin "3") (pinfunction "VSS_3") (pintype "passive"))
      (node (ref "LED60") (pin "3") (pinfunction "VSS_3") (pintype "passive"))
      (node (ref "LED61") (pin "3") (pinfunction "VSS_3") (pintype "passive"))
      (node (ref "LED62") (pin "3") (pinfunction "VSS_3") (pintype "passive"))
      (node (ref "LED63") (pin "3") (pinfunction "VSS_3") (pintype "passive"))
      (node (ref "LED64") (pin "3") (pinfunction "VSS_3") (pintype "passive"))
      (node (ref "LED65") (pin "3") (pinfunction "VSS_3") (pintype "passive"))
      (node (ref "LED66") (pin "3") (pinfunction "VSS_3") (pintype "passive"))
      (node (ref "LED67") (pin "3") (pinfunction "VSS_3") (pintype "passive"))
      (node (ref "LED68") (pin "3") (pinfunction "VSS_3") (pintype "passive"))
      (node (ref "LED69") (pin "3") (pinfunction "VSS_3") (pintype "passive"))
      (node (ref "LED7") (pin "3") (pinfunction "VSS_3") (pintype "passive"))
      (node (ref "LED70") (pin "3") (pinfunction "VSS_3") (pintype "passive"))
      (node (ref "LED71") (pin "3") (pinfunction "VSS_3") (pintype "passive"))
      (node (ref "LED72") (pin "3") (pinfunction "VSS_3") (pintype "passive"))
      (node (ref "LED73") (pin "3") (pinfunction "VSS_3") (pintype "passive"))
      (node (ref "LED74") (pin "3") (pinfunction "VSS_3") (pintype "passive"))
      (node (ref "LED75") (pin "3") (pinfunction "VSS_3") (pintype "passive"))
      (node (ref "LED76") (pin "3") (pinfunction "VSS_3") (pintype "passive"))
      (node (ref "LED77") (pin "3") (pinfunction "VSS_3") (pintype "passive"))
      (node (ref "LED78") (pin "3") (pinfunction "VSS_3") (pintype "passive"))
      (node (ref "LED79") (pin "3") (pinfunction "VSS_3") (pintype "passive"))
      (node (ref "LED8") (pin "3") (pinfunction "VSS_3") (pintype "passive"))
      (node (ref "LED80") (pin "3") (pinfunction "VSS_3") (pintype "passive"))
      (node (ref "LED81") (pin "3") (pinfunction "VSS_3") (pintype "passive"))
      (node (ref "LED82") (pin "3") (pinfunction "VSS_3") (pintype "passive"))
      (node (ref "LED83") (pin "3") (pinfunction "VSS_3") (pintype "passive"))
      (node (ref "LED84") (pin "3") (pinfunction "VSS_3") (pintype "passive"))
      (node (ref "LED85") (pin "3") (pinfunction "VSS_3") (pintype "passive"))
      (node (ref "LED86") (pin "3") (pinfunction "VSS_3") (pintype "passive"))
      (node (ref "LED87") (pin "3") (pinfunction "VSS_3") (pintype "passive"))
      (node (ref "LED88") (pin "3") (pinfunction "VSS_3") (pintype "passive"))
      (node (ref "LED89") (pin "3") (pinfunction "VSS_3") (pintype "passive"))
      (node (ref "LED9") (pin "3") (pinfunction "VSS_3") (pintype "passive"))
      (node (ref "LED90") (pin "3") (pinfunction "VSS_3") (pintype "passive"))
      (node (ref "LED91") (pin "3") (pinfunction "VSS_3") (pintype "passive"))
      (node (ref "LED92") (pin "3") (pinfunction "VSS_3") (pintype "passive"))
      (node (ref "LED93") (pin "3") (pinfunction "VSS_3") (pintype "passive"))
      (node (ref "LED94") (pin "3") (pinfunction "VSS_3") (pintype "passive"))
      (node (ref "LED95") (pin "3") (pinfunction "VSS_3") (pintype "passive"))
      (node (ref "LED96") (pin "3") (pinfunction "VSS_3") (pintype "passive"))
      (node (ref "LED97") (pin "3") (pinfunction "VSS_3") (pintype "passive"))
      (node (ref "LED98") (pin "3") (pinfunction "VSS_3") (pintype "passive"))
      (node (ref "LED99") (pin "3") (pinfunction "VSS_3") (pintype "passive"))
      (node (ref "P1") (pin "5") (pinfunction "5_5") (pintype "passive"))
      (node (ref "P2") (pin "1") (pinfunction "1_1") (pintype "passive"))
      (node (ref "QBOOT") (pin "4") (pinfunction "4_4") (pintype "passive"))
      (node (ref "QU1") (pin "19") (pinfunction "TESTEN_19") (pintype "passive"))
      (node (ref "QU1") (pin "57") (pinfunction "GND_57") (pintype "passive"))
      (node (ref "QU2") (pin "4") (pinfunction "GND_4") (pintype "passive"))
      (node (ref "QX1") (pin "2") (pinfunction "GND_2") (pintype "passive"))
      (node (ref "QX1") (pin "4") (pinfunction "GND_4") (pintype "passive"))
      (node (ref "R1") (pin "2") (pinfunction "2_2") (pintype "passive"))
      (node (ref "R16") (pin "1") (pinfunction "1_1") (pintype "passive"))
      (node (ref "RPRST") (pin "4") (pinfunction "4_4") (pintype "passive"))
      (node (ref "RPUSB") (pin "4") (pinfunction "4_4") (pintype "passive"))
      (node (ref "U1") (pin "3") (pinfunction "GND_3") (pintype "passive"))
      (node (ref "U2") (pin "1") (pinfunction "GND_1") (pintype "passive"))
      (node (ref "U3") (pin "5") (pinfunction "VSS_5") (pintype "passive"))
      (node (ref "U4") (pin "4") (pinfunction "VSS_4") (pintype "passive"))
      (node (ref "U5") (pin "9") (pinfunction "GND_9") (pintype "passive"))
      (node (ref "U6") (pin "2") (pinfunction "GND_2") (pintype "passive"))
    )
    (net (code "49") (name "Net-(D1-C)") (class "Default")
      (node (ref "C122") (pin "1") (pinfunction "1_1") (pintype "passive"))
      (node (ref "D1") (pin "1") (pinfunction "C_1") (pintype "passive"))
      (node (ref "JP4") (pin "2") (pinfunction "2_2") (pintype "passive"))
      (node (ref "LED115") (pin "1") (pinfunction "VDD_1") (pintype "passive"))
    )
    (net (code "50") (name "Net-(ESPFLASH-Pad2)") (class "Default")
      (node (ref "ESPFLASH") (pin "2") (pinfunction "2_2") (pintype "passive"))
      (node (ref "ESPRST") (pin "1") (pinfunction "1_1") (pintype "passive"))
    )
    (net (code "51") (name "Net-(JP3-Pad1)") (class "Default")
      (node (ref "JP3") (pin "1") (pinfunction "1_1") (pintype "passive"))
      (node (ref "R12") (pin "1") (pinfunction "1_1") (pintype "passive"))
    )
    (net (code "52") (name "Net-(LED1-DIN)") (class "Default")
      (node (ref "LED1") (pin "4") (pinfunction "DIN_4") (pintype "passive"))
      (node (ref "LED16") (pin "2") (pinfunction "DOUT_2") (pintype "passive"))
    )
    (net (code "53") (name "Net-(LED1-DOUT)") (class "Default")
      (node (ref "LED1") (pin "2") (pinfunction "DOUT_2") (pintype "passive"))
      (node (ref "LED3") (pin "4") (pinfunction "DIN_4") (pintype "passive"))
    )
    (net (code "54") (name "Net-(LED6-DOUT)") (class "Default")
      (node (ref "LED6") (pin "2") (pinfunction "DOUT_2") (pintype "passive"))
      (node (ref "LED7") (pin "4") (pinfunction "DIN_4") (pintype "passive"))
    )
    (net (code "55") (name "Net-(LED8-DOUT)") (class "Default")
      (node (ref "LED8") (pin "2") (pinfunction "DOUT_2") (pintype "passive"))
      (node (ref "LED9") (pin "4") (pinfunction "DIN_4") (pintype "passive"))
    )
    (net (code "56") (name "Net-(LED10-DIN)") (class "Default")
      (node (ref "LED10") (pin "4") (pinfunction "DIN_4") (pintype "passive"))
      (node (ref "LED9") (pin "2") (pinfunction "DOUT_2") (pintype "passive"))
    )
    (net (code "57") (name "Net-(LED10-DOUT)") (class "Default")
      (node (ref "LED10") (pin "2") (pinfunction "DOUT_2") (pintype "passive"))
      (node (ref "LED11") (pin "4") (pinfunction "DIN_4") (pintype "passive"))
    )
    (net (code "58") (name "Net-(LED11-DOUT)") (class "Default")
      (node (ref "LED11") (pin "2") (pinfunction "DOUT_2") (pintype "passive"))
      (node (ref "LED12") (pin "4") (pinfunction "DIN_4") (pintype "passive"))
    )
    (net (code "59") (name "Net-(LED12-DOUT)") (class "Default")
      (node (ref "LED12") (pin "2") (pinfunction "DOUT_2") (pintype "passive"))
      (node (ref "LED15") (pin "4") (pinfunction "DIN_4") (pintype "passive"))
    )
    (net (code "60") (name "Net-(LED13-DIN)") (class "Default")
      (node (ref "LED13") (pin "4") (pinfunction "DIN_4") (pintype "passive"))
      (node (ref "LED14") (pin "2") (pinfunction "DOUT_2") (pintype "passive"))
    )
    (net (code "61") (name "Net-(LED13-DOUT)") (class "Default")
      (node (ref "LED13") (pin "2") (pinfunction "DOUT_2") (pintype "passive"))
      (node (ref "LED16") (pin "4") (pinfunction "DIN_4") (pintype "passive"))
    )
    (net (code "62") (name "Net-(LED14-DIN)") (class "Default")
      (node (ref "LED14") (pin "4") (pinfunction "DIN_4") (pintype "passive"))
      (node (ref "LED15") (pin "2") (pinfunction "DOUT_2") (pintype "passive"))
    )
    (net (code "63") (name "Net-(LED17-DIN)") (class "Default")
      (node (ref "LED17") (pin "4") (pinfunction "DIN_4") (pintype "passive"))
      (node (ref "LED7") (pin "2") (pinfunction "DOUT_2") (pintype "passive"))
    )
    (net (code "64") (name "Net-(LED17-DOUT)") (class "Default")
      (node (ref "LED17") (pin "2") (pinfunction "DOUT_2") (pintype "passive"))
      (node (ref "LED5") (pin "4") (pinfunction "DIN_4") (pintype "passive"))
    )
    (net (code "65") (name "Net-(LED18-DIN)") (class "Default")
      (node (ref "LED18") (pin "4") (pinfunction "DIN_4") (pintype "passive"))
      (node (ref "LED19") (pin "2") (pinfunction "DOUT_2") (pintype "passive"))
    )
    (net (code "66") (name "Net-(LED18-DOUT)") (class "Default")
      (node (ref "LED18") (pin "2") (pinfunction "DOUT_2") (pintype "passive"))
      (node (ref "LED6") (pin "4") (pinfunction "DIN_4") (pintype "passive"))
    )
    (net (code "67") (name "Net-(LED19-DIN)") (class "Default")
      (node (ref "LED19") (pin "4") (pinfunction "DIN_4") (pintype "passive"))
      (node (ref "LED20") (pin "2") (pinfunction "DOUT_2") (pintype "passive"))
    )
    (net (code "68") (name "Net-(LED20-DIN)") (class "Default")
      (node (ref "LED20") (pin "4") (pinfunction "DIN_4") (pintype "passive"))
      (node (ref "LED21") (pin "2") (pinfunction "DOUT_2") (pintype "passive"))
    )
    (net (code "69") (name "Net-(LED21-DIN)") (class "Default")
      (node (ref "LED21") (pin "4") (pinfunction "DIN_4") (pintype "passive"))
      (node (ref "LED22") (pin "2") (pinfunction "DOUT_2") (pintype "passive"))
    )
    (net (code "70") (name "Net-(LED23-DIN)") (class "Default")
      (node (ref "LED23") (pin "4") (pinfunction "DIN_4") (pintype "passive"))
      (node (ref "LED5") (pin "2") (pinfunction "DOUT_2") (pintype "passive"))
    )
    (net (code "71") (name "Net-(LED23-DOUT)") (class "Default")
      (node (ref "LED23") (pin "2") (pinfunction "DOUT_2") (pintype "passive"))
      (node (ref "LED4") (pin "4") (pinfunction "DIN_4") (pintype "passive"))
    )
    (net (code "72") (name "Net-(LED24-DIN)") (class "Default")
      (node (ref "LED24") (pin "4") (pinfunction "DIN_4") (pintype "passive"))
      (node (ref "LED33") (pin "2") (pinfunction "DOUT_2") (pintype "passive"))
    )
    (net (code "73") (name "Net-(LED24-DOUT)") (class "Default")
      (node (ref "LED24") (pin "2") (pinfunction "DOUT_2") (pintype "passive"))
      (node (ref "LED34") (pin "4") (pinfunction "DIN_4") (pintype "passive"))
    )
    (net (code "74") (name "Net-(LED25-DIN)") (class "Default")
      (node (ref "H1") (pin "2") (pinfunction "2_2") (pintype "passive"))
      (node (ref "H5") (pin "2") (pinfunction "2_2") (pintype "passive"))
      (node (ref "LED25") (pin "4") (pinfunction "DIN_4") (pintype "passive"))
      (node (ref "LED4") (pin "2") (pinfunction "DOUT_2") (pintype "passive"))
    )
    (net (code "75") (name "Net-(LED25-DOUT)") (class "Default")
      (node (ref "LED25") (pin "2") (pinfunction "DOUT_2") (pintype "passive"))
      (node (ref "LED26") (pin "4") (pinfunction "DIN_4") (pintype "passive"))
    )
    (net (code "76") (name "Net-(LED26-DOUT)") (class "Default")
      (node (ref "LED26") (pin "2") (pinfunction "DOUT_2") (pintype "passive"))
      (node (ref "LED27") (pin "4") (pinfunction "DIN_4") (pintype "passive"))
    )
    (net (code "77") (name "Net-(LED27-DOUT)") (class "Default")
      (node (ref "LED27") (pin "2") (pinfunction "DOUT_2") (pintype "passive"))
      (node (ref "LED28") (pin "4") (pinfunction "DIN_4") (pintype "passive"))
    )
    (net (code "78") (name "Net-(LED28-DOUT)") (class "Default")
      (node (ref "LED28") (pin "2") (pinfunction "DOUT_2") (pintype "passive"))
      (node (ref "LED29") (pin "4") (pinfunction "DIN_4") (pintype "passive"))
    )
    (net (code "79") (name "Net-(LED29-DOUT)") (class "Default")
      (node (ref "LED29") (pin "2") (pinfunction "DOUT_2") (pintype "passive"))
      (node (ref "LED32") (pin "4") (pinfunction "DIN_4") (pintype "passive"))
    )
    (net (code "80") (name "Net-(LED30-DIN)") (class "Default")
      (node (ref "LED30") (pin "4") (pinfunction "DIN_4") (pintype "passive"))
      (node (ref "LED31") (pin "2") (pinfunction "DOUT_2") (pintype "passive"))
    )
    (net (code "81") (name "Net-(LED30-DOUT)") (class "Default")
      (node (ref "LED30") (pin "2") (pinfunction "DOUT_2") (pintype "passive"))
      (node (ref "LED33") (pin "4") (pinfunction "DIN_4") (pintype "passive"))
    )
    (net (code "82") (name "Net-(LED31-DIN)") (class "Default")
      (node (ref "LED31") (pin "4") (pinfunction "DIN_4") (pintype "passive"))
      (node (ref "LED32") (pin "2") (pinfunction "DOUT_2") (pintype "passive"))
    )
    (net (code "83") (name "Net-(LED34-DOUT)") (class "Default")
      (node (ref "H6") (pin "2") (pinfunction "2_2") (pintype "passive"))
      (node (ref "H8") (pin "2") (pinfunction "2_2") (pintype "passive"))
      (node (ref "LED34") (pin "2") (pinfunction "DOUT_2") (pintype "passive"))
      (node (ref "LED44") (pin "4") (pinfunction "DIN_4") (pintype "passive"))
    )
    (net (code "84") (name "Net-(LED35-DIN)") (class "Default")
      (node (ref "LED35") (pin "4") (pinfunction "DIN_4") (pintype "passive"))
      (node (ref "LED45") (pin "2") (pinfunction "DOUT_2") (pintype "passive"))
    )
    (net (code "85") (name "Net-(LED35-DOUT)") (class "Default")
      (node (ref "H7") (pin "2") (pinfunction "2_2") (pintype "passive"))
      (node (ref "H9") (pin "2") (pinfunction "2_2") (pintype "passive"))
      (node (ref "LED35") (pin "2") (pinfunction "DOUT_2") (pintype "passive"))
      (node (ref "LED47") (pin "4") (pinfunction "DIN_4") (pintype "passive"))
    )
    (net (code "86") (name "Net-(LED36-DIN)") (class "Default")
      (node (ref "LED36") (pin "4") (pinfunction "DIN_4") (pintype "passive"))
      (node (ref "LED39") (pin "2") (pinfunction "DOUT_2") (pintype "passive"))
    )
    (net (code "87") (name "Net-(LED36-DOUT)") (class "Default")
      (node (ref "LED36") (pin "2") (pinfunction "DOUT_2") (pintype "passive"))
      (node (ref "LED45") (pin "4") (pinfunction "DIN_4") (pintype "passive"))
    )
    (net (code "88") (name "Net-(LED37-DIN)") (class "Default")
      (node (ref "LED37") (pin "4") (pinfunction "DIN_4") (pintype "passive"))
      (node (ref "LED40") (pin "2") (pinfunction "DOUT_2") (pintype "passive"))
    )
    (net (code "89") (name "Net-(LED37-DOUT)") (class "Default")
      (node (ref "LED37") (pin "2") (pinfunction "DOUT_2") (pintype "passive"))
      (node (ref "LED38") (pin "4") (pinfunction "DIN_4") (pintype "passive"))
    )
    (net (code "90") (name "Net-(LED38-DOUT)") (class "Default")
      (node (ref "LED38") (pin "2") (pinfunction "DOUT_2") (pintype "passive"))
      (node (ref "LED39") (pin "4") (pinfunction "DIN_4") (pintype "passive"))
    )
    (net (code "91") (name "Net-(LED40-DIN)") (class "Default")
      (node (ref "LED40") (pin "4") (pinfunction "DIN_4") (pintype "passive"))
      (node (ref "LED41") (pin "2") (pinfunction "DOUT_2") (pintype "passive"))
    )
    (net (code "92") (name "Net-(LED41-DIN)") (class "Default")
      (node (ref "LED41") (pin "4") (pinfunction "DIN_4") (pintype "passive"))
      (node (ref "LED42") (pin "2") (pinfunction "DOUT_2") (pintype "passive"))
    )
    (net (code "93") (name "Net-(LED42-DIN)") (class "Default")
      (node (ref "LED42") (pin "4") (pinfunction "DIN_4") (pintype "passive"))
      (node (ref "LED43") (pin "2") (pinfunction "DOUT_2") (pintype "passive"))
    )
    (net (code "94") (name "Net-(LED43-DIN)") (class "Default")
      (node (ref "LED43") (pin "4") (pinfunction "DIN_4") (pintype "passive"))
      (node (ref "LED44") (pin "2") (pinfunction "DOUT_2") (pintype "passive"))
    )
    (net (code "95") (name "Net-(LED46-DIN)") (class "Default")
      (node (ref "LED46") (pin "4") (pinfunction "DIN_4") (pintype "passive"))
      (node (ref "LED55") (pin "2") (pinfunction "DOUT_2") (pintype "passive"))
    )
    (net (code "96") (name "Net-(LED46-DOUT)") (class "Default")
      (node (ref "LED46") (pin "2") (pinfunction "DOUT_2") (pintype "passive"))
      (node (ref "LED56") (pin "4") (pinfunction "DIN_4") (pintype "passive"))
    )
    (net (code "97") (name "Net-(LED47-DOUT)") (class "Default")
      (node (ref "LED47") (pin "2") (pinfunction "DOUT_2") (pintype "passive"))
      (node (ref "LED48") (pin "4") (pinfunction "DIN_4") (pintype "passive"))
    )
    (net (code "98") (name "Net-(LED48-DOUT)") (class "Default")
      (node (ref "LED48") (pin "2") (pinfunction "DOUT_2") (pintype "passive"))
      (node (ref "LED49") (pin "4") (pinfunction "DIN_4") (pintype "passive"))
    )
    (net (code "99") (name "Net-(LED49-DOUT)") (class "Default")
      (node (ref "LED49") (pin "2") (pinfunction "DOUT_2") (pintype "passive"))
      (node (ref "LED50") (pin "4") (pinfunction "DIN_4") (pintype "passive"))
    )
    (net (code "100") (name "Net-(LED50-DOUT)") (class "Default")
      (node (ref "LED50") (pin "2") (pinfunction "DOUT_2") (pintype "passive"))
      (node (ref "LED51") (pin "4") (pinfunction "DIN_4") (pintype "passive"))
    )
    (net (code "101") (name "Net-(LED51-DOUT)") (class "Default")
      (node (ref "LED51") (pin "2") (pinfunction "DOUT_2") (pintype "passive"))
      (node (ref "LED54") (pin "4") (pinfunction "DIN_4") (pintype "passive"))
    )
    (net (code "102") (name "Net-(LED52-DIN)") (class "Default")
      (node (ref "LED52") (pin "4") (pinfunction "DIN_4") (pintype "passive"))
      (node (ref "LED53") (pin "2") (pinfunction "DOUT_2") (pintype "passive"))
    )
    (net (code "103") (name "Net-(LED52-DOUT)") (class "Default")
      (node (ref "LED52") (pin "2") (pinfunction "DOUT_2") (pintype "passive"))
      (node (ref "LED55") (pin "4") (pinfunction "DIN_4") (pintype "passive"))
    )
    (net (code "104") (name "Net-(LED53-DIN)") (class "Default")
      (node (ref "LED53") (pin "4") (pinfunction "DIN_4") (pintype "passive"))
      (node (ref "LED54") (pin "2") (pinfunction "DOUT_2") (pintype "passive"))
    )
    (net (code "105") (name "Net-(LED56-DOUT)") (class "Default")
      (node (ref "H10") (pin "2") (pinfunction "2_2") (pintype "passive"))
      (node (ref "H12") (pin "2") (pinfunction "2_2") (pintype "passive"))
      (node (ref "LED56") (pin "2") (pinfunction "DOUT_2") (pintype "passive"))
      (node (ref "LED66") (pin "4") (pinfunction "DIN_4") (pintype "passive"))
    )
    (net (code "106") (name "Net-(LED57-DIN)") (class "Default")
      (node (ref "LED57") (pin "4") (pinfunction "DIN_4") (pintype "passive"))
      (node (ref "LED67") (pin "2") (pinfunction "DOUT_2") (pintype "passive"))
    )
    (net (code "107") (name "Net-(LED57-DOUT)") (class "Default")
      (node (ref "H11") (pin "2") (pinfunction "2_2") (pintype "passive"))
      (node (ref "H13") (pin "2") (pinfunction "2_2") (pintype "passive"))
      (node (ref "LED57") (pin "2") (pinfunction "DOUT_2") (pintype "passive"))
      (node (ref "LED69") (pin "4") (pinfunction "DIN_4") (pintype "passive"))
    )
    (net (code "108") (name "Net-(LED58-DIN)") (class "Default")
      (node (ref "LED58") (pin "4") (pinfunction "DIN_4") (pintype "passive"))
      (node (ref "LED61") (pin "2") (pinfunction "DOUT_2") (pintype "passive"))
    )
    (net (code "109") (name "Net-(LED58-DOUT)") (class "Default")
      (node (ref "LED58") (pin "2") (pinfunction "DOUT_2") (pintype "passive"))
      (node (ref "LED67") (pin "4") (pinfunction "DIN_4") (pintype "passive"))
    )
    (net (code "110") (name "Net-(LED59-DIN)") (class "Default")
      (node (ref "LED59") (pin "4") (pinfunction "DIN_4") (pintype "passive"))
      (node (ref "LED62") (pin "2") (pinfunction "DOUT_2") (pintype "passive"))
    )
    (net (code "111") (name "Net-(LED59-DOUT)") (class "Default")
      (node (ref "LED59") (pin "2") (pinfunction "DOUT_2") (pintype "passive"))
      (node (ref "LED60") (pin "4") (pinfunction "DIN_4") (pintype "passive"))
    )
    (net (code "112") (name "Net-(LED60-DOUT)") (class "Default")
      (node (ref "LED60") (pin "2") (pinfunction "DOUT_2") (pintype "passive"))
      (node (ref "LED61") (pin "4") (pinfunction "DIN_4") (pintype "passive"))
    )
    (net (code "113") (name "Net-(LED62-DIN)") (class "Default")
      (node (ref "LED62") (pin "4") (pinfunction "DIN_4") (pintype "passive"))
      (node (ref "LED63") (pin "2") (pinfunction "DOUT_2") (pintype "passive"))
    )
    (net (code "114") (name "Net-(LED63-DIN)") (class "Default")
      (node (ref "LED63") (pin "4") (pinfunction "DIN_4") (pintype "passive"))
      (node (ref "LED64") (pin "2") (pinfunction "DOUT_2") (pintype "passive"))
    )
    (net (code "115") (name "Net-(LED64-DIN)") (class "Default")
      (node (ref "LED64") (pin "4") (pinfunction "DIN_4") (pintype "passive"))
      (node (ref "LED65") (pin "2") (pinfunction "DOUT_2") (pintype "passive"))
    )
    (net (code "116") (name "Net-(LED65-DIN)") (class "Default")
      (node (ref "LED65") (pin "4") (pinfunction "DIN_4") (pintype "passive"))
      (node (ref "LED66") (pin "2") (pinfunction "DOUT_2") (pintype "passive"))
    )
    (net (code "117") (name "Net-(LED68-DIN)") (class "Default")
      (node (ref "LED68") (pin "4") (pinfunction "DIN_4") (pintype "passive"))
      (node (ref "LED77") (pin "2") (pinfunction "DOUT_2") (pintype "passive"))
    )
    (net (code "118") (name "Net-(LED68-DOUT)") (class "Default")
      (node (ref "LED68") (pin "2") (pinfunction "DOUT_2") (pintype "passive"))
      (node (ref "LED78") (pin "4") (pinfunction "DIN_4") (pintype "passive"))
    )
    (net (code "119") (name "Net-(LED69-DOUT)") (class "Default")
      (node (ref "LED69") (pin "2") (pinfunction "DOUT_2") (pintype "passive"))
      (node (ref "LED70") (pin "4") (pinfunction "DIN_4") (pintype "passive"))
    )
    (net (code "120") (name "Net-(LED70-DOUT)") (class "Default")
      (node (ref "LED70") (pin "2") (pinfunction "DOUT_2") (pintype "passive"))
      (node (ref "LED71") (pin "4") (pinfunction "DIN_4") (pintype "passive"))
    )
    (net (code "121") (name "Net-(LED71-DOUT)") (class "Default")
      (node (ref "LED71") (pin "2") (pinfunction "DOUT_2") (pintype "passive"))
      (node (ref "LED72") (pin "4") (pinfunction "DIN_4") (pintype "passive"))
    )
    (net (code "122") (name "Net-(LED72-DOUT)") (class "Default")
      (node (ref "LED72") (pin "2") (pinfunction "DOUT_2") (pintype "passive"))
      (node (ref "LED73") (pin "4") (pinfunction "DIN_4") (pintype "passive"))
    )
    (net (code "123") (name "Net-(LED73-DOUT)") (class "Default")
      (node (ref "LED73") (pin "2") (pinfunction "DOUT_2") (pintype "passive"))
      (node (ref "LED76") (pin "4") (pinfunction "DIN_4") (pintype "passive"))
    )
    (net (code "124") (name "Net-(LED74-DIN)") (class "Default")
      (node (ref "LED74") (pin "4") (pinfunction "DIN_4") (pintype "passive"))
      (node (ref "LED75") (pin "2") (pinfunction "DOUT_2") (pintype "passive"))
    )
    (net (code "125") (name "Net-(LED74-DOUT)") (class "Default")
      (node (ref "LED74") (pin "2") (pinfunction "DOUT_2") (pintype "passive"))
      (node (ref "LED77") (pin "4") (pinfunction "DIN_4") (pintype "passive"))
    )
    (net (code "126") (name "Net-(LED75-DIN)") (class "Default")
      (node (ref "LED75") (pin "4") (pinfunction "DIN_4") (pintype "passive"))
      (node (ref "LED76") (pin "2") (pinfunction "DOUT_2") (pintype "passive"))
    )
    (net (code "127") (name "Net-(LED78-DOUT)") (class "Default")
      (node (ref "H14") (pin "2") (pinfunction "2_2") (pintype "passive"))
      (node (ref "H16") (pin "2") (pinfunction "2_2") (pintype "passive"))
      (node (ref "LED78") (pin "2") (pinfunction "DOUT_2") (pintype "passive"))
      (node (ref "LED88") (pin "4") (pinfunction "DIN_4") (pintype "passive"))
    )
    (net (code "128") (name "Net-(LED79-DIN)") (class "Default")
      (node (ref "LED79") (pin "4") (pinfunction "DIN_4") (pintype "passive"))
      (node (ref "LED89") (pin "2") (pinfunction "DOUT_2") (pintype "passive"))
    )
    (net (code "129") (name "Net-(LED79-DOUT)") (class "Default")
      (node (ref "H15") (pin "2") (pinfunction "2_2") (pintype "passive"))
      (node (ref "H17") (pin "2") (pinfunction "2_2") (pintype "passive"))
      (node (ref "LED79") (pin "2") (pinfunction "DOUT_2") (pintype "passive"))
      (node (ref "LED91") (pin "4") (pinfunction "DIN_4") (pintype "passive"))
    )
    (net (code "130") (name "Net-(LED80-DIN)") (class "Default")
      (node (ref "LED80") (pin "4") (pinfunction "DIN_4") (pintype "passive"))
      (node (ref "LED83") (pin "2") (pinfunction "DOUT_2") (pintype "passive"))
    )
    (net (code "131") (name "Net-(LED80-DOUT)") (class "Default")
      (node (ref "LED80") (pin "2") (pinfunction "DOUT_2") (pintype "passive"))
      (node (ref "LED89") (pin "4") (pinfunction "DIN_4") (pintype "passive"))
    )
    (net (code "132") (name "Net-(LED81-DIN)") (class "Default")
      (node (ref "LED81") (pin "4") (pinfunction "DIN_4") (pintype "passive"))
      (node (ref "LED84") (pin "2") (pinfunction "DOUT_2") (pintype "passive"))
    )
    (net (code "133") (name "Net-(LED81-DOUT)") (class "Default")
      (node (ref "LED81") (pin "2") (pinfunction "DOUT_2") (pintype "passive"))
      (node (ref "LED82") (pin "4") (pinfunction "DIN_4") (pintype "passive"))
    )
    (net (code "134") (name "Net-(LED82-DOUT)") (class "Default")
      (node (ref "LED82") (pin "2") (pinfunction "DOUT_2") (pintype "passive"))
      (node (ref "LED83") (pin "4") (pinfunction "DIN_4") (pintype "passive"))
    )
    (net (code "135") (name "Net-(LED84-DIN)") (class "Default")
      (node (ref "LED84") (pin "4") (pinfunction "DIN_4") (pintype "passive"))
      (node (ref "LED85") (pin "2") (pinfunction "DOUT_2") (pintype "passive"))
    )
    (net (code "136") (name "Net-(LED85-DIN)") (class "Default")
      (node (ref "LED85") (pin "4") (pinfunction "DIN_4") (pintype "passive"))
      (node (ref "LED86") (pin "2") (pinfunction "DOUT_2") (pintype "passive"))
    )
    (net (code "137") (name "Net-(LED86-DIN)") (class "Default")
      (node (ref "LED86") (pin "4") (pinfunction "DIN_4") (pintype "passive"))
      (node (ref "LED87") (pin "2") (pinfunction "DOUT_2") (pintype "passive"))
    )
    (net (code "138") (name "Net-(LED87-DIN)") (class "Default")
      (node (ref "LED87") (pin "4") (pinfunction "DIN_4") (pintype "passive"))
      (node (ref "LED88") (pin "2") (pinfunction "DOUT_2") (pintype "passive"))
    )
    (net (code "139") (name "Net-(LED90-DIN)") (class "Default")
      (node (ref "LED90") (pin "4") (pinfunction "DIN_4") (pintype "passive"))
      (node (ref "LED99") (pin "2") (pinfunction "DOUT_2") (pintype "passive"))
    )
    (net (code "140") (name "Net-(LED91-DOUT)") (class "Default")
      (node (ref "LED91") (pin "2") (pinfunction "DOUT_2") (pintype "passive"))
      (node (ref "LED92") (pin "4") (pinfunction "DIN_4") (pintype "passive"))
    )
    (net (code "141") (name "Net-(LED92-DOUT)") (class "Default")
      (node (ref "LED92") (pin "2") (pinfunction "DOUT_2") (pintype "passive"))
      (node (ref "LED93") (pin "4") (pinfunction "DIN_4") (pintype "passive"))
    )
    (net (code "142") (name "Net-(LED93-DOUT)") (class "Default")
      (node (ref "LED93") (pin "2") (pinfunction "DOUT_2") (pintype "passive"))
      (node (ref "LED94") (pin "4") (pinfunction "DIN_4") (pintype "passive"))
    )
    (net (code "143") (name "Net-(LED94-DOUT)") (class "Default")
      (node (ref "LED94") (pin "2") (pinfunction "DOUT_2") (pintype "passive"))
      (node (ref "LED95") (pin "4") (pinfunction "DIN_4") (pintype "passive"))
    )
    (net (code "144") (name "Net-(LED95-DOUT)") (class "Default")
      (node (ref "LED95") (pin "2") (pinfunction "DOUT_2") (pintype "passive"))
      (node (ref "LED98") (pin "4") (pinfunction "DIN_4") (pintype "passive"))
    )
    (net (code "145") (name "Net-(LED96-DIN)") (class "Default")
      (node (ref "LED96") (pin "4") (pinfunction "DIN_4") (pintype "passive"))
      (node (ref "LED97") (pin "2") (pinfunction "DOUT_2") (pintype "passive"))
    )
    (net (code "146") (name "Net-(LED96-DOUT)") (class "Default")
      (node (ref "LED96") (pin "2") (pinfunction "DOUT_2") (pintype "passive"))
      (node (ref "LED99") (pin "4") (pinfunction "DIN_4") (pintype "passive"))
    )
    (net (code "147") (name "Net-(LED97-DIN)") (class "Default")
      (node (ref "LED97") (pin "4") (pinfunction "DIN_4") (pintype "passive"))
      (node (ref "LED98") (pin "2") (pinfunction "DOUT_2") (pintype "passive"))
    )
    (net (code "148") (name "Net-(LED100-DIN)") (class "Default")
      (node (ref "LED100") (pin "4") (pinfunction "DIN_4") (pintype "passive"))
      (node (ref "LED90") (pin "2") (pinfunction "DOUT_2") (pintype "passive"))
    )
    (net (code "149") (name "Net-(LED100-DOUT)") (class "Default")
      (node (ref "H18") (pin "2") (pinfunction "2_2") (pintype "passive"))
      (node (ref "LED100") (pin "2") (pinfunction "DOUT_2") (pintype "passive"))
      (node (ref "LED113") (pin "4") (pinfunction "DIN_4") (pintype "passive"))
    )
    (net (code "150") (name "Net-(LED101-DIN)") (class "Default")
      (node (ref "LED101") (pin "4") (pinfunction "DIN_4") (pintype "passive"))
      (node (ref "LED111") (pin "2") (pinfunction "DOUT_2") (pintype "passive"))
    )
    (net (code "151") (name "Net-(LED101-DOUT)") (class "Default")
      (node (ref "H19") (pin "2") (pinfunction "2_2") (pintype "passive"))
      (node (ref "LED101") (pin "2") (pinfunction "DOUT_2") (pintype "passive"))
      (node (ref "LED112") (pin "4") (pinfunction "DIN_4") (pintype "passive"))
    )
    (net (code "152") (name "Net-(LED102-DIN)") (class "Default")
      (node (ref "LED102") (pin "4") (pinfunction "DIN_4") (pintype "passive"))
      (node (ref "LED105") (pin "2") (pinfunction "DOUT_2") (pintype "passive"))
    )
    (net (code "153") (name "Net-(LED102-DOUT)") (class "Default")
      (node (ref "LED102") (pin "2") (pinfunction "DOUT_2") (pintype "passive"))
      (node (ref "LED111") (pin "4") (pinfunction "DIN_4") (pintype "passive"))
    )
    (net (code "154") (name "Net-(LED103-DIN)") (class "Default")
      (node (ref "LED103") (pin "4") (pinfunction "DIN_4") (pintype "passive"))
      (node (ref "LED106") (pin "2") (pinfunction "DOUT_2") (pintype "passive"))
    )
    (net (code "155") (name "Net-(LED103-DOUT)") (class "Default")
      (node (ref "LED103") (pin "2") (pinfunction "DOUT_2") (pintype "passive"))
      (node (ref "LED104") (pin "4") (pinfunction "DIN_4") (pintype "passive"))
    )
    (net (code "156") (name "Net-(LED104-DOUT)") (class "Default")
      (node (ref "LED104") (pin "2") (pinfunction "DOUT_2") (pintype "passive"))
      (node (ref "LED105") (pin "4") (pinfunction "DIN_4") (pintype "passive"))
    )
    (net (code "157") (name "Net-(LED106-DIN)") (class "Default")
      (node (ref "LED106") (pin "4") (pinfunction "DIN_4") (pintype "passive"))
      (node (ref "LED107") (pin "2") (pinfunction "DOUT_2") (pintype "passive"))
    )
    (net (code "158") (name "Net-(LED107-DIN)") (class "Default")
      (node (ref "LED107") (pin "4") (pinfunction "DIN_4") (pintype "passive"))
      (node (ref "LED108") (pin "2") (pinfunction "DOUT_2") (pintype "passive"))
    )
    (net (code "159") (name "Net-(LED108-DIN)") (class "Default")
      (node (ref "LED108") (pin "4") (pinfunction "DIN_4") (pintype "passive"))
      (node (ref "LED109") (pin "2") (pinfunction "DOUT_2") (pintype "passive"))
    )
    (net (code "160") (name "Net-(LED109-DIN)") (class "Default")
      (node (ref "LED109") (pin "4") (pinfunction "DIN_4") (pintype "passive"))
      (node (ref "LED110") (pin "2") (pinfunction "DOUT_2") (pintype "passive"))
    )
    (net (code "161") (name "Net-(LED110-DIN)") (class "Default")
      (node (ref "H20") (pin "2") (pinfunction "2_2") (pintype "passive"))
      (node (ref "LED110") (pin "4") (pinfunction "DIN_4") (pintype "passive"))
      (node (ref "LED113") (pin "2") (pinfunction "DOUT_2") (pintype "passive"))
    )
    (net (code "162") (name "Net-(LED114-DIN)") (class "Default")
      (node (ref "H3") (pin "2") (pinfunction "2_2") (pintype "passive"))
      (node (ref "LED114") (pin "4") (pinfunction "DIN_4") (pintype "passive"))
      (node (ref "LED3") (pin "2") (pinfunction "DOUT_2") (pintype "passive"))
    )
    (net (code "163") (name "Net-(LED114-DOUT)") (class "Default")
      (node (ref "H4") (pin "2") (pinfunction "2_2") (pintype "passive"))
      (node (ref "LED114") (pin "2") (pinfunction "DOUT_2") (pintype "passive"))
      (node (ref "LED22") (pin "4") (pinfunction "DIN_4") (pintype "passive"))
    )
    (net (code "164") (name "Net-(LED116-+)") (class "Default")
      (node (ref "LED116") (pin "2") (pinfunction "+_2") (pintype "passive"))
      (node (ref "R13") (pin "2") (pinfunction "2_2") (pintype "passive"))
    )
    (net (code "165") (name "Net-(QBOOT-Pad2)") (class "Default")
      (node (ref "QBOOT") (pin "2") (pinfunction "2_2") (pintype "passive"))
      (node (ref "R11") (pin "2") (pinfunction "2_2") (pintype "passive"))
    )
    (net (code "166") (name "Net-(QU1-USB_DM)") (class "Default")
      (node (ref "QU1") (pin "46") (pinfunction "USB_DM_46") (pintype "passive"))
      (node (ref "R9") (pin "1") (pinfunction "1_1") (pintype "passive"))
    )
    (net (code "167") (name "Net-(QU1-USB_DP)") (class "Default")
      (node (ref "QU1") (pin "47") (pinfunction "USB_DP_47") (pintype "passive"))
      (node (ref "R7") (pin "1") (pinfunction "1_1") (pintype "passive"))
    )
    (net (code "168") (name "Net-(U1-ADDR)") (class "Default")
      (node (ref "R1") (pin "1") (pinfunction "1_1") (pintype "passive"))
      (node (ref "U1") (pin "2") (pinfunction "ADDR_2") (pintype "passive"))
    )
    (net (code "169") (name "Net-(U1-DVI)") (class "Default")
      (node (ref "C7") (pin "1") (pinfunction "1_1") (pintype "passive"))
      (node (ref "R2") (pin "1") (pinfunction "1_1") (pintype "passive"))
      (node (ref "U1") (pin "5") (pinfunction "DVI_5") (pintype "passive"))
    )
    (net (code "170") (name "Net-(U3-OSCI)") (class "Default")
      (node (ref "U3") (pin "1") (pinfunction "OSCI_1") (pintype "passive"))
      (node (ref "X1") (pin "1") (pinfunction "OSC1_1") (pintype "passive"))
    )
    (net (code "171") (name "Net-(U3-OSCO)") (class "Default")
      (node (ref "U3") (pin "2") (pinfunction "OSCO_2") (pintype "passive"))
      (node (ref "X1") (pin "2") (pinfunction "OSC2_2") (pintype "passive"))
    )
    (net (code "172") (name "Net-(U3-VBAT)") (class "Default")
      (node (ref "BT1") (pin "1") (pinfunction "1_1") (pintype "passive"))
      (node (ref "BT2") (pin "1") (pinfunction "1_1") (pintype "passive"))
      (node (ref "U3") (pin "3") (pinfunction "VBAT_3") (pintype "passive"))
    )
    (net (code "173") (name "Net-(U5-EN)") (class "Default")
      (node (ref "R8") (pin "1") (pinfunction "1_1") (pintype "passive"))
      (node (ref "U5") (pin "3") (pinfunction "EN_3") (pintype "passive"))
    )
    (net (code "174") (name "Net-(U5-GPIO0)") (class "Default")
      (node (ref "ESPFLASH") (pin "4") (pinfunction "4_4") (pintype "passive"))
      (node (ref "R14") (pin "2") (pinfunction "2_2") (pintype "passive"))
      (node (ref "U5") (pin "12") (pinfunction "GPIO0_12") (pintype "passive"))
    )
    (net (code "175") (name "Net-(U5-GPIO2)") (class "Default")
      (node (ref "R15") (pin "2") (pinfunction "2_2") (pintype "passive"))
      (node (ref "U5") (pin "11") (pinfunction "GPIO2_11") (pintype "passive"))
    )
    (net (code "176") (name "Net-(U5-GPIO15)") (class "Default")
      (node (ref "R16") (pin "2") (pinfunction "2_2") (pintype "passive"))
      (node (ref "U5") (pin "10") (pinfunction "GPIO15_10") (pintype "passive"))
    )
    (net (code "177") (name "Net-(U5-GPIO16)") (class "Default")
      (node (ref "ESPRST") (pin "3") (pinfunction "3_3") (pintype "passive"))
      (node (ref "P2") (pin "5") (pinfunction "5_5") (pintype "passive"))
      (node (ref "R6") (pin "1") (pinfunction "1_1") (pintype "passive"))
      (node (ref "U5") (pin "1") (pinfunction "RST_1") (pintype "passive"))
      (node (ref "U5") (pin "4") (pinfunction "GPIO16_4") (pintype "passive"))
    )
    (net (code "178") (name "Net-(U5-RXD0)") (class "Default")
      (node (ref "JP11") (pin "1") (pinfunction "1_1") (pintype "passive"))
      (node (ref "P2") (pin "3") (pinfunction "3_3") (pintype "passive"))
      (node (ref "U5") (pin "15") (pinfunction "RXD0_15") (pintype "passive"))
    )
    (net (code "179") (name "Net-(U5-TXD0)") (class "Default")
      (node (ref "JP10") (pin "1") (pinfunction "1_1") (pintype "passive"))
      (node (ref "P2") (pin "4") (pinfunction "4_4") (pintype "passive"))
      (node (ref "U5") (pin "16") (pinfunction "TXD0_16") (pintype "passive"))
    )
    (net (code "180") (name "Net-(U6-A)") (class "Default")
      (node (ref "JP8") (pin "1") (pinfunction "1_1") (pintype "passive"))
      (node (ref "R10") (pin "2") (pinfunction "2_2") (pintype "passive"))
      (node (ref "U6") (pin "3") (pinfunction "A_3") (pintype "passive"))
    )
    (net (code "181") (name "Net-(U6-B)") (class "Default")
      (node (ref "JP6") (pin "2") (pinfunction "2_2") (pintype "passive"))
      (node (ref "JP7") (pin "2") (pinfunction "2_2") (pintype "passive"))
      (node (ref "JP8") (pin "2") (pinfunction "2_2") (pintype "passive"))
      (node (ref "U6") (pin "4") (pinfunction "B_4") (pintype "passive"))
    )
    (net (code "182") (name "Net-(U6-OE)") (class "Default")
      (node (ref "JP1") (pin "2") (pinfunction "2_2") (pintype "passive"))
      (node (ref "U6") (pin "5") (pinfunction "OE_5") (pintype "passive"))
    )
    (net (code "183") (name "VCC") (class "Default")
      (node (ref "C10") (pin "2") (pinfunction "2_2") (pintype "passive"))
      (node (ref "C125") (pin "2") (pinfunction "2_2") (pintype "passive"))
      (node (ref "C126") (pin "2") (pinfunction "2_2") (pintype "passive"))
      (node (ref "C127") (pin "2") (pinfunction "2_2") (pintype "passive"))
      (node (ref "C128") (pin "2") (pinfunction "2_2") (pintype "passive"))
      (node (ref "C129") (pin "1") (pinfunction "1_1") (pintype "passive"))
      (node (ref "C130") (pin "1") (pinfunction "1_1") (pintype "passive"))
      (node (ref "C131") (pin "2") (pinfunction "2_2") (pintype "passive"))
      (node (ref "C132") (pin "2") (pinfunction "2_2") (pintype "passive"))
      (node (ref "C133") (pin "2") (pinfunction "2_2") (pintype "passive"))
      (node (ref "C136") (pin "1") (pinfunction "1_1") (pintype "passive"))
      (node (ref "C3") (pin "1") (pinfunction "1_1") (pintype "passive"))
      (node (ref "C6") (pin "2") (pinfunction "2_2") (pintype "passive"))
      (node (ref "C9") (pin "1") (pinfunction "1_1") (pintype "passive"))
      (node (ref "H21") (pin "2") (pinfunction "2_2") (pintype "passive"))
      (node (ref "JP1") (pin "1") (pinfunction "1_1") (pintype "passive"))
      (node (ref "JP3") (pin "2") (pinfunction "2_2") (pintype "passive"))
      (node (ref "P1") (pin "1") (pinfunction "1_1") (pintype "passive"))
      (node (ref "P2") (pin "2") (pinfunction "2_2") (pintype "passive"))
      (node (ref "QU1") (pin "1") (pinfunction "IOVDD_1") (pintype "passive"))
      (node (ref "QU1") (pin "10") (pinfunction "IOVDD_10") (pintype "passive"))
      (node (ref "QU1") (pin "22") (pinfunction "IOVDD_22") (pintype "passive"))
      (node (ref "QU1") (pin "33") (pinfunction "IOVDD_33") (pintype "passive"))
      (node (ref "QU1") (pin "42") (pinfunction "IOVDD_42") (pintype "passive"))
      (node (ref "QU1") (pin "43") (pinfunction "ADC_AVDD_43") (pintype "passive"))
      (node (ref "QU1") (pin "44") (pinfunction "VREG_IN_44") (pintype "passive"))
      (node (ref "QU1") (pin "48") (pinfunction "USB_VDD_48") (pintype "passive"))
      (node (ref "QU1") (pin "49") (pinfunction "IOVDD_49") (pintype "passive"))
      (node (ref "QU2") (pin "8") (pinfunction "VCC_8") (pintype "passive"))
      (node (ref "R14") (pin "1") (pinfunction "1_1") (pintype "passive"))
      (node (ref "R15") (pin "1") (pinfunction "1_1") (pintype "passive"))
      (node (ref "R2") (pin "2") (pinfunction "2_2") (pintype "passive"))
      (node (ref "R3") (pin "1") (pinfunction "1_1") (pintype "passive"))
      (node (ref "R4") (pin "1") (pinfunction "1_1") (pintype "passive"))
      (node (ref "R5") (pin "2") (pinfunction "2_2") (pintype "passive"))
      (node (ref "R6") (pin "2") (pinfunction "2_2") (pintype "passive"))
      (node (ref "R8") (pin "2") (pinfunction "2_2") (pintype "passive"))
      (node (ref "U1") (pin "1") (pinfunction "VCC_1") (pintype "passive"))
      (node (ref "U2") (pin "2") (pinfunction "Out_2") (pintype "passive"))
      (node (ref "U3") (pin "10") (pinfunction "VDD_10") (pintype "passive"))
      (node (ref "U4") (pin "8") (pinfunction "VCC_8") (pintype "passive"))
      (node (ref "U5") (pin "8") (pinfunction "VCC_8") (pintype "passive"))
      (node (ref "U6") (pin "6") (pinfunction "VCCB_6") (pintype "passive"))
    )
    (net (code "184") (name "unconnected-(ESPFLASH-Pad1)") (class "Default")
      (node (ref "ESPFLASH") (pin "1") (pinfunction "1_1") (pintype "passive"))
    )
    (net (code "185") (name "unconnected-(ESPFLASH-Pad3)") (class "Default")
      (node (ref "ESPFLASH") (pin "3") (pinfunction "3_3") (pintype "passive"))
    )
    (net (code "186") (name "unconnected-(ESPRST-Pad2)") (class "Default")
      (node (ref "ESPRST") (pin "2") (pinfunction "2_2") (pintype "passive"))
    )
    (net (code "187") (name "unconnected-(ESPRST-Pad4)") (class "Default")
      (node (ref "ESPRST") (pin "4") (pinfunction "4_4") (pintype "passive"))
    )
    (net (code "188") (name "unconnected-(LED112-DOUT-Pad2)") (class "Default")
      (node (ref "LED112") (pin "2") (pinfunction "DOUT_2") (pintype "passive"))
    )
    (net (code "189") (name "unconnected-(QBOOT-Pad1)") (class "Default")
      (node (ref "QBOOT") (pin "1") (pinfunction "1_1") (pintype "passive"))
    )
    (net (code "190") (name "unconnected-(QBOOT-Pad3)") (class "Default")
      (node (ref "QBOOT") (pin "3") (pinfunction "3_3") (pintype "passive"))
    )
    (net (code "191") (name "unconnected-(QU2-EP-Pad9)") (class "Default")
      (node (ref "QU2") (pin "9") (pinfunction "EP_9") (pintype "passive"))
    )
    (net (code "192") (name "unconnected-(RPRST-Pad1)") (class "Default")
      (node (ref "RPRST") (pin "1") (pinfunction "1_1") (pintype "passive"))
    )
    (net (code "193") (name "unconnected-(RPRST-Pad3)") (class "Default")
      (node (ref "RPRST") (pin "3") (pinfunction "3_3") (pintype "passive"))
    )
    (net (code "194") (name "unconnected-(U1-EP-Pad7)") (class "Default")
      (node (ref "U1") (pin "7") (pinfunction "EP_7") (pintype "passive"))
    )
    (net (code "195") (name "unconnected-(U2-TAB-Pad4)") (class "Default")
      (node (ref "U2") (pin "4") (pinfunction "TAB_4") (pintype "passive"))
    )
    (net (code "196") (name "unconnected-(U3-CLK-Pad8)") (class "Default")
      (node (ref "U3") (pin "8") (pinfunction "CLK_8") (pintype "passive"))
    )
    (net (code "197") (name "unconnected-(U3-EP-Pad11)") (class "Default")
      (node (ref "U3") (pin "11") (pinfunction "EP_11") (pintype "passive"))
    )
    (net (code "198") (name "unconnected-(U3-INTA#(CLK)-Pad9)") (class "Default")
      (node (ref "U3") (pin "9") (pinfunction "INTA#(CLK)_9") (pintype "passive"))
    )
    (net (code "199") (name "unconnected-(U3-TS(CLK{slash}INTB)#-Pad4)") (class "Default")
      (node (ref "U3") (pin "4") (pinfunction "TS(CLK/INTB)#_4") (pintype "passive"))
    )
    (net (code "200") (name "unconnected-(U4-E1-Pad1)") (class "Default")
      (node (ref "U4") (pin "1") (pinfunction "E1_1") (pintype "passive"))
    )
    (net (code "201") (name "unconnected-(U4-E2-Pad2)") (class "Default")
      (node (ref "U4") (pin "2") (pinfunction "E2_2") (pintype "passive"))
    )
    (net (code "202") (name "unconnected-(U4-E3-Pad3)") (class "Default")
      (node (ref "U4") (pin "3") (pinfunction "E3_3") (pintype "passive"))
    )
    (net (code "203") (name "unconnected-(U4-WC#-Pad7)") (class "Default")
      (node (ref "U4") (pin "7") (pinfunction "WC#_7") (pintype "passive"))
    )
    (net (code "204") (name "unconnected-(U5-ADC-Pad2)") (class "Default")
      (node (ref "U5") (pin "2") (pinfunction "ADC_2") (pintype "passive"))
    )
    (net (code "205") (name "unconnected-(U5-CS0-Pad17)") (class "Default")
      (node (ref "U5") (pin "17") (pinfunction "CS0_17") (pintype "passive"))
    )
    (net (code "206") (name "unconnected-(U5-GPIO4-Pad13)") (class "Default")
      (node (ref "U5") (pin "13") (pinfunction "GPIO4_13") (pintype "passive"))
    )
    (net (code "207") (name "unconnected-(U5-GPIO5-Pad14)") (class "Default")
      (node (ref "U5") (pin "14") (pinfunction "GPIO5_14") (pintype "passive"))
    )
    (net (code "208") (name "unconnected-(U5-GPIO9-Pad19)") (class "Default")
      (node (ref "U5") (pin "19") (pinfunction "GPIO9_19") (pintype "passive"))
    )
    (net (code "209") (name "unconnected-(U5-GPIO10-Pad20)") (class "Default")
      (node (ref "U5") (pin "20") (pinfunction "GPIO10_20") (pintype "passive"))
    )
    (net (code "210") (name "unconnected-(U5-GPIO12-Pad6)") (class "Default")
      (node (ref "U5") (pin "6") (pinfunction "GPIO12_6") (pintype "passive"))
    )
    (net (code "211") (name "unconnected-(U5-GPIO13-Pad7)") (class "Default")
      (node (ref "U5") (pin "7") (pinfunction "GPIO13_7") (pintype "passive"))
    )
    (net (code "212") (name "unconnected-(U5-GPIO14-Pad5)") (class "Default")
      (node (ref "U5") (pin "5") (pinfunction "GPIO14_5") (pintype "passive"))
    )
    (net (code "213") (name "unconnected-(U5-MISO-Pad18)") (class "Default")
      (node (ref "U5") (pin "18") (pinfunction "MISO_18") (pintype "passive"))
    )
    (net (code "214") (name "unconnected-(U5-MOSI-Pad21)") (class "Default")
      (node (ref "U5") (pin "21") (pinfunction "MOSI_21") (pintype "passive"))
    )
    (net (code "215") (name "unconnected-(U5-SCLK-Pad22)") (class "Default")
      (node (ref "U5") (pin "22") (pinfunction "SCLK_22") (pintype "passive"))
    )
  )
)
